# mppt.net
KiCad netlist of a schematic drawn in Altium Designer
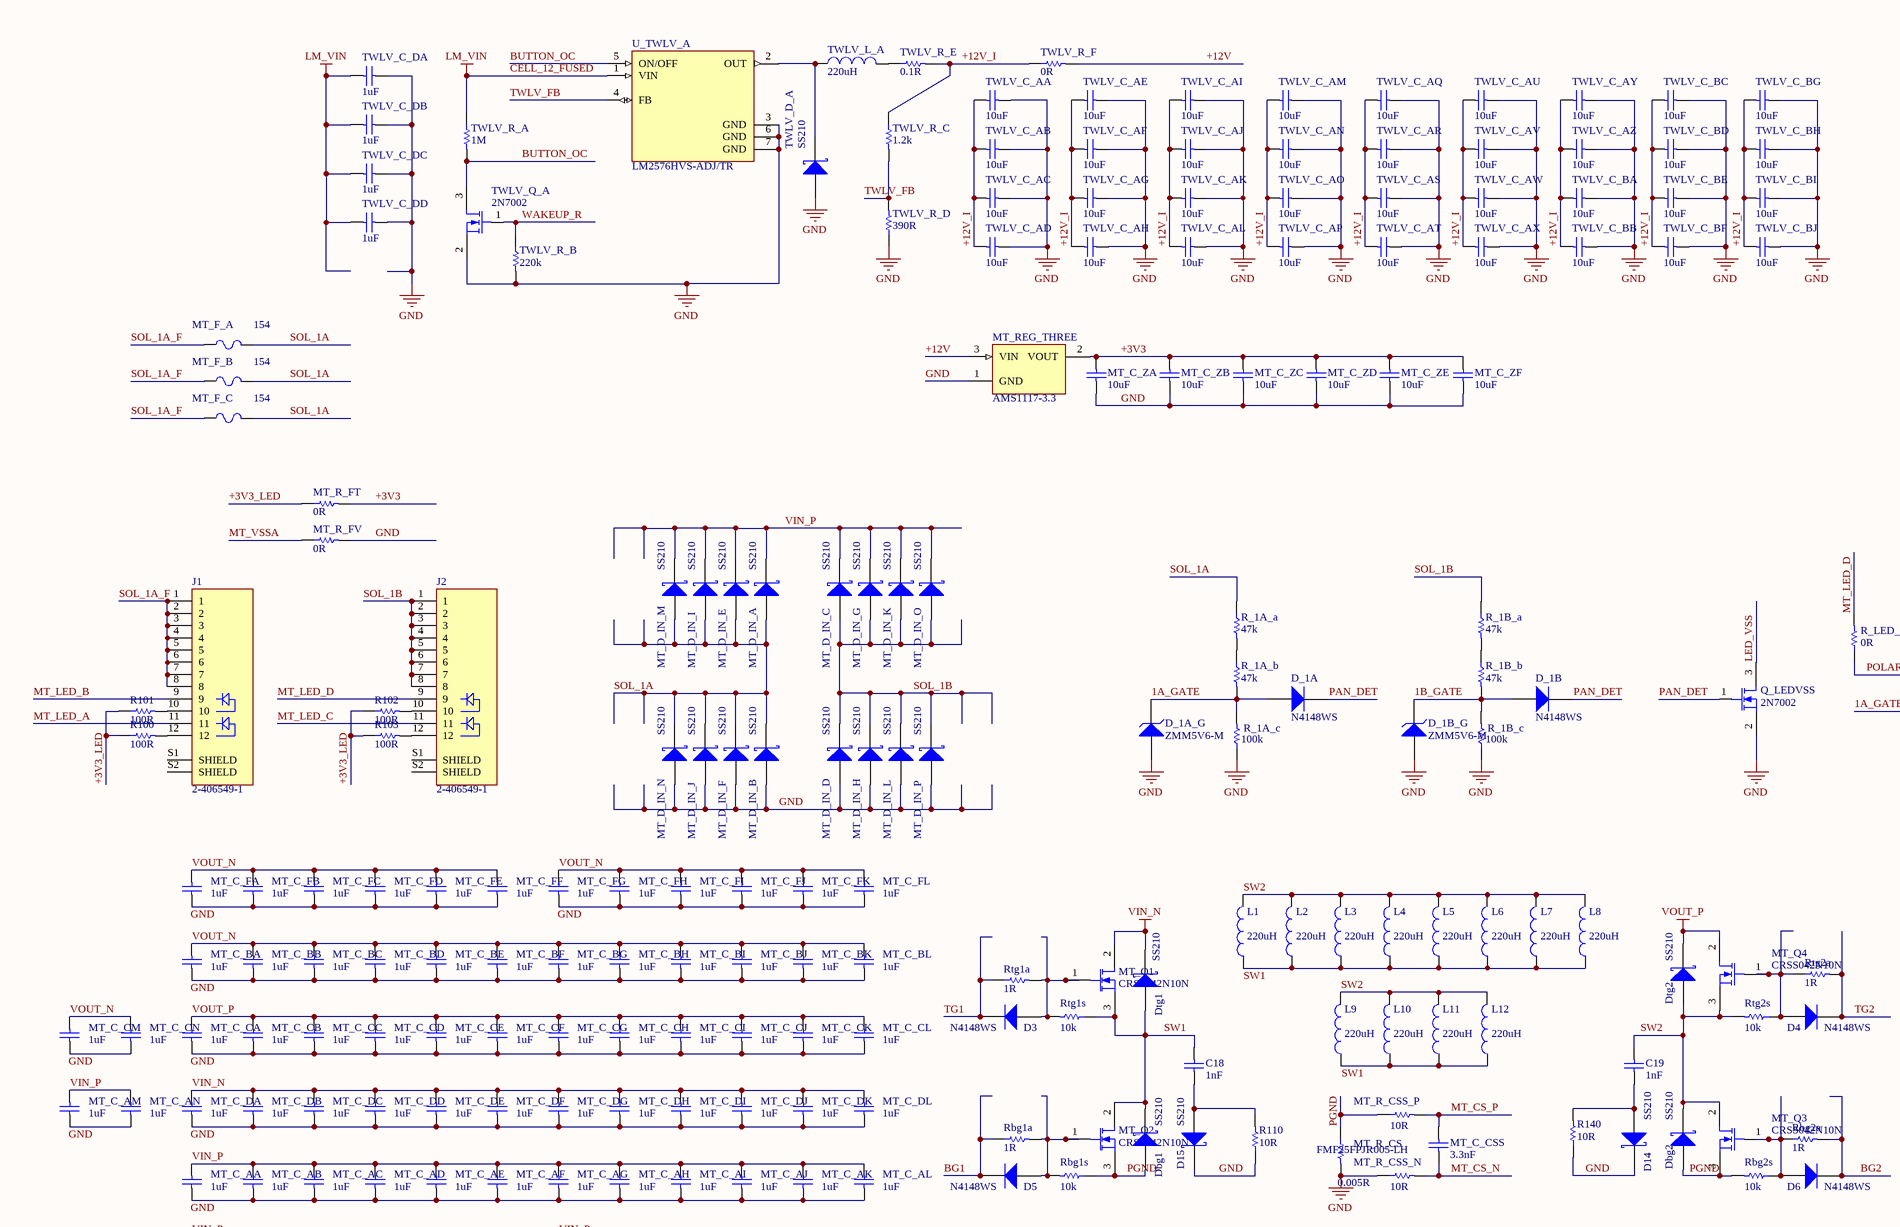
[diagram p0: mppt.SchDoc, top left]
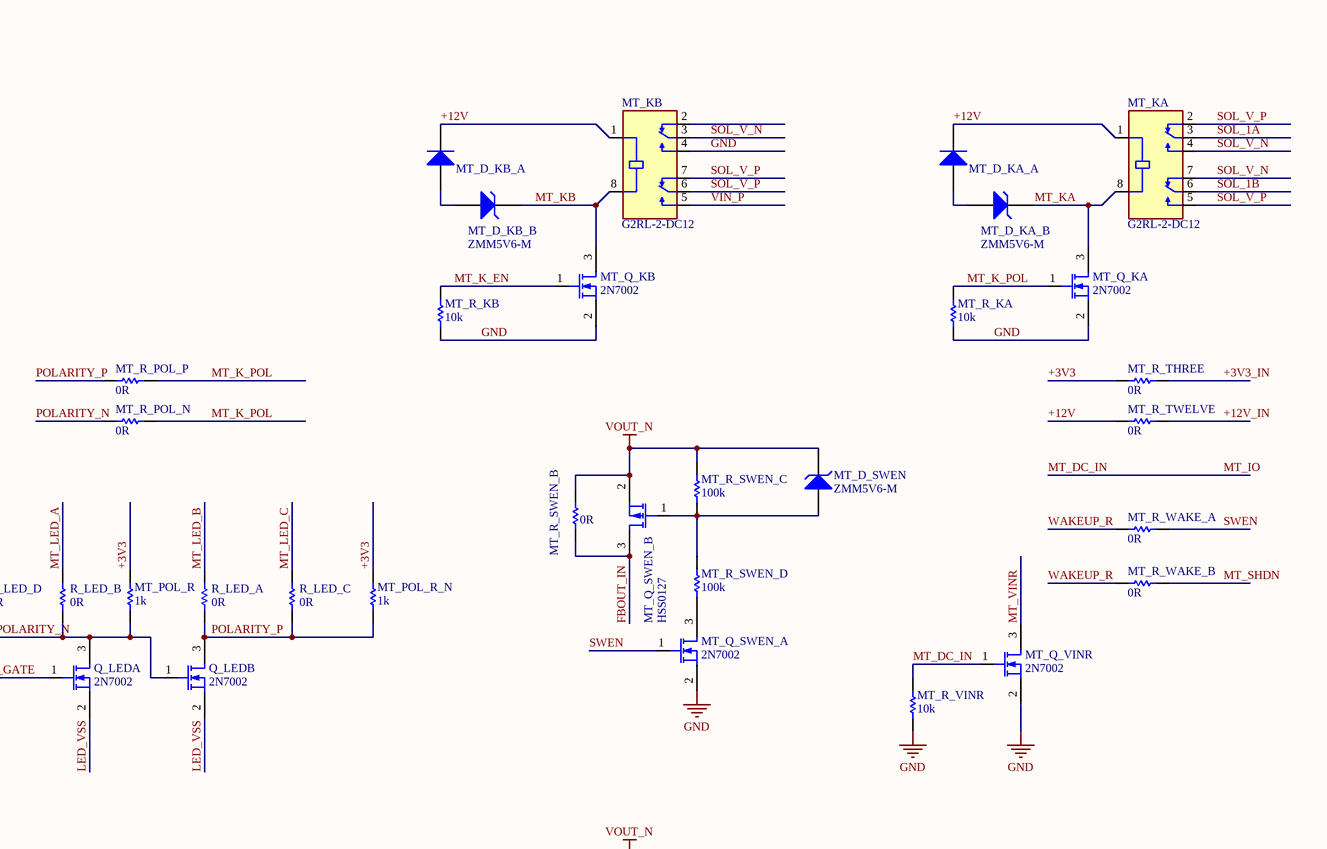
[diagram p1: mppt.SchDoc, top right]
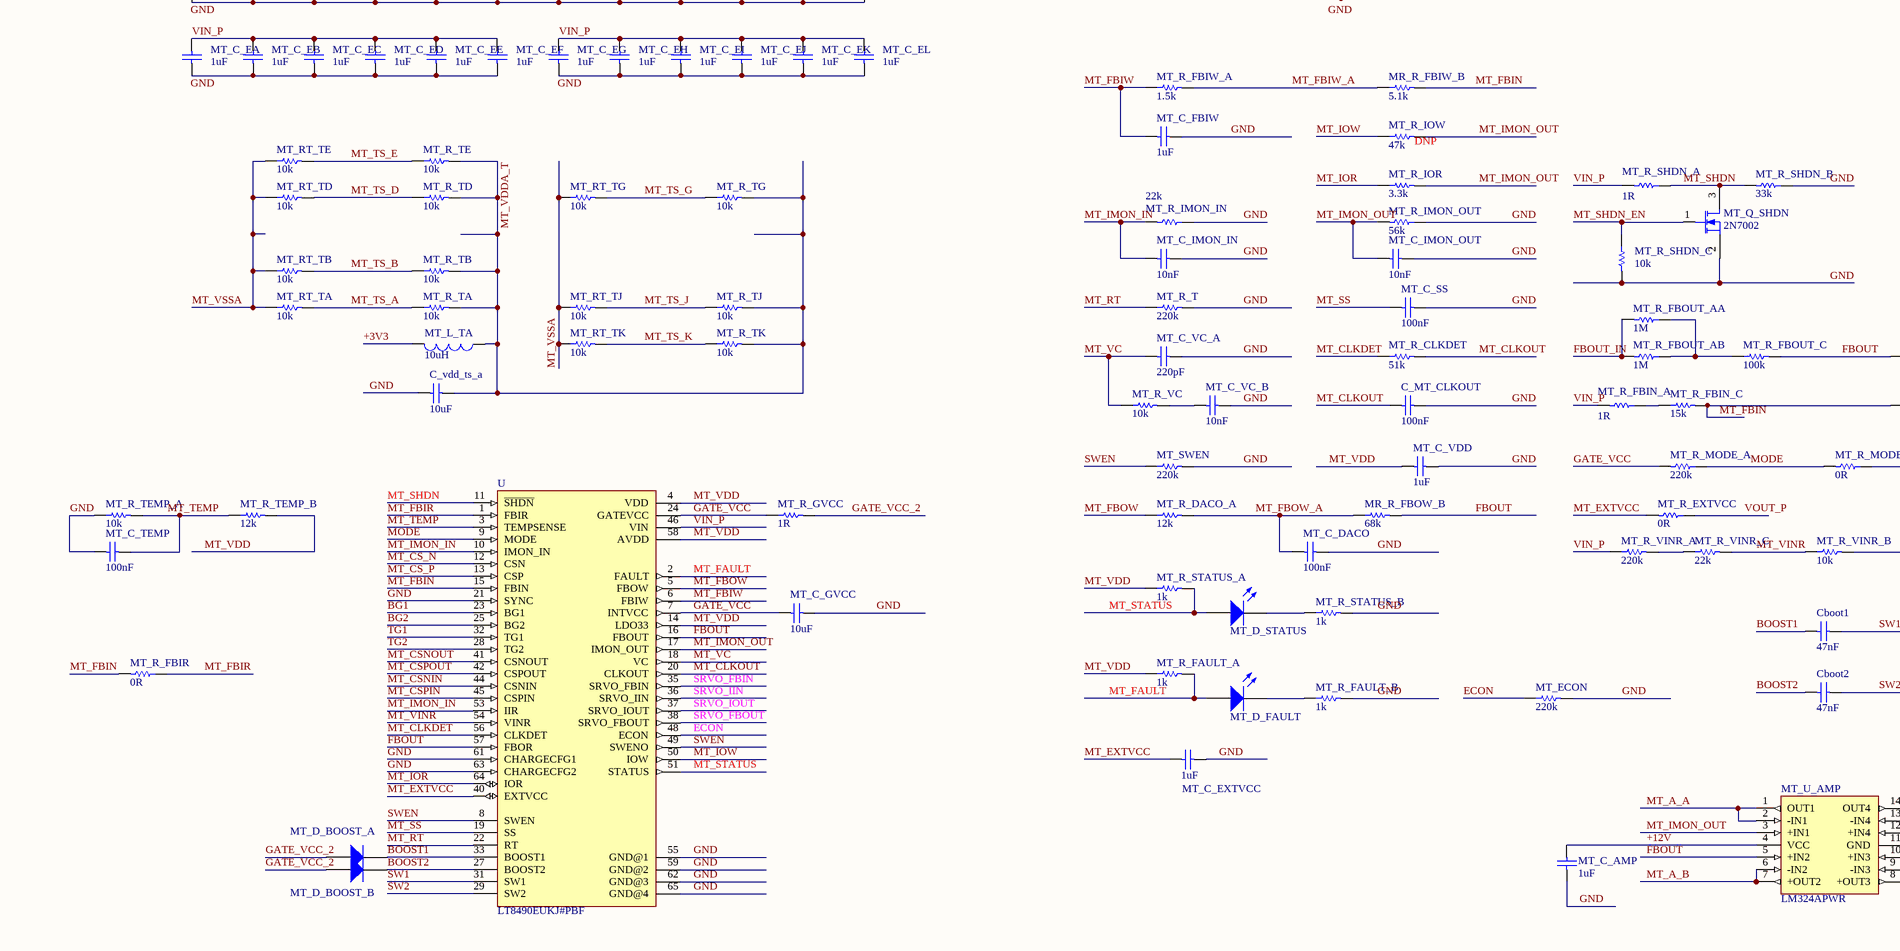
[diagram p2: mppt.SchDoc, bottom left]
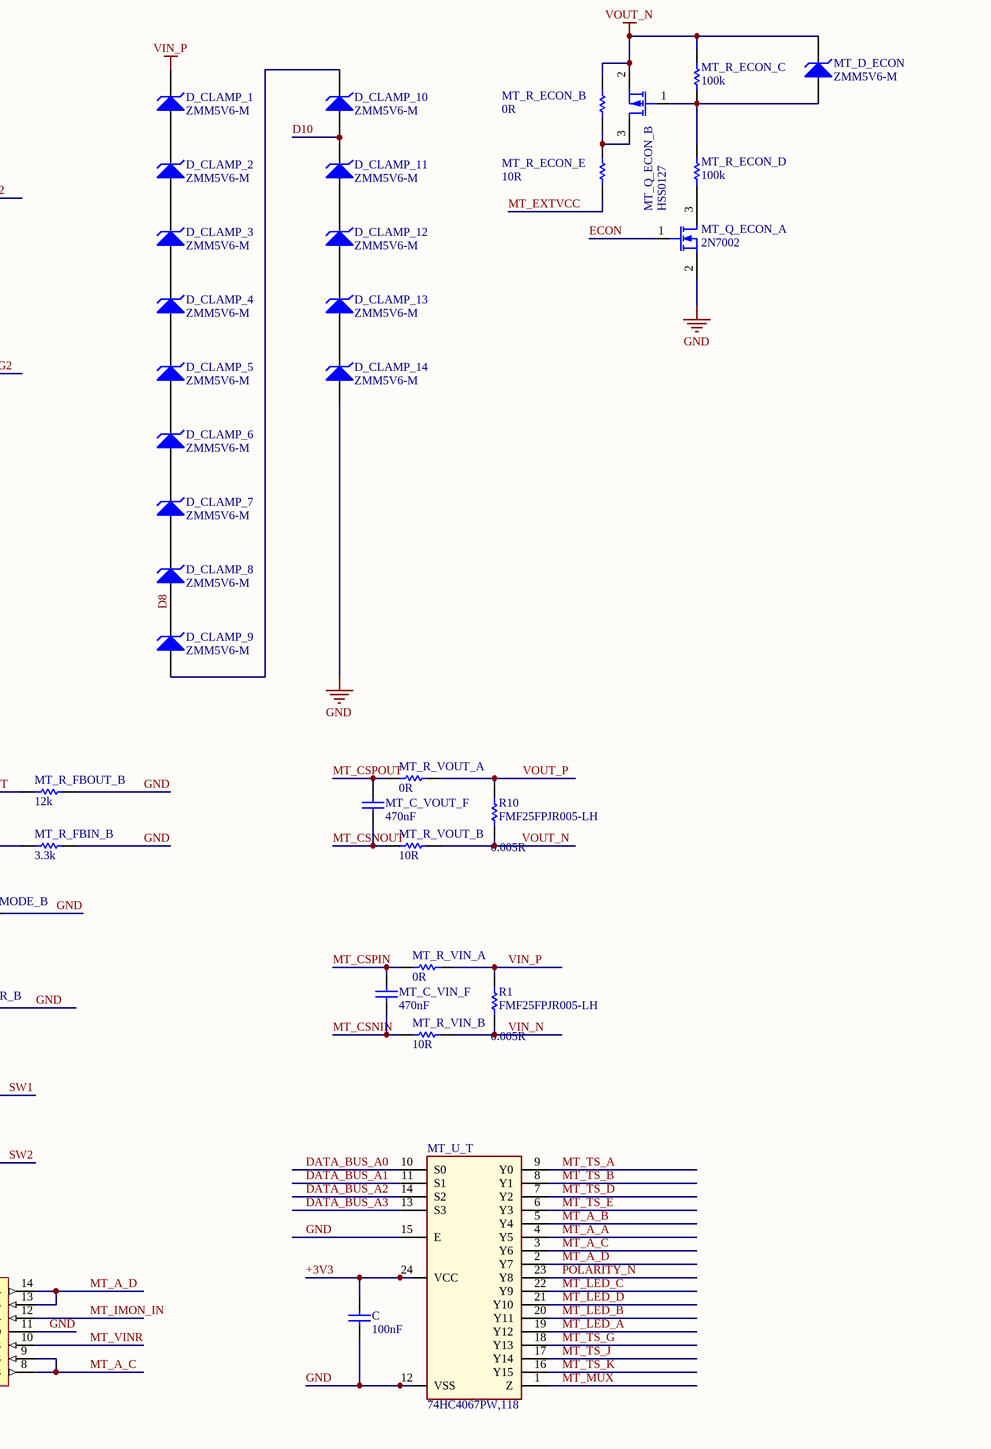
[diagram p3: mppt.SchDoc, bottom right]

(export (version "E")
  (design (tool "Eeschema 10.0.6"))
  (components
    (comp (ref "C")
      (value "100nF")
      (footprint "C_0402")
      (description "C - CAPACITOR - MLCC - 100nF - 16V - 0402")
      (fields (field (name "LCSC PART #") "C1525") (field (name "Comment") "CL05B104KO5NNNC"))
      (libsource (lib "JLC_PCB") (part "CL05B104KO5NNNC"))
    )
    (comp (ref "C18")
      (value "1nF")
      (footprint "C_1206")
      (description "C - CAPACITOR - MLCC - 1nF - 2000V - 1206 - X7R")
      (fields (field (name "LCSC PART #") "C9196") (field (name "Comment") "1206B102K202NT"))
      (libsource (lib "JLC_PCB") (part "1206B102K202NT"))
    )
    (comp (ref "C19")
      (value "1nF")
      (footprint "C_1206")
      (description "C - CAPACITOR - MLCC - 1nF - 2000V - 1206 - X7R")
      (fields (field (name "LCSC PART #") "C9196") (field (name "Comment") "1206B102K202NT"))
      (libsource (lib "JLC_PCB") (part "1206B102K202NT"))
    )
    (comp (ref "Cboot1")
      (value "47nF")
      (footprint "C_0603")
      (description "C - CAPACITOR - MLCC - 470nF - 25V - 0603")
      (fields (field (name "LCSC PART #") "C1623") (field (name "Comment") "CL10B474KA8NNNC"))
      (libsource (lib "JLC_PCB") (part "CL10B474KA8NNNC"))
    )
    (comp (ref "Cboot2")
      (value "47nF")
      (footprint "C_0603")
      (description "C - CAPACITOR - MLCC - 470nF - 25V - 0603")
      (fields (field (name "LCSC PART #") "C1623") (field (name "Comment") "CL10B474KA8NNNC"))
      (libsource (lib "JLC_PCB") (part "CL10B474KA8NNNC"))
    )
    (comp (ref "C_MT_CLKOUT")
      (value "100nF")
      (footprint "C_0402")
      (description "C - CAPACITOR - MLCC - 100nF - 16V - 0402")
      (fields (field (name "LCSC PART #") "C1525") (field (name "Comment") "CL05B104KO5NNNC"))
      (libsource (lib "JLC_PCB") (part "CL05B104KO5NNNC"))
    )
    (comp (ref "C_vdd_ts_a")
      (value "10uF")
      (footprint "C_0402")
      (description "C - CAPACITOR - MLCC - 10uF - 6.3V - 0402")
      (fields (field (name "LCSC PART #") "C15525") (field (name "Comment") "CL05A106MQ5NUNC"))
      (libsource (lib "JLC_PCB") (part "CL05A106MQ5NUNC"))
    )
    (comp (ref "D3")
      (value "N4148WS")
      (footprint "SOD-323")
      (description "D - DIODE - FAST TRR - 100V - 150mA - 4ns")
      (fields (field (name "LCSC PART #") "C2128"))
      (libsource (lib "JLC_PCB") (part "N4148WS"))
    )
    (comp (ref "D4")
      (value "N4148WS")
      (footprint "SOD-323")
      (description "D - DIODE - FAST TRR - 100V - 150mA - 4ns")
      (fields (field (name "LCSC PART #") "C2128"))
      (libsource (lib "JLC_PCB") (part "N4148WS"))
    )
    (comp (ref "D5")
      (value "N4148WS")
      (footprint "SOD-323")
      (description "D - DIODE - FAST TRR - 100V - 150mA - 4ns")
      (fields (field (name "LCSC PART #") "C2128"))
      (libsource (lib "JLC_PCB") (part "N4148WS"))
    )
    (comp (ref "D6")
      (value "N4148WS")
      (footprint "SOD-323")
      (description "D - DIODE - FAST TRR - 100V - 150mA - 4ns")
      (fields (field (name "LCSC PART #") "C2128"))
      (libsource (lib "JLC_PCB") (part "N4148WS"))
    )
    (comp (ref "D14")
      (value "SS210")
      (footprint "DO-214AC")
      (description "D - DIODE - SCHOTTKY - 100V - 2A")
      (fields (field (name "LCSC PART #") "C14996"))
      (libsource (lib "JLC_PCB") (part "SS210"))
    )
    (comp (ref "D15")
      (value "SS210")
      (footprint "DO-214AC")
      (description "D - DIODE - SCHOTTKY - 100V - 2A")
      (fields (field (name "LCSC PART #") "C14996"))
      (libsource (lib "JLC_PCB") (part "SS210"))
    )
    (comp (ref "Dbg1")
      (value "SS210")
      (footprint "DO-214AC")
      (description "D - DIODE - SCHOTTKY - 100V - 2A")
      (fields (field (name "LCSC PART #") "C14996"))
      (libsource (lib "JLC_PCB") (part "SS210"))
    )
    (comp (ref "Dbg2")
      (value "SS210")
      (footprint "DO-214AC")
      (description "D - DIODE - SCHOTTKY - 100V - 2A")
      (fields (field (name "LCSC PART #") "C14996"))
      (libsource (lib "JLC_PCB") (part "SS210"))
    )
    (comp (ref "Dtg1")
      (value "SS210")
      (footprint "DO-214AC")
      (description "D - DIODE - SCHOTTKY - 100V - 2A")
      (fields (field (name "LCSC PART #") "C14996"))
      (libsource (lib "JLC_PCB") (part "SS210"))
    )
    (comp (ref "Dtg2")
      (value "SS210")
      (footprint "DO-214AC")
      (description "D - DIODE - SCHOTTKY - 100V - 2A")
      (fields (field (name "LCSC PART #") "C14996"))
      (libsource (lib "JLC_PCB") (part "SS210"))
    )
    (comp (ref "D_1A")
      (value "N4148WS")
      (footprint "SOD-323")
      (description "D - DIODE - FAST TRR - 100V - 150mA - 4ns")
      (fields (field (name "LCSC PART #") "C2128"))
      (libsource (lib "JLC_PCB") (part "N4148WS"))
    )
    (comp (ref "D_1A_G")
      (value "ZMM5V6-M")
      (footprint "DO-213AA")
      (description "D - DIODE - ZENER - 5.6V - 500mW")
      (fields (field (name "LCSC PART #") "C8062"))
      (libsource (lib "JLC_PCB") (part "ZMM5V6-M"))
    )
    (comp (ref "D_1B")
      (value "N4148WS")
      (footprint "SOD-323")
      (description "D - DIODE - FAST TRR - 100V - 150mA - 4ns")
      (fields (field (name "LCSC PART #") "C2128"))
      (libsource (lib "JLC_PCB") (part "N4148WS"))
    )
    (comp (ref "D_1B_G")
      (value "ZMM5V6-M")
      (footprint "DO-213AA")
      (description "D - DIODE - ZENER - 5.6V - 500mW")
      (fields (field (name "LCSC PART #") "C8062"))
      (libsource (lib "JLC_PCB") (part "ZMM5V6-M"))
    )
    (comp (ref "D_CLAMP_1")
      (value "ZMM5V6-M")
      (footprint "DO-213AA")
      (description "D - DIODE - ZENER - 5.6V - 500mW")
      (fields (field (name "LCSC PART #") "C8062"))
      (libsource (lib "JLC_PCB") (part "ZMM5V6-M"))
    )
    (comp (ref "D_CLAMP_2")
      (value "ZMM5V6-M")
      (footprint "DO-213AA")
      (description "D - DIODE - ZENER - 5.6V - 500mW")
      (fields (field (name "LCSC PART #") "C8062"))
      (libsource (lib "JLC_PCB") (part "ZMM5V6-M"))
    )
    (comp (ref "D_CLAMP_3")
      (value "ZMM5V6-M")
      (footprint "DO-213AA")
      (description "D - DIODE - ZENER - 5.6V - 500mW")
      (fields (field (name "LCSC PART #") "C8062"))
      (libsource (lib "JLC_PCB") (part "ZMM5V6-M"))
    )
    (comp (ref "D_CLAMP_4")
      (value "ZMM5V6-M")
      (footprint "DO-213AA")
      (description "D - DIODE - ZENER - 5.6V - 500mW")
      (fields (field (name "LCSC PART #") "C8062"))
      (libsource (lib "JLC_PCB") (part "ZMM5V6-M"))
    )
    (comp (ref "D_CLAMP_5")
      (value "ZMM5V6-M")
      (footprint "DO-213AA")
      (description "D - DIODE - ZENER - 5.6V - 500mW")
      (fields (field (name "LCSC PART #") "C8062"))
      (libsource (lib "JLC_PCB") (part "ZMM5V6-M"))
    )
    (comp (ref "D_CLAMP_6")
      (value "ZMM5V6-M")
      (footprint "DO-213AA")
      (description "D - DIODE - ZENER - 5.6V - 500mW")
      (fields (field (name "LCSC PART #") "C8062"))
      (libsource (lib "JLC_PCB") (part "ZMM5V6-M"))
    )
    (comp (ref "D_CLAMP_7")
      (value "ZMM5V6-M")
      (footprint "DO-213AA")
      (description "D - DIODE - ZENER - 5.6V - 500mW")
      (fields (field (name "LCSC PART #") "C8062"))
      (libsource (lib "JLC_PCB") (part "ZMM5V6-M"))
    )
    (comp (ref "D_CLAMP_8")
      (value "ZMM5V6-M")
      (footprint "DO-213AA")
      (description "D - DIODE - ZENER - 5.6V - 500mW")
      (fields (field (name "LCSC PART #") "C8062"))
      (libsource (lib "JLC_PCB") (part "ZMM5V6-M"))
    )
    (comp (ref "D_CLAMP_9")
      (value "ZMM5V6-M")
      (footprint "DO-213AA")
      (description "D - DIODE - ZENER - 5.6V - 500mW")
      (fields (field (name "LCSC PART #") "C8062"))
      (libsource (lib "JLC_PCB") (part "ZMM5V6-M"))
    )
    (comp (ref "D_CLAMP_10")
      (value "ZMM5V6-M")
      (footprint "DO-213AA")
      (description "D - DIODE - ZENER - 5.6V - 500mW")
      (fields (field (name "LCSC PART #") "C8062"))
      (libsource (lib "JLC_PCB") (part "ZMM5V6-M"))
    )
    (comp (ref "D_CLAMP_11")
      (value "ZMM5V6-M")
      (footprint "DO-213AA")
      (description "D - DIODE - ZENER - 5.6V - 500mW")
      (fields (field (name "LCSC PART #") "C8062"))
      (libsource (lib "JLC_PCB") (part "ZMM5V6-M"))
    )
    (comp (ref "D_CLAMP_12")
      (value "ZMM5V6-M")
      (footprint "DO-213AA")
      (description "D - DIODE - ZENER - 5.6V - 500mW")
      (fields (field (name "LCSC PART #") "C8062"))
      (libsource (lib "JLC_PCB") (part "ZMM5V6-M"))
    )
    (comp (ref "D_CLAMP_13")
      (value "ZMM5V6-M")
      (footprint "DO-213AA")
      (description "D - DIODE - ZENER - 5.6V - 500mW")
      (fields (field (name "LCSC PART #") "C8062"))
      (libsource (lib "JLC_PCB") (part "ZMM5V6-M"))
    )
    (comp (ref "D_CLAMP_14")
      (value "ZMM5V6-M")
      (footprint "DO-213AA")
      (description "D - DIODE - ZENER - 5.6V - 500mW")
      (fields (field (name "LCSC PART #") "C8062"))
      (libsource (lib "JLC_PCB") (part "ZMM5V6-M"))
    )
    (comp (ref "J1")
      (value "2-406549-1")
      (footprint "TE_2-406549-1")
      (description "J - JACK - ETHERNET - Right - THT")
      (fields (field (name "LCSC PART #") "C125068"))
      (libsource (lib "JLC_PCB") (part "2-406549-1"))
    )
    (comp (ref "J2")
      (value "2-406549-1")
      (footprint "TE_2-406549-1")
      (description "J - JACK - ETHERNET - Right - THT")
      (fields (field (name "LCSC PART #") "C125068"))
      (libsource (lib "JLC_PCB") (part "2-406549-1"))
    )
    (comp (ref "L1")
      (value "220uH")
      (footprint "SRR1260")
      (description "L - INDUCTOR - 220uH - 1.6A - 12.5mm")
      (fields (field (name "LCSC PART #") "C169380") (field (name "Comment") "SWRB1207S-221MT"))
      (libsource (lib "JLC_PCB") (part "SWRB1207S-221MT"))
    )
    (comp (ref "L2")
      (value "220uH")
      (footprint "SRR1260")
      (description "L - INDUCTOR - 220uH - 1.6A - 12.5mm")
      (fields (field (name "LCSC PART #") "C169380") (field (name "Comment") "SWRB1207S-221MT"))
      (libsource (lib "JLC_PCB") (part "SWRB1207S-221MT"))
    )
    (comp (ref "L3")
      (value "220uH")
      (footprint "SRR1260")
      (description "L - INDUCTOR - 220uH - 1.6A - 12.5mm")
      (fields (field (name "LCSC PART #") "C169380") (field (name "Comment") "SWRB1207S-221MT"))
      (libsource (lib "JLC_PCB") (part "SWRB1207S-221MT"))
    )
    (comp (ref "L4")
      (value "220uH")
      (footprint "SRR1260")
      (description "L - INDUCTOR - 220uH - 1.6A - 12.5mm")
      (fields (field (name "LCSC PART #") "C169380") (field (name "Comment") "SWRB1207S-221MT"))
      (libsource (lib "JLC_PCB") (part "SWRB1207S-221MT"))
    )
    (comp (ref "L5")
      (value "220uH")
      (footprint "SRR1260")
      (description "L - INDUCTOR - 220uH - 1.6A - 12.5mm")
      (fields (field (name "LCSC PART #") "C169380") (field (name "Comment") "SWRB1207S-221MT"))
      (libsource (lib "JLC_PCB") (part "SWRB1207S-221MT"))
    )
    (comp (ref "L6")
      (value "220uH")
      (footprint "SRR1260")
      (description "L - INDUCTOR - 220uH - 1.6A - 12.5mm")
      (fields (field (name "LCSC PART #") "C169380") (field (name "Comment") "SWRB1207S-221MT"))
      (libsource (lib "JLC_PCB") (part "SWRB1207S-221MT"))
    )
    (comp (ref "L7")
      (value "220uH")
      (footprint "SRR1260")
      (description "L - INDUCTOR - 220uH - 1.6A - 12.5mm")
      (fields (field (name "LCSC PART #") "C169380") (field (name "Comment") "SWRB1207S-221MT"))
      (libsource (lib "JLC_PCB") (part "SWRB1207S-221MT"))
    )
    (comp (ref "L8")
      (value "220uH")
      (footprint "SRR1260")
      (description "L - INDUCTOR - 220uH - 1.6A - 12.5mm")
      (fields (field (name "LCSC PART #") "C169380") (field (name "Comment") "SWRB1207S-221MT"))
      (libsource (lib "JLC_PCB") (part "SWRB1207S-221MT"))
    )
    (comp (ref "L9")
      (value "220uH")
      (footprint "SRR1260")
      (description "L - INDUCTOR - 220uH - 1.6A - 12.5mm")
      (fields (field (name "LCSC PART #") "C169380") (field (name "Comment") "SWRB1207S-221MT"))
      (libsource (lib "JLC_PCB") (part "SWRB1207S-221MT"))
    )
    (comp (ref "L10")
      (value "220uH")
      (footprint "SRR1260")
      (description "L - INDUCTOR - 220uH - 1.6A - 12.5mm")
      (fields (field (name "LCSC PART #") "C169380") (field (name "Comment") "SWRB1207S-221MT"))
      (libsource (lib "JLC_PCB") (part "SWRB1207S-221MT"))
    )
    (comp (ref "L11")
      (value "220uH")
      (footprint "SRR1260")
      (description "L - INDUCTOR - 220uH - 1.6A - 12.5mm")
      (fields (field (name "LCSC PART #") "C169380") (field (name "Comment") "SWRB1207S-221MT"))
      (libsource (lib "JLC_PCB") (part "SWRB1207S-221MT"))
    )
    (comp (ref "L12")
      (value "220uH")
      (footprint "SRR1260")
      (description "L - INDUCTOR - 220uH - 1.6A - 12.5mm")
      (fields (field (name "LCSC PART #") "C169380") (field (name "Comment") "SWRB1207S-221MT"))
      (libsource (lib "JLC_PCB") (part "SWRB1207S-221MT"))
    )
    (comp (ref "MR_R_FBIW_B")
      (value "5.1k")
      (footprint "R_0402")
      (description "R - RESISTOR - SMD - 5.1k - 1% - 0402")
      (fields (field (name "LCSC PART #") "C25905") (field (name "Comment") "0402WGF5101TCE"))
      (libsource (lib "JLC_PCB") (part "0402WGF5101TCE"))
    )
    (comp (ref "MR_R_FBOW_B")
      (value "68k")
      (footprint "R_0402")
      (description "R - RESISTOR - SMD - 68k - 1% - 0402")
      (fields (field (name "LCSC PART #") "C36871") (field (name "Comment") "0402WGF6802TCE"))
      (libsource (lib "JLC_PCB") (part "0402WGF6802TCE"))
    )
    (comp (ref "MT_C_AA")
      (value "1uF")
      (footprint "C_1206")
      (description "C - CAPACITOR - MLCC - 1uF - 100V - 1206 - X7R")
      (fields (field (name "LCSC PART #") "C91151") (field (name "Comment") "1206B105K101NT"))
      (libsource (lib "JLC_PCB") (part "1206B105K101NT"))
    )
    (comp (ref "MT_C_AB")
      (value "1uF")
      (footprint "C_1206")
      (description "C - CAPACITOR - MLCC - 1uF - 100V - 1206 - X7R")
      (fields (field (name "LCSC PART #") "C91151") (field (name "Comment") "1206B105K101NT"))
      (libsource (lib "JLC_PCB") (part "1206B105K101NT"))
    )
    (comp (ref "MT_C_AC")
      (value "1uF")
      (footprint "C_1206")
      (description "C - CAPACITOR - MLCC - 1uF - 100V - 1206 - X7R")
      (fields (field (name "LCSC PART #") "C91151") (field (name "Comment") "1206B105K101NT"))
      (libsource (lib "JLC_PCB") (part "1206B105K101NT"))
    )
    (comp (ref "MT_C_AD")
      (value "1uF")
      (footprint "C_1206")
      (description "C - CAPACITOR - MLCC - 1uF - 100V - 1206 - X7R")
      (fields (field (name "LCSC PART #") "C91151") (field (name "Comment") "1206B105K101NT"))
      (libsource (lib "JLC_PCB") (part "1206B105K101NT"))
    )
    (comp (ref "MT_C_AE")
      (value "1uF")
      (footprint "C_1206")
      (description "C - CAPACITOR - MLCC - 1uF - 100V - 1206 - X7R")
      (fields (field (name "LCSC PART #") "C91151") (field (name "Comment") "1206B105K101NT"))
      (libsource (lib "JLC_PCB") (part "1206B105K101NT"))
    )
    (comp (ref "MT_C_AF")
      (value "1uF")
      (footprint "C_1206")
      (description "C - CAPACITOR - MLCC - 1uF - 100V - 1206 - X7R")
      (fields (field (name "LCSC PART #") "C91151") (field (name "Comment") "1206B105K101NT"))
      (libsource (lib "JLC_PCB") (part "1206B105K101NT"))
    )
    (comp (ref "MT_C_AG")
      (value "1uF")
      (footprint "C_1206")
      (description "C - CAPACITOR - MLCC - 1uF - 100V - 1206 - X7R")
      (fields (field (name "LCSC PART #") "C91151") (field (name "Comment") "1206B105K101NT"))
      (libsource (lib "JLC_PCB") (part "1206B105K101NT"))
    )
    (comp (ref "MT_C_AH")
      (value "1uF")
      (footprint "C_1206")
      (description "C - CAPACITOR - MLCC - 1uF - 100V - 1206 - X7R")
      (fields (field (name "LCSC PART #") "C91151") (field (name "Comment") "1206B105K101NT"))
      (libsource (lib "JLC_PCB") (part "1206B105K101NT"))
    )
    (comp (ref "MT_C_AI")
      (value "1uF")
      (footprint "C_1206")
      (description "C - CAPACITOR - MLCC - 1uF - 100V - 1206 - X7R")
      (fields (field (name "LCSC PART #") "C91151") (field (name "Comment") "1206B105K101NT"))
      (libsource (lib "JLC_PCB") (part "1206B105K101NT"))
    )
    (comp (ref "MT_C_AJ")
      (value "1uF")
      (footprint "C_1206")
      (description "C - CAPACITOR - MLCC - 1uF - 100V - 1206 - X7R")
      (fields (field (name "LCSC PART #") "C91151") (field (name "Comment") "1206B105K101NT"))
      (libsource (lib "JLC_PCB") (part "1206B105K101NT"))
    )
    (comp (ref "MT_C_AK")
      (value "1uF")
      (footprint "C_1206")
      (description "C - CAPACITOR - MLCC - 1uF - 100V - 1206 - X7R")
      (fields (field (name "LCSC PART #") "C91151") (field (name "Comment") "1206B105K101NT"))
      (libsource (lib "JLC_PCB") (part "1206B105K101NT"))
    )
    (comp (ref "MT_C_AL")
      (value "1uF")
      (footprint "C_1206")
      (description "C - CAPACITOR - MLCC - 1uF - 100V - 1206 - X7R")
      (fields (field (name "LCSC PART #") "C91151") (field (name "Comment") "1206B105K101NT"))
      (libsource (lib "JLC_PCB") (part "1206B105K101NT"))
    )
    (comp (ref "MT_C_AM")
      (value "1uF")
      (footprint "C_1206")
      (description "C - CAPACITOR - MLCC - 1uF - 100V - 1206 - X7R")
      (fields (field (name "LCSC PART #") "C91151") (field (name "Comment") "1206B105K101NT"))
      (libsource (lib "JLC_PCB") (part "1206B105K101NT"))
    )
    (comp (ref "MT_C_AMP")
      (value "1uF")
      (footprint "C_0402")
      (description "C - CAPACITOR - MLCC - 1uF - 25V - 0402")
      (fields (field (name "LCSC PART #") "C52923") (field (name "Comment") "CL05A105KA5NQNC"))
      (libsource (lib "JLC_PCB") (part "CL05A105KA5NQNC"))
    )
    (comp (ref "MT_C_AN")
      (value "1uF")
      (footprint "C_1206")
      (description "C - CAPACITOR - MLCC - 1uF - 100V - 1206 - X7R")
      (fields (field (name "LCSC PART #") "C91151") (field (name "Comment") "1206B105K101NT"))
      (libsource (lib "JLC_PCB") (part "1206B105K101NT"))
    )
    (comp (ref "MT_C_BA")
      (value "1uF")
      (footprint "C_1206")
      (description "C - CAPACITOR - MLCC - 1uF - 100V - 1206 - X7R")
      (fields (field (name "LCSC PART #") "C91151") (field (name "Comment") "1206B105K101NT"))
      (libsource (lib "JLC_PCB") (part "1206B105K101NT"))
    )
    (comp (ref "MT_C_BB")
      (value "1uF")
      (footprint "C_1206")
      (description "C - CAPACITOR - MLCC - 1uF - 100V - 1206 - X7R")
      (fields (field (name "LCSC PART #") "C91151") (field (name "Comment") "1206B105K101NT"))
      (libsource (lib "JLC_PCB") (part "1206B105K101NT"))
    )
    (comp (ref "MT_C_BC")
      (value "1uF")
      (footprint "C_1206")
      (description "C - CAPACITOR - MLCC - 1uF - 100V - 1206 - X7R")
      (fields (field (name "LCSC PART #") "C91151") (field (name "Comment") "1206B105K101NT"))
      (libsource (lib "JLC_PCB") (part "1206B105K101NT"))
    )
    (comp (ref "MT_C_BD")
      (value "1uF")
      (footprint "C_1206")
      (description "C - CAPACITOR - MLCC - 1uF - 100V - 1206 - X7R")
      (fields (field (name "LCSC PART #") "C91151") (field (name "Comment") "1206B105K101NT"))
      (libsource (lib "JLC_PCB") (part "1206B105K101NT"))
    )
    (comp (ref "MT_C_BE")
      (value "1uF")
      (footprint "C_1206")
      (description "C - CAPACITOR - MLCC - 1uF - 100V - 1206 - X7R")
      (fields (field (name "LCSC PART #") "C91151") (field (name "Comment") "1206B105K101NT"))
      (libsource (lib "JLC_PCB") (part "1206B105K101NT"))
    )
    (comp (ref "MT_C_BF")
      (value "1uF")
      (footprint "C_1206")
      (description "C - CAPACITOR - MLCC - 1uF - 100V - 1206 - X7R")
      (fields (field (name "LCSC PART #") "C91151") (field (name "Comment") "1206B105K101NT"))
      (libsource (lib "JLC_PCB") (part "1206B105K101NT"))
    )
    (comp (ref "MT_C_BG")
      (value "1uF")
      (footprint "C_1206")
      (description "C - CAPACITOR - MLCC - 1uF - 100V - 1206 - X7R")
      (fields (field (name "LCSC PART #") "C91151") (field (name "Comment") "1206B105K101NT"))
      (libsource (lib "JLC_PCB") (part "1206B105K101NT"))
    )
    (comp (ref "MT_C_BH")
      (value "1uF")
      (footprint "C_1206")
      (description "C - CAPACITOR - MLCC - 1uF - 100V - 1206 - X7R")
      (fields (field (name "LCSC PART #") "C91151") (field (name "Comment") "1206B105K101NT"))
      (libsource (lib "JLC_PCB") (part "1206B105K101NT"))
    )
    (comp (ref "MT_C_BI")
      (value "1uF")
      (footprint "C_1206")
      (description "C - CAPACITOR - MLCC - 1uF - 100V - 1206 - X7R")
      (fields (field (name "LCSC PART #") "C91151") (field (name "Comment") "1206B105K101NT"))
      (libsource (lib "JLC_PCB") (part "1206B105K101NT"))
    )
    (comp (ref "MT_C_BJ")
      (value "1uF")
      (footprint "C_1206")
      (description "C - CAPACITOR - MLCC - 1uF - 100V - 1206 - X7R")
      (fields (field (name "LCSC PART #") "C91151") (field (name "Comment") "1206B105K101NT"))
      (libsource (lib "JLC_PCB") (part "1206B105K101NT"))
    )
    (comp (ref "MT_C_BK")
      (value "1uF")
      (footprint "C_1206")
      (description "C - CAPACITOR - MLCC - 1uF - 100V - 1206 - X7R")
      (fields (field (name "LCSC PART #") "C91151") (field (name "Comment") "1206B105K101NT"))
      (libsource (lib "JLC_PCB") (part "1206B105K101NT"))
    )
    (comp (ref "MT_C_BL")
      (value "1uF")
      (footprint "C_1206")
      (description "C - CAPACITOR - MLCC - 1uF - 100V - 1206 - X7R")
      (fields (field (name "LCSC PART #") "C91151") (field (name "Comment") "1206B105K101NT"))
      (libsource (lib "JLC_PCB") (part "1206B105K101NT"))
    )
    (comp (ref "MT_C_CA")
      (value "1uF")
      (footprint "C_1206")
      (description "C - CAPACITOR - MLCC - 1uF - 100V - 1206 - X7R")
      (fields (field (name "LCSC PART #") "C91151") (field (name "Comment") "1206B105K101NT"))
      (libsource (lib "JLC_PCB") (part "1206B105K101NT"))
    )
    (comp (ref "MT_C_CB")
      (value "1uF")
      (footprint "C_1206")
      (description "C - CAPACITOR - MLCC - 1uF - 100V - 1206 - X7R")
      (fields (field (name "LCSC PART #") "C91151") (field (name "Comment") "1206B105K101NT"))
      (libsource (lib "JLC_PCB") (part "1206B105K101NT"))
    )
    (comp (ref "MT_C_CC")
      (value "1uF")
      (footprint "C_1206")
      (description "C - CAPACITOR - MLCC - 1uF - 100V - 1206 - X7R")
      (fields (field (name "LCSC PART #") "C91151") (field (name "Comment") "1206B105K101NT"))
      (libsource (lib "JLC_PCB") (part "1206B105K101NT"))
    )
    (comp (ref "MT_C_CD")
      (value "1uF")
      (footprint "C_1206")
      (description "C - CAPACITOR - MLCC - 1uF - 100V - 1206 - X7R")
      (fields (field (name "LCSC PART #") "C91151") (field (name "Comment") "1206B105K101NT"))
      (libsource (lib "JLC_PCB") (part "1206B105K101NT"))
    )
    (comp (ref "MT_C_CE")
      (value "1uF")
      (footprint "C_1206")
      (description "C - CAPACITOR - MLCC - 1uF - 100V - 1206 - X7R")
      (fields (field (name "LCSC PART #") "C91151") (field (name "Comment") "1206B105K101NT"))
      (libsource (lib "JLC_PCB") (part "1206B105K101NT"))
    )
    (comp (ref "MT_C_CF")
      (value "1uF")
      (footprint "C_1206")
      (description "C - CAPACITOR - MLCC - 1uF - 100V - 1206 - X7R")
      (fields (field (name "LCSC PART #") "C91151") (field (name "Comment") "1206B105K101NT"))
      (libsource (lib "JLC_PCB") (part "1206B105K101NT"))
    )
    (comp (ref "MT_C_CG")
      (value "1uF")
      (footprint "C_1206")
      (description "C - CAPACITOR - MLCC - 1uF - 100V - 1206 - X7R")
      (fields (field (name "LCSC PART #") "C91151") (field (name "Comment") "1206B105K101NT"))
      (libsource (lib "JLC_PCB") (part "1206B105K101NT"))
    )
    (comp (ref "MT_C_CH")
      (value "1uF")
      (footprint "C_1206")
      (description "C - CAPACITOR - MLCC - 1uF - 100V - 1206 - X7R")
      (fields (field (name "LCSC PART #") "C91151") (field (name "Comment") "1206B105K101NT"))
      (libsource (lib "JLC_PCB") (part "1206B105K101NT"))
    )
    (comp (ref "MT_C_CI")
      (value "1uF")
      (footprint "C_1206")
      (description "C - CAPACITOR - MLCC - 1uF - 100V - 1206 - X7R")
      (fields (field (name "LCSC PART #") "C91151") (field (name "Comment") "1206B105K101NT"))
      (libsource (lib "JLC_PCB") (part "1206B105K101NT"))
    )
    (comp (ref "MT_C_CJ")
      (value "1uF")
      (footprint "C_1206")
      (description "C - CAPACITOR - MLCC - 1uF - 100V - 1206 - X7R")
      (fields (field (name "LCSC PART #") "C91151") (field (name "Comment") "1206B105K101NT"))
      (libsource (lib "JLC_PCB") (part "1206B105K101NT"))
    )
    (comp (ref "MT_C_CK")
      (value "1uF")
      (footprint "C_1206")
      (description "C - CAPACITOR - MLCC - 1uF - 100V - 1206 - X7R")
      (fields (field (name "LCSC PART #") "C91151") (field (name "Comment") "1206B105K101NT"))
      (libsource (lib "JLC_PCB") (part "1206B105K101NT"))
    )
    (comp (ref "MT_C_CL")
      (value "1uF")
      (footprint "C_1206")
      (description "C - CAPACITOR - MLCC - 1uF - 100V - 1206 - X7R")
      (fields (field (name "LCSC PART #") "C91151") (field (name "Comment") "1206B105K101NT"))
      (libsource (lib "JLC_PCB") (part "1206B105K101NT"))
    )
    (comp (ref "MT_C_CM")
      (value "1uF")
      (footprint "C_1206")
      (description "C - CAPACITOR - MLCC - 1uF - 100V - 1206 - X7R")
      (fields (field (name "LCSC PART #") "C91151") (field (name "Comment") "1206B105K101NT"))
      (libsource (lib "JLC_PCB") (part "1206B105K101NT"))
    )
    (comp (ref "MT_C_CN")
      (value "1uF")
      (footprint "C_1206")
      (description "C - CAPACITOR - MLCC - 1uF - 100V - 1206 - X7R")
      (fields (field (name "LCSC PART #") "C91151") (field (name "Comment") "1206B105K101NT"))
      (libsource (lib "JLC_PCB") (part "1206B105K101NT"))
    )
    (comp (ref "MT_C_CSS")
      (value "3.3nF")
      (footprint "C_0402")
      (description "C - CAPACITOR - MLCC - 3.3nF - 50V - 0402")
      (fields (field (name "LCSC PART #") "C26404") (field (name "Comment") "CL05B332KB5NNNC"))
      (libsource (lib "JLC_PCB") (part "CL05B332KB5NNNC"))
    )
    (comp (ref "MT_C_DA")
      (value "1uF")
      (footprint "C_1206")
      (description "C - CAPACITOR - MLCC - 1uF - 100V - 1206 - X7R")
      (fields (field (name "LCSC PART #") "C91151") (field (name "Comment") "1206B105K101NT"))
      (libsource (lib "JLC_PCB") (part "1206B105K101NT"))
    )
    (comp (ref "MT_C_DACO")
      (value "100nF")
      (footprint "C_0402")
      (description "C - CAPACITOR - MLCC - 100nF - 16V - 0402")
      (fields (field (name "LCSC PART #") "C1525") (field (name "Comment") "CL05B104KO5NNNC"))
      (libsource (lib "JLC_PCB") (part "CL05B104KO5NNNC"))
    )
    (comp (ref "MT_C_DB")
      (value "1uF")
      (footprint "C_1206")
      (description "C - CAPACITOR - MLCC - 1uF - 100V - 1206 - X7R")
      (fields (field (name "LCSC PART #") "C91151") (field (name "Comment") "1206B105K101NT"))
      (libsource (lib "JLC_PCB") (part "1206B105K101NT"))
    )
    (comp (ref "MT_C_DC")
      (value "1uF")
      (footprint "C_1206")
      (description "C - CAPACITOR - MLCC - 1uF - 100V - 1206 - X7R")
      (fields (field (name "LCSC PART #") "C91151") (field (name "Comment") "1206B105K101NT"))
      (libsource (lib "JLC_PCB") (part "1206B105K101NT"))
    )
    (comp (ref "MT_C_DD")
      (value "1uF")
      (footprint "C_1206")
      (description "C - CAPACITOR - MLCC - 1uF - 100V - 1206 - X7R")
      (fields (field (name "LCSC PART #") "C91151") (field (name "Comment") "1206B105K101NT"))
      (libsource (lib "JLC_PCB") (part "1206B105K101NT"))
    )
    (comp (ref "MT_C_DE")
      (value "1uF")
      (footprint "C_1206")
      (description "C - CAPACITOR - MLCC - 1uF - 100V - 1206 - X7R")
      (fields (field (name "LCSC PART #") "C91151") (field (name "Comment") "1206B105K101NT"))
      (libsource (lib "JLC_PCB") (part "1206B105K101NT"))
    )
    (comp (ref "MT_C_DF")
      (value "1uF")
      (footprint "C_1206")
      (description "C - CAPACITOR - MLCC - 1uF - 100V - 1206 - X7R")
      (fields (field (name "LCSC PART #") "C91151") (field (name "Comment") "1206B105K101NT"))
      (libsource (lib "JLC_PCB") (part "1206B105K101NT"))
    )
    (comp (ref "MT_C_DG")
      (value "1uF")
      (footprint "C_1206")
      (description "C - CAPACITOR - MLCC - 1uF - 100V - 1206 - X7R")
      (fields (field (name "LCSC PART #") "C91151") (field (name "Comment") "1206B105K101NT"))
      (libsource (lib "JLC_PCB") (part "1206B105K101NT"))
    )
    (comp (ref "MT_C_DH")
      (value "1uF")
      (footprint "C_1206")
      (description "C - CAPACITOR - MLCC - 1uF - 100V - 1206 - X7R")
      (fields (field (name "LCSC PART #") "C91151") (field (name "Comment") "1206B105K101NT"))
      (libsource (lib "JLC_PCB") (part "1206B105K101NT"))
    )
    (comp (ref "MT_C_DI")
      (value "1uF")
      (footprint "C_1206")
      (description "C - CAPACITOR - MLCC - 1uF - 100V - 1206 - X7R")
      (fields (field (name "LCSC PART #") "C91151") (field (name "Comment") "1206B105K101NT"))
      (libsource (lib "JLC_PCB") (part "1206B105K101NT"))
    )
    (comp (ref "MT_C_DJ")
      (value "1uF")
      (footprint "C_1206")
      (description "C - CAPACITOR - MLCC - 1uF - 100V - 1206 - X7R")
      (fields (field (name "LCSC PART #") "C91151") (field (name "Comment") "1206B105K101NT"))
      (libsource (lib "JLC_PCB") (part "1206B105K101NT"))
    )
    (comp (ref "MT_C_DK")
      (value "1uF")
      (footprint "C_1206")
      (description "C - CAPACITOR - MLCC - 1uF - 100V - 1206 - X7R")
      (fields (field (name "LCSC PART #") "C91151") (field (name "Comment") "1206B105K101NT"))
      (libsource (lib "JLC_PCB") (part "1206B105K101NT"))
    )
    (comp (ref "MT_C_DL")
      (value "1uF")
      (footprint "C_1206")
      (description "C - CAPACITOR - MLCC - 1uF - 100V - 1206 - X7R")
      (fields (field (name "LCSC PART #") "C91151") (field (name "Comment") "1206B105K101NT"))
      (libsource (lib "JLC_PCB") (part "1206B105K101NT"))
    )
    (comp (ref "MT_C_EA")
      (value "1uF")
      (footprint "C_1206")
      (description "C - CAPACITOR - MLCC - 1uF - 100V - 1206 - X7R")
      (fields (field (name "LCSC PART #") "C91151") (field (name "Comment") "1206B105K101NT"))
      (libsource (lib "JLC_PCB") (part "1206B105K101NT"))
    )
    (comp (ref "MT_C_EB")
      (value "1uF")
      (footprint "C_1206")
      (description "C - CAPACITOR - MLCC - 1uF - 100V - 1206 - X7R")
      (fields (field (name "LCSC PART #") "C91151") (field (name "Comment") "1206B105K101NT"))
      (libsource (lib "JLC_PCB") (part "1206B105K101NT"))
    )
    (comp (ref "MT_C_EC")
      (value "1uF")
      (footprint "C_1206")
      (description "C - CAPACITOR - MLCC - 1uF - 100V - 1206 - X7R")
      (fields (field (name "LCSC PART #") "C91151") (field (name "Comment") "1206B105K101NT"))
      (libsource (lib "JLC_PCB") (part "1206B105K101NT"))
    )
    (comp (ref "MT_C_ED")
      (value "1uF")
      (footprint "C_1206")
      (description "C - CAPACITOR - MLCC - 1uF - 100V - 1206 - X7R")
      (fields (field (name "LCSC PART #") "C91151") (field (name "Comment") "1206B105K101NT"))
      (libsource (lib "JLC_PCB") (part "1206B105K101NT"))
    )
    (comp (ref "MT_C_EE")
      (value "1uF")
      (footprint "C_1206")
      (description "C - CAPACITOR - MLCC - 1uF - 100V - 1206 - X7R")
      (fields (field (name "LCSC PART #") "C91151") (field (name "Comment") "1206B105K101NT"))
      (libsource (lib "JLC_PCB") (part "1206B105K101NT"))
    )
    (comp (ref "MT_C_EF")
      (value "1uF")
      (footprint "C_1206")
      (description "C - CAPACITOR - MLCC - 1uF - 100V - 1206 - X7R")
      (fields (field (name "LCSC PART #") "C91151") (field (name "Comment") "1206B105K101NT"))
      (libsource (lib "JLC_PCB") (part "1206B105K101NT"))
    )
    (comp (ref "MT_C_EG")
      (value "1uF")
      (footprint "C_1206")
      (description "C - CAPACITOR - MLCC - 1uF - 100V - 1206 - X7R")
      (fields (field (name "LCSC PART #") "C91151") (field (name "Comment") "1206B105K101NT"))
      (libsource (lib "JLC_PCB") (part "1206B105K101NT"))
    )
    (comp (ref "MT_C_EH")
      (value "1uF")
      (footprint "C_1206")
      (description "C - CAPACITOR - MLCC - 1uF - 100V - 1206 - X7R")
      (fields (field (name "LCSC PART #") "C91151") (field (name "Comment") "1206B105K101NT"))
      (libsource (lib "JLC_PCB") (part "1206B105K101NT"))
    )
    (comp (ref "MT_C_EI")
      (value "1uF")
      (footprint "C_1206")
      (description "C - CAPACITOR - MLCC - 1uF - 100V - 1206 - X7R")
      (fields (field (name "LCSC PART #") "C91151") (field (name "Comment") "1206B105K101NT"))
      (libsource (lib "JLC_PCB") (part "1206B105K101NT"))
    )
    (comp (ref "MT_C_EJ")
      (value "1uF")
      (footprint "C_1206")
      (description "C - CAPACITOR - MLCC - 1uF - 100V - 1206 - X7R")
      (fields (field (name "LCSC PART #") "C91151") (field (name "Comment") "1206B105K101NT"))
      (libsource (lib "JLC_PCB") (part "1206B105K101NT"))
    )
    (comp (ref "MT_C_EK")
      (value "1uF")
      (footprint "C_1206")
      (description "C - CAPACITOR - MLCC - 1uF - 100V - 1206 - X7R")
      (fields (field (name "LCSC PART #") "C91151") (field (name "Comment") "1206B105K101NT"))
      (libsource (lib "JLC_PCB") (part "1206B105K101NT"))
    )
    (comp (ref "MT_C_EL")
      (value "1uF")
      (footprint "C_1206")
      (description "C - CAPACITOR - MLCC - 1uF - 100V - 1206 - X7R")
      (fields (field (name "LCSC PART #") "C91151") (field (name "Comment") "1206B105K101NT"))
      (libsource (lib "JLC_PCB") (part "1206B105K101NT"))
    )
    (comp (ref "MT_C_EXTVCC")
      (value "1uF")
      (footprint "C_1206")
      (description "C - CAPACITOR - MLCC - 1uF - 100V - 1206 - X7R")
      (fields (field (name "LCSC PART #") "C91151") (field (name "Comment") "1206B105K101NT"))
      (libsource (lib "JLC_PCB") (part "1206B105K101NT"))
    )
    (comp (ref "MT_C_FA")
      (value "1uF")
      (footprint "C_1206")
      (description "C - CAPACITOR - MLCC - 1uF - 100V - 1206 - X7R")
      (fields (field (name "LCSC PART #") "C91151") (field (name "Comment") "1206B105K101NT"))
      (libsource (lib "JLC_PCB") (part "1206B105K101NT"))
    )
    (comp (ref "MT_C_FB")
      (value "1uF")
      (footprint "C_1206")
      (description "C - CAPACITOR - MLCC - 1uF - 100V - 1206 - X7R")
      (fields (field (name "LCSC PART #") "C91151") (field (name "Comment") "1206B105K101NT"))
      (libsource (lib "JLC_PCB") (part "1206B105K101NT"))
    )
    (comp (ref "MT_C_FBIW")
      (value "1uF")
      (footprint "C_0402")
      (description "C - CAPACITOR - MLCC - 1uF - 25V - 0402")
      (fields (field (name "LCSC PART #") "C52923") (field (name "Comment") "CL05A105KA5NQNC"))
      (libsource (lib "JLC_PCB") (part "CL05A105KA5NQNC"))
    )
    (comp (ref "MT_C_FC")
      (value "1uF")
      (footprint "C_1206")
      (description "C - CAPACITOR - MLCC - 1uF - 100V - 1206 - X7R")
      (fields (field (name "LCSC PART #") "C91151") (field (name "Comment") "1206B105K101NT"))
      (libsource (lib "JLC_PCB") (part "1206B105K101NT"))
    )
    (comp (ref "MT_C_FD")
      (value "1uF")
      (footprint "C_1206")
      (description "C - CAPACITOR - MLCC - 1uF - 100V - 1206 - X7R")
      (fields (field (name "LCSC PART #") "C91151") (field (name "Comment") "1206B105K101NT"))
      (libsource (lib "JLC_PCB") (part "1206B105K101NT"))
    )
    (comp (ref "MT_C_FE")
      (value "1uF")
      (footprint "C_1206")
      (description "C - CAPACITOR - MLCC - 1uF - 100V - 1206 - X7R")
      (fields (field (name "LCSC PART #") "C91151") (field (name "Comment") "1206B105K101NT"))
      (libsource (lib "JLC_PCB") (part "1206B105K101NT"))
    )
    (comp (ref "MT_C_FF")
      (value "1uF")
      (footprint "C_1206")
      (description "C - CAPACITOR - MLCC - 1uF - 100V - 1206 - X7R")
      (fields (field (name "LCSC PART #") "C91151") (field (name "Comment") "1206B105K101NT"))
      (libsource (lib "JLC_PCB") (part "1206B105K101NT"))
    )
    (comp (ref "MT_C_FG")
      (value "1uF")
      (footprint "C_1206")
      (description "C - CAPACITOR - MLCC - 1uF - 100V - 1206 - X7R")
      (fields (field (name "LCSC PART #") "C91151") (field (name "Comment") "1206B105K101NT"))
      (libsource (lib "JLC_PCB") (part "1206B105K101NT"))
    )
    (comp (ref "MT_C_FH")
      (value "1uF")
      (footprint "C_1206")
      (description "C - CAPACITOR - MLCC - 1uF - 100V - 1206 - X7R")
      (fields (field (name "LCSC PART #") "C91151") (field (name "Comment") "1206B105K101NT"))
      (libsource (lib "JLC_PCB") (part "1206B105K101NT"))
    )
    (comp (ref "MT_C_FI")
      (value "1uF")
      (footprint "C_1206")
      (description "C - CAPACITOR - MLCC - 1uF - 100V - 1206 - X7R")
      (fields (field (name "LCSC PART #") "C91151") (field (name "Comment") "1206B105K101NT"))
      (libsource (lib "JLC_PCB") (part "1206B105K101NT"))
    )
    (comp (ref "MT_C_FJ")
      (value "1uF")
      (footprint "C_1206")
      (description "C - CAPACITOR - MLCC - 1uF - 100V - 1206 - X7R")
      (fields (field (name "LCSC PART #") "C91151") (field (name "Comment") "1206B105K101NT"))
      (libsource (lib "JLC_PCB") (part "1206B105K101NT"))
    )
    (comp (ref "MT_C_FK")
      (value "1uF")
      (footprint "C_1206")
      (description "C - CAPACITOR - MLCC - 1uF - 100V - 1206 - X7R")
      (fields (field (name "LCSC PART #") "C91151") (field (name "Comment") "1206B105K101NT"))
      (libsource (lib "JLC_PCB") (part "1206B105K101NT"))
    )
    (comp (ref "MT_C_FL")
      (value "1uF")
      (footprint "C_1206")
      (description "C - CAPACITOR - MLCC - 1uF - 100V - 1206 - X7R")
      (fields (field (name "LCSC PART #") "C91151") (field (name "Comment") "1206B105K101NT"))
      (libsource (lib "JLC_PCB") (part "1206B105K101NT"))
    )
    (comp (ref "MT_C_GVCC")
      (value "10uF")
      (footprint "C_0805")
      (description "C - CAPACITOR - MLCC - 10uF - 50V - 0805")
      (fields (field (name "LCSC PART #") "C440198") (field (name "Comment") "GRM21BR61H106KE43L"))
      (libsource (lib "JLC_PCB") (part "GRM21BR61H106KE43L"))
    )
    (comp (ref "MT_C_IMON_IN")
      (value "10nF")
      (footprint "C_0402")
      (description "C - CAPACITOR - MLCC - 10nF - 50V - 0402")
      (fields (field (name "LCSC PART #") "C15195") (field (name "Comment") "CL05B103KB5NNNC"))
      (libsource (lib "JLC_PCB") (part "CL05B103KB5NNNC"))
    )
    (comp (ref "MT_C_IMON_OUT")
      (value "10nF")
      (footprint "C_0402")
      (description "C - CAPACITOR - MLCC - 10nF - 50V - 0402")
      (fields (field (name "LCSC PART #") "C15195") (field (name "Comment") "CL05B103KB5NNNC"))
      (libsource (lib "JLC_PCB") (part "CL05B103KB5NNNC"))
    )
    (comp (ref "MT_C_SS")
      (value "100nF")
      (footprint "C_0402")
      (description "C - CAPACITOR - MLCC - 100nF - 16V - 0402")
      (fields (field (name "LCSC PART #") "C1525") (field (name "Comment") "CL05B104KO5NNNC"))
      (libsource (lib "JLC_PCB") (part "CL05B104KO5NNNC"))
    )
    (comp (ref "MT_C_TEMP")
      (value "100nF")
      (footprint "C_0402")
      (description "C - CAPACITOR - MLCC - 100nF - 16V - 0402")
      (fields (field (name "LCSC PART #") "C1525") (field (name "Comment") "CL05B104KO5NNNC"))
      (libsource (lib "JLC_PCB") (part "CL05B104KO5NNNC"))
    )
    (comp (ref "MT_C_VC_A")
      (value "220pF")
      (footprint "C_0402")
      (description "C - CAPACITOR - MLCC - 220pF - 50V - 0402")
      (fields (field (name "LCSC PART #") "C1530") (field (name "Comment") "0402B221K500NT"))
      (libsource (lib "JLC_PCB") (part "0402B221K500NT"))
    )
    (comp (ref "MT_C_VC_B")
      (value "10nF")
      (footprint "C_0402")
      (description "C - CAPACITOR - MLCC - 10nF - 50V - 0402")
      (fields (field (name "LCSC PART #") "C15195") (field (name "Comment") "CL05B103KB5NNNC"))
      (libsource (lib "JLC_PCB") (part "CL05B103KB5NNNC"))
    )
    (comp (ref "MT_C_VDD")
      (value "1uF")
      (footprint "C_0402")
      (description "C - CAPACITOR - MLCC - 1uF - 25V - 0402")
      (fields (field (name "LCSC PART #") "C52923") (field (name "Comment") "CL05A105KA5NQNC"))
      (libsource (lib "JLC_PCB") (part "CL05A105KA5NQNC"))
    )
    (comp (ref "MT_C_VIN_F")
      (value "470nF")
      (footprint "C_0402")
      (description "C - CAPACITOR - MLCC - 470nF - 10V - 0402")
      (fields (field (name "LCSC PART #") "C47339") (field (name "Comment") "CL05A474KP5NNNC"))
      (libsource (lib "JLC_PCB") (part "CL05A474KP5NNNC"))
    )
    (comp (ref "MT_C_VOUT_F")
      (value "470nF")
      (footprint "C_0402")
      (description "C - CAPACITOR - MLCC - 470nF - 10V - 0402")
      (fields (field (name "LCSC PART #") "C47339") (field (name "Comment") "CL05A474KP5NNNC"))
      (libsource (lib "JLC_PCB") (part "CL05A474KP5NNNC"))
    )
    (comp (ref "MT_C_ZA")
      (value "10uF")
      (footprint "C_0402")
      (description "C - CAPACITOR - MLCC - 10uF - 6.3V - 0402")
      (fields (field (name "LCSC PART #") "C15525") (field (name "Comment") "CL05A106MQ5NUNC"))
      (libsource (lib "JLC_PCB") (part "CL05A106MQ5NUNC"))
    )
    (comp (ref "MT_C_ZB")
      (value "10uF")
      (footprint "C_0402")
      (description "C - CAPACITOR - MLCC - 10uF - 6.3V - 0402")
      (fields (field (name "LCSC PART #") "C15525") (field (name "Comment") "CL05A106MQ5NUNC"))
      (libsource (lib "JLC_PCB") (part "CL05A106MQ5NUNC"))
    )
    (comp (ref "MT_C_ZC")
      (value "10uF")
      (footprint "C_0402")
      (description "C - CAPACITOR - MLCC - 10uF - 6.3V - 0402")
      (fields (field (name "LCSC PART #") "C15525") (field (name "Comment") "CL05A106MQ5NUNC"))
      (libsource (lib "JLC_PCB") (part "CL05A106MQ5NUNC"))
    )
    (comp (ref "MT_C_ZD")
      (value "10uF")
      (footprint "C_0402")
      (description "C - CAPACITOR - MLCC - 10uF - 6.3V - 0402")
      (fields (field (name "LCSC PART #") "C15525") (field (name "Comment") "CL05A106MQ5NUNC"))
      (libsource (lib "JLC_PCB") (part "CL05A106MQ5NUNC"))
    )
    (comp (ref "MT_C_ZE")
      (value "10uF")
      (footprint "C_0402")
      (description "C - CAPACITOR - MLCC - 10uF - 6.3V - 0402")
      (fields (field (name "LCSC PART #") "C15525") (field (name "Comment") "CL05A106MQ5NUNC"))
      (libsource (lib "JLC_PCB") (part "CL05A106MQ5NUNC"))
    )
    (comp (ref "MT_C_ZF")
      (value "10uF")
      (footprint "C_0402")
      (description "C - CAPACITOR - MLCC - 10uF - 6.3V - 0402")
      (fields (field (name "LCSC PART #") "C15525") (field (name "Comment") "CL05A106MQ5NUNC"))
      (libsource (lib "JLC_PCB") (part "CL05A106MQ5NUNC"))
    )
    (comp (ref "MT_D_BOOST_A")
      (value "1N4148WS")
      (footprint "SOD-323")
      (description "D - DIODE - FAST TRR - 100V - 150mA - 4ns")
      (fields (field (name "LCSC PART #") "C2128"))
      (libsource (lib "JLC_PCB") (part "1N4148WS"))
    )
    (comp (ref "MT_D_BOOST_B")
      (value "1N4148WS")
      (footprint "SOD-323")
      (description "D - DIODE - FAST TRR - 100V - 150mA - 4ns")
      (fields (field (name "LCSC PART #") "C2128"))
      (libsource (lib "JLC_PCB") (part "1N4148WS"))
    )
    (comp (ref "MT_D_ECON")
      (value "ZMM5V6-M")
      (footprint "DO-213AA")
      (description "D - DIODE - ZENER - 5.6V - 500mW")
      (fields (field (name "LCSC PART #") "C8062"))
      (libsource (lib "JLC_PCB") (part "ZMM5V6-M"))
    )
    (comp (ref "MT_D_FAULT")
      (value "KT-0603R")
      (footprint "D_0603")
      (description "D - LED - 0603 - Red")
      (fields (field (name "LCSC PART #") "C2286"))
      (libsource (lib "JLC_PCB") (part "KT-0603R"))
    )
    (comp (ref "MT_D_IN_A")
      (value "SS210")
      (footprint "DO-214AC")
      (description "D - DIODE - SCHOTTKY - 100V - 2A")
      (fields (field (name "LCSC PART #") "C14996"))
      (libsource (lib "JLC_PCB") (part "SS210"))
    )
    (comp (ref "MT_D_IN_B")
      (value "SS210")
      (footprint "DO-214AC")
      (description "D - DIODE - SCHOTTKY - 100V - 2A")
      (fields (field (name "LCSC PART #") "C14996"))
      (libsource (lib "JLC_PCB") (part "SS210"))
    )
    (comp (ref "MT_D_IN_C")
      (value "SS210")
      (footprint "DO-214AC")
      (description "D - DIODE - SCHOTTKY - 100V - 2A")
      (fields (field (name "LCSC PART #") "C14996"))
      (libsource (lib "JLC_PCB") (part "SS210"))
    )
    (comp (ref "MT_D_IN_D")
      (value "SS210")
      (footprint "DO-214AC")
      (description "D - DIODE - SCHOTTKY - 100V - 2A")
      (fields (field (name "LCSC PART #") "C14996"))
      (libsource (lib "JLC_PCB") (part "SS210"))
    )
    (comp (ref "MT_D_IN_E")
      (value "SS210")
      (footprint "DO-214AC")
      (description "D - DIODE - SCHOTTKY - 100V - 2A")
      (fields (field (name "LCSC PART #") "C14996"))
      (libsource (lib "JLC_PCB") (part "SS210"))
    )
    (comp (ref "MT_D_IN_F")
      (value "SS210")
      (footprint "DO-214AC")
      (description "D - DIODE - SCHOTTKY - 100V - 2A")
      (fields (field (name "LCSC PART #") "C14996"))
      (libsource (lib "JLC_PCB") (part "SS210"))
    )
    (comp (ref "MT_D_IN_G")
      (value "SS210")
      (footprint "DO-214AC")
      (description "D - DIODE - SCHOTTKY - 100V - 2A")
      (fields (field (name "LCSC PART #") "C14996"))
      (libsource (lib "JLC_PCB") (part "SS210"))
    )
    (comp (ref "MT_D_IN_H")
      (value "SS210")
      (footprint "DO-214AC")
      (description "D - DIODE - SCHOTTKY - 100V - 2A")
      (fields (field (name "LCSC PART #") "C14996"))
      (libsource (lib "JLC_PCB") (part "SS210"))
    )
    (comp (ref "MT_D_IN_I")
      (value "SS210")
      (footprint "DO-214AC")
      (description "D - DIODE - SCHOTTKY - 100V - 2A")
      (fields (field (name "LCSC PART #") "C14996"))
      (libsource (lib "JLC_PCB") (part "SS210"))
    )
    (comp (ref "MT_D_IN_J")
      (value "SS210")
      (footprint "DO-214AC")
      (description "D - DIODE - SCHOTTKY - 100V - 2A")
      (fields (field (name "LCSC PART #") "C14996"))
      (libsource (lib "JLC_PCB") (part "SS210"))
    )
    (comp (ref "MT_D_IN_K")
      (value "SS210")
      (footprint "DO-214AC")
      (description "D - DIODE - SCHOTTKY - 100V - 2A")
      (fields (field (name "LCSC PART #") "C14996"))
      (libsource (lib "JLC_PCB") (part "SS210"))
    )
    (comp (ref "MT_D_IN_L")
      (value "SS210")
      (footprint "DO-214AC")
      (description "D - DIODE - SCHOTTKY - 100V - 2A")
      (fields (field (name "LCSC PART #") "C14996"))
      (libsource (lib "JLC_PCB") (part "SS210"))
    )
    (comp (ref "MT_D_IN_M")
      (value "SS210")
      (footprint "DO-214AC")
      (description "D - DIODE - SCHOTTKY - 100V - 2A")
      (fields (field (name "LCSC PART #") "C14996"))
      (libsource (lib "JLC_PCB") (part "SS210"))
    )
    (comp (ref "MT_D_IN_N")
      (value "SS210")
      (footprint "DO-214AC")
      (description "D - DIODE - SCHOTTKY - 100V - 2A")
      (fields (field (name "LCSC PART #") "C14996"))
      (libsource (lib "JLC_PCB") (part "SS210"))
    )
    (comp (ref "MT_D_IN_O")
      (value "SS210")
      (footprint "DO-214AC")
      (description "D - DIODE - SCHOTTKY - 100V - 2A")
      (fields (field (name "LCSC PART #") "C14996"))
      (libsource (lib "JLC_PCB") (part "SS210"))
    )
    (comp (ref "MT_D_IN_P")
      (value "SS210")
      (footprint "DO-214AC")
      (description "D - DIODE - SCHOTTKY - 100V - 2A")
      (fields (field (name "LCSC PART #") "C14996"))
      (libsource (lib "JLC_PCB") (part "SS210"))
    )
    (comp (ref "MT_D_KA_A")
      (value "1N4148WS")
      (footprint "SOD-323")
      (description "D - DIODE - FAST TRR - 100V - 150mA - 4ns")
      (fields (field (name "LCSC PART #") "C2128"))
      (libsource (lib "JLC_PCB") (part "1N4148WS"))
    )
    (comp (ref "MT_D_KA_B")
      (value "ZMM5V6-M")
      (footprint "DO-213AA")
      (description "D - DIODE - ZENER - 5.6V - 500mW")
      (fields (field (name "LCSC PART #") "C8062"))
      (libsource (lib "JLC_PCB") (part "ZMM5V6-M"))
    )
    (comp (ref "MT_D_KB_A")
      (value "1N4148WS")
      (footprint "SOD-323")
      (description "D - DIODE - FAST TRR - 100V - 150mA - 4ns")
      (fields (field (name "LCSC PART #") "C2128"))
      (libsource (lib "JLC_PCB") (part "1N4148WS"))
    )
    (comp (ref "MT_D_KB_B")
      (value "ZMM5V6-M")
      (footprint "DO-213AA")
      (description "D - DIODE - ZENER - 5.6V - 500mW")
      (fields (field (name "LCSC PART #") "C8062"))
      (libsource (lib "JLC_PCB") (part "ZMM5V6-M"))
    )
    (comp (ref "MT_D_STATUS")
      (value "KT-0603R")
      (footprint "D_0603")
      (description "D - LED - 0603 - Red")
      (fields (field (name "LCSC PART #") "C2286"))
      (libsource (lib "JLC_PCB") (part "KT-0603R"))
    )
    (comp (ref "MT_D_SWEN")
      (value "ZMM5V6-M")
      (footprint "DO-213AA")
      (description "D - DIODE - ZENER - 5.6V - 500mW")
      (fields (field (name "LCSC PART #") "C8062"))
      (libsource (lib "JLC_PCB") (part "ZMM5V6-M"))
    )
    (comp (ref "MT_ECON")
      (value "220k")
      (footprint "R_0402")
      (description "R - RESISTOR - SMD - 220k - 1% - 0402")
      (fields (field (name "LCSC PART #") "C25767") (field (name "Comment") "0402WGF2203TCE"))
      (libsource (lib "JLC_PCB") (part "0402WGF2203TCE"))
    )
    (comp (ref "MT_F_A")
      (value "154")
      (footprint "01550900M")
      (description "F - FUSE - FUSEHOLDER - 154 - SMD")
      (fields (field (name "LCSC PART #") "C108518") (field (name "Comment") "01550900M"))
      (libsource (lib "JLC_PCB") (part "01550900M"))
    )
    (comp (ref "MT_F_B")
      (value "154")
      (footprint "01550900M")
      (description "F - FUSE - FUSEHOLDER - 154 - SMD")
      (fields (field (name "LCSC PART #") "C108518") (field (name "Comment") "01550900M"))
      (libsource (lib "JLC_PCB") (part "01550900M"))
    )
    (comp (ref "MT_F_C")
      (value "154")
      (footprint "01550900M")
      (description "F - FUSE - FUSEHOLDER - 154 - SMD")
      (fields (field (name "LCSC PART #") "C108518") (field (name "Comment") "01550900M"))
      (libsource (lib "JLC_PCB") (part "01550900M"))
    )
    (comp (ref "MT_KA")
      (value "G2RL-2-DC12")
      (footprint "RELAY_G2RL-2_12DC")
      (description "SW - Relay 12VDC 8A DPDT (( 29mm 12.7mm 15.7mm)) THT")
      (fields (field (name "LCSC PART #") "C61458") (field (name "MF") "Omron"))
      (libsource (lib "JLC_PCB") (part "G2RL-2-DC12"))
    )
    (comp (ref "MT_KB")
      (value "G2RL-2-DC12")
      (footprint "RELAY_G2RL-2_12DC")
      (description "SW - Relay 12VDC 8A DPDT (( 29mm 12.7mm 15.7mm)) THT")
      (fields (field (name "LCSC PART #") "C61458") (field (name "MF") "Omron"))
      (libsource (lib "JLC_PCB") (part "G2RL-2-DC12"))
    )
    (comp (ref "MT_L_TA")
      (value "10uH")
      (footprint "L_0603")
      (description "L - INDUCTOR - 10uH - 0603")
      (fields (field (name "LCSC PART #") "C1035") (field (name "Comment") "SDFL1608S100KTF"))
      (libsource (lib "JLC_PCB") (part "SDFL1608S100KTF"))
    )
    (comp (ref "MT_POL_R")
      (value "1k")
      (footprint "R_0402")
      (description "R - RESISTOR - SMD - 1k - 1% - 0402")
      (fields (field (name "LCSC PART #") "C11702") (field (name "Comment") "0402WGF1001TCE"))
      (libsource (lib "JLC_PCB") (part "0402WGF1001TCE"))
    )
    (comp (ref "MT_POL_R_N")
      (value "1k")
      (footprint "R_0402")
      (description "R - RESISTOR - SMD - 1k - 1% - 0402")
      (fields (field (name "LCSC PART #") "C11702") (field (name "Comment") "0402WGF1001TCE"))
      (libsource (lib "JLC_PCB") (part "0402WGF1001TCE"))
    )
    (comp (ref "MT_Q1")
      (value "CRSS042N10N")
      (footprint "TO-263-3")
      (description "Q - TRANSISTOR - MOSFET (N) - 100V - 120A - 0.005R")
      (fields (field (name "LCSC PART #") "C410926"))
      (libsource (lib "JLC_PCB") (part "CRSS042N10N"))
    )
    (comp (ref "MT_Q2")
      (value "CRSS042N10N")
      (footprint "TO-263-3")
      (description "Q - TRANSISTOR - MOSFET (N) - 100V - 120A - 0.005R")
      (fields (field (name "LCSC PART #") "C410926"))
      (libsource (lib "JLC_PCB") (part "CRSS042N10N"))
    )
    (comp (ref "MT_Q3")
      (value "CRSS042N10N")
      (footprint "TO-263-3")
      (description "Q - TRANSISTOR - MOSFET (N) - 100V - 120A - 0.005R")
      (fields (field (name "LCSC PART #") "C410926"))
      (libsource (lib "JLC_PCB") (part "CRSS042N10N"))
    )
    (comp (ref "MT_Q4")
      (value "CRSS042N10N")
      (footprint "TO-263-3")
      (description "Q - TRANSISTOR - MOSFET (N) - 100V - 120A - 0.005R")
      (fields (field (name "LCSC PART #") "C410926"))
      (libsource (lib "JLC_PCB") (part "CRSS042N10N"))
    )
    (comp (ref "MT_Q_ECON_A")
      (value "2N7002")
      (footprint "TO-236AB")
      (description "Q - TRANSISTOR - MOSFET (N) - 60V - 200mW")
      (fields (field (name "LCSC PART #") "C8545"))
      (libsource (lib "JLC_PCB") (part "2N7002"))
    )
    (comp (ref "MT_Q_ECON_B")
      (value "HSS0127")
      (footprint "TO-236AB")
      (description "Q - TRANSISTOR - MOSFET (P) - 100V - 0.9A - 0.65 Ohm")
      (fields (field (name "LCSC PART #") "C700960"))
      (libsource (lib "JLC_PCB") (part "HSS0127"))
    )
    (comp (ref "MT_Q_KA")
      (value "2N7002")
      (footprint "TO-236AB")
      (description "Q - TRANSISTOR - MOSFET (N) - 60V - 200mW")
      (fields (field (name "LCSC PART #") "C8545"))
      (libsource (lib "JLC_PCB") (part "2N7002"))
    )
    (comp (ref "MT_Q_KB")
      (value "2N7002")
      (footprint "TO-236AB")
      (description "Q - TRANSISTOR - MOSFET (N) - 60V - 200mW")
      (fields (field (name "LCSC PART #") "C8545"))
      (libsource (lib "JLC_PCB") (part "2N7002"))
    )
    (comp (ref "MT_Q_SHDN")
      (value "2N7002")
      (footprint "TO-236AB")
      (description "Q - TRANSISTOR - MOSFET (N) - 60V - 200mW")
      (fields (field (name "LCSC PART #") "C8545"))
      (libsource (lib "JLC_PCB") (part "2N7002"))
    )
    (comp (ref "MT_Q_SWEN_A")
      (value "2N7002")
      (footprint "TO-236AB")
      (description "Q - TRANSISTOR - MOSFET (N) - 60V - 200mW")
      (fields (field (name "LCSC PART #") "C8545"))
      (libsource (lib "JLC_PCB") (part "2N7002"))
    )
    (comp (ref "MT_Q_SWEN_B")
      (value "HSS0127")
      (footprint "TO-236AB")
      (description "Q - TRANSISTOR - MOSFET (P) - 100V - 0.9A - 0.65 Ohm")
      (fields (field (name "LCSC PART #") "C700960"))
      (libsource (lib "JLC_PCB") (part "HSS0127"))
    )
    (comp (ref "MT_Q_VINR")
      (value "2N7002")
      (footprint "TO-236AB")
      (description "Q - TRANSISTOR - MOSFET (N) - 60V - 200mW")
      (fields (field (name "LCSC PART #") "C8545"))
      (libsource (lib "JLC_PCB") (part "2N7002"))
    )
    (comp (ref "MT_REG_THREE")
      (value "AMS1117-3.3")
      (footprint "SILICON:TO-261AA")
      (description "U - IC - LDO - 3.3V - 800mA")
      (fields (field (name "LCSC PART #") "C6186"))
      (libsource (lib "JLC_PCB") (part "AMS1117-3.3"))
    )
    (comp (ref "MT_RT_TA")
      (value "10k")
      (footprint "R_0402")
      (description "RT - NTC THERMISTOR - 10k - 1% - 0402")
      (fields (field (name "LCSC PART #") "C77131") (field (name "Comment") "NCP15XH103F03RC"))
      (libsource (lib "JLC_PCB") (part "NCP15XH103F03RC"))
    )
    (comp (ref "MT_RT_TB")
      (value "10k")
      (footprint "R_0402")
      (description "RT - NTC THERMISTOR - 10k - 1% - 0402")
      (fields (field (name "LCSC PART #") "C77131") (field (name "Comment") "NCP15XH103F03RC"))
      (libsource (lib "JLC_PCB") (part "NCP15XH103F03RC"))
    )
    (comp (ref "MT_RT_TD")
      (value "10k")
      (footprint "R_0402")
      (description "RT - NTC THERMISTOR - 10k - 1% - 0402")
      (fields (field (name "LCSC PART #") "C77131") (field (name "Comment") "NCP15XH103F03RC"))
      (libsource (lib "JLC_PCB") (part "NCP15XH103F03RC"))
    )
    (comp (ref "MT_RT_TE")
      (value "10k")
      (footprint "R_0402")
      (description "RT - NTC THERMISTOR - 10k - 1% - 0402")
      (fields (field (name "LCSC PART #") "C77131") (field (name "Comment") "NCP15XH103F03RC"))
      (libsource (lib "JLC_PCB") (part "NCP15XH103F03RC"))
    )
    (comp (ref "MT_RT_TG")
      (value "10k")
      (footprint "R_0402")
      (description "RT - NTC THERMISTOR - 10k - 1% - 0402")
      (fields (field (name "LCSC PART #") "C77131") (field (name "Comment") "NCP15XH103F03RC"))
      (libsource (lib "JLC_PCB") (part "NCP15XH103F03RC"))
    )
    (comp (ref "MT_RT_TJ")
      (value "10k")
      (footprint "R_0402")
      (description "RT - NTC THERMISTOR - 10k - 1% - 0402")
      (fields (field (name "LCSC PART #") "C77131") (field (name "Comment") "NCP15XH103F03RC"))
      (libsource (lib "JLC_PCB") (part "NCP15XH103F03RC"))
    )
    (comp (ref "MT_RT_TK")
      (value "10k")
      (footprint "R_0402")
      (description "RT - NTC THERMISTOR - 10k - 1% - 0402")
      (fields (field (name "LCSC PART #") "C77131") (field (name "Comment") "NCP15XH103F03RC"))
      (libsource (lib "JLC_PCB") (part "NCP15XH103F03RC"))
    )
    (comp (ref "MT_R_CLKDET")
      (value "51k")
      (footprint "R_0402")
      (description "R - RESISTOR - SMD - 51k - 1% - 0402")
      (fields (field (name "LCSC PART #") "C25794") (field (name "Comment") "0402WGF5102TCE"))
      (libsource (lib "JLC_PCB") (part "0402WGF5102TCE"))
    )
    (comp (ref "MT_R_CS")
      (value "FMF25FPJR005-LH")
      (footprint "R_2512")
      (description "R - RESISTOR - SMD - 0.005R - 1% - 2512 - 2W")
      (fields (field (name "LCSC PART #") "C371096") (field (name "ALTIUM_VALUE") "0.005R"))
      (libsource (lib "JLC_PCB") (part "FMF25FPJR005-LH"))
    )
    (comp (ref "MT_R_CSS_N")
      (value "10R")
      (footprint "R_0402")
      (description "R - RESISTOR - SMD - 10R - 1% - 0402")
      (fields (field (name "LCSC PART #") "C25077") (field (name "Comment") "0402WGF100JTCE"))
      (libsource (lib "JLC_PCB") (part "0402WGF100JTCE"))
    )
    (comp (ref "MT_R_CSS_P")
      (value "10R")
      (footprint "R_0402")
      (description "R - RESISTOR - SMD - 10R - 1% - 0402")
      (fields (field (name "LCSC PART #") "C25077") (field (name "Comment") "0402WGF100JTCE"))
      (libsource (lib "JLC_PCB") (part "0402WGF100JTCE"))
    )
    (comp (ref "MT_R_DACO_A")
      (value "12k")
      (footprint "R_0402")
      (description "R - RESISTOR - SMD - 12k - 1% - 0402")
      (fields (field (name "LCSC PART #") "C25752") (field (name "Comment") "0402WGF1202TCE"))
      (libsource (lib "JLC_PCB") (part "0402WGF1202TCE"))
    )
    (comp (ref "MT_R_ECON_B")
      (value "0R")
      (footprint "R_0402")
      (description "R - RESISTOR - SMD - 0R - 1% - 0402")
      (fields (field (name "LCSC PART #") "C17168") (field (name "Comment") "0402WGF0000TCE"))
      (libsource (lib "JLC_PCB") (part "0402WGF0000TCE"))
    )
    (comp (ref "MT_R_ECON_C")
      (value "100k")
      (footprint "R_0402")
      (description "R - RESISTOR - SMD - 100k - 1% -  0402")
      (fields (field (name "LCSC PART #") "C25741") (field (name "Comment") "0402WGF1003TCE"))
      (libsource (lib "JLC_PCB") (part "0402WGF1003TCE"))
    )
    (comp (ref "MT_R_ECON_D")
      (value "100k")
      (footprint "R_0402")
      (description "R - RESISTOR - SMD - 100k - 1% -  0402")
      (fields (field (name "LCSC PART #") "C25741") (field (name "Comment") "0402WGF1003TCE"))
      (libsource (lib "JLC_PCB") (part "0402WGF1003TCE"))
    )
    (comp (ref "MT_R_ECON_E")
      (value "10R")
      (footprint "R_0402")
      (description "R - RESISTOR - SMD - 10R - 1% - 0402")
      (fields (field (name "LCSC PART #") "C25077") (field (name "Comment") "0402WGF100JTCE"))
      (libsource (lib "JLC_PCB") (part "0402WGF100JTCE"))
    )
    (comp (ref "MT_R_EXTVCC")
      (value "0R")
      (footprint "R_0402")
      (description "R - RESISTOR - SMD - 0R - 1% - 0402")
      (fields (field (name "LCSC PART #") "C17168") (field (name "Comment") "0402WGF0000TCE"))
      (libsource (lib "JLC_PCB") (part "0402WGF0000TCE"))
    )
    (comp (ref "MT_R_FAULT_A")
      (value "1k")
      (footprint "R_0402")
      (description "R - RESISTOR - SMD - 1k - 1% - 0402")
      (fields (field (name "LCSC PART #") "C11702") (field (name "Comment") "0402WGF1001TCE"))
      (libsource (lib "JLC_PCB") (part "0402WGF1001TCE"))
    )
    (comp (ref "MT_R_FAULT_B")
      (value "1k")
      (footprint "R_0402")
      (description "R - RESISTOR - SMD - 1k - 1% - 0402")
      (fields (field (name "LCSC PART #") "C11702") (field (name "Comment") "0402WGF1001TCE"))
      (libsource (lib "JLC_PCB") (part "0402WGF1001TCE"))
    )
    (comp (ref "MT_R_FBIN_A")
      (value "1R")
      (footprint "R_0603")
      (description "R - RESISTOR - SMD - 1R - 1% -  0603")
      (fields (field (name "LCSC PART #") "C22936") (field (name "Comment") "0603WAF100KT5E"))
      (libsource (lib "JLC_PCB") (part "0603WAF100KT5E"))
    )
    (comp (ref "MT_R_FBIN_B")
      (value "3.3k")
      (footprint "R_0603")
      (description "R - RESISTOR - SMD - 3.3k - 1% - 0603")
      (fields (field (name "LCSC PART #") "C22978") (field (name "Comment") "0603WAF3301T5E"))
      (libsource (lib "JLC_PCB") (part "0603WAF3301T5E"))
    )
    (comp (ref "MT_R_FBIN_C")
      (value "15k")
      (footprint "R_0402")
      (description "R - RESISTOR - SMD - 15k - 1% - 0402")
      (fields (field (name "LCSC PART #") "C25756") (field (name "Comment") "0402WGF1502TCE"))
      (libsource (lib "JLC_PCB") (part "0402WGF1502TCE"))
    )
    (comp (ref "MT_R_FBIR")
      (value "0R")
      (footprint "R_0402")
      (description "R - RESISTOR - SMD - 0R - 1% - 0402")
      (fields (field (name "LCSC PART #") "C17168") (field (name "Comment") "0402WGF0000TCE"))
      (libsource (lib "JLC_PCB") (part "0402WGF0000TCE"))
    )
    (comp (ref "MT_R_FBIW_A")
      (value "1.5k")
      (footprint "R_0402")
      (description "R - RESISTOR - SMD - 1.5k - 1% - 0402")
      (fields (field (name "LCSC PART #") "C25867") (field (name "Comment") "0402WGF1501TCE"))
      (libsource (lib "JLC_PCB") (part "0402WGF1501TCE"))
    )
    (comp (ref "MT_R_FBOUT_AA")
      (value "1M")
      (footprint "R_0603")
      (description "R - RESISTOR - SMD - 1M - 1% - 0603")
      (fields (field (name "LCSC PART #") "C22935") (field (name "Comment") "0603WAF1004T5E"))
      (libsource (lib "JLC_PCB") (part "0603WAF1004T5E"))
    )
    (comp (ref "MT_R_FBOUT_AB")
      (value "1M")
      (footprint "R_0603")
      (description "R - RESISTOR - SMD - 1M - 1% - 0603")
      (fields (field (name "LCSC PART #") "C22935") (field (name "Comment") "0603WAF1004T5E"))
      (libsource (lib "JLC_PCB") (part "0603WAF1004T5E"))
    )
    (comp (ref "MT_R_FBOUT_B")
      (value "12k")
      (footprint "R_0402")
      (description "R - RESISTOR - SMD - 12k - 1% - 0402")
      (fields (field (name "LCSC PART #") "C25752") (field (name "Comment") "0402WGF1202TCE"))
      (libsource (lib "JLC_PCB") (part "0402WGF1202TCE"))
    )
    (comp (ref "MT_R_FBOUT_C")
      (value "100k")
      (footprint "R_0402")
      (description "R - RESISTOR - SMD - 100k - 1% -  0402")
      (fields (field (name "LCSC PART #") "C25741") (field (name "Comment") "0402WGF1003TCE"))
      (libsource (lib "JLC_PCB") (part "0402WGF1003TCE"))
    )
    (comp (ref "MT_R_FT")
      (value "0R")
      (footprint "R_0402")
      (description "R - RESISTOR - SMD - 0R - 1% - 0402")
      (fields (field (name "LCSC PART #") "C17168") (field (name "Comment") "0402WGF0000TCE"))
      (libsource (lib "JLC_PCB") (part "0402WGF0000TCE"))
    )
    (comp (ref "MT_R_FV")
      (value "0R")
      (footprint "R_0402")
      (description "R - RESISTOR - SMD - 0R - 1% - 0402")
      (fields (field (name "LCSC PART #") "C17168") (field (name "Comment") "0402WGF0000TCE"))
      (libsource (lib "JLC_PCB") (part "0402WGF0000TCE"))
    )
    (comp (ref "MT_R_GVCC")
      (value "1R")
      (footprint "R_0603")
      (description "R - RESISTOR - SMD - 1R - 1% -  0603")
      (fields (field (name "LCSC PART #") "C22936") (field (name "Comment") "0603WAF100KT5E"))
      (libsource (lib "JLC_PCB") (part "0603WAF100KT5E"))
    )
    (comp (ref "MT_R_IMON_IN")
      (value "22k")
      (footprint "R_0402")
      (description "R - RESISTOR - SMD - 22k - 1% - 0402")
      (fields (field (name "LCSC PART #") "C25768") (field (name "Comment") "0402WGF2202TCE"))
      (libsource (lib "JLC_PCB") (part "0402WGF2202TCE"))
    )
    (comp (ref "MT_R_IMON_OUT")
      (value "56k")
      (footprint "R_0402")
      (description "R - RESISTOR - SMD - 56k - 1% - 0402")
      (fields (field (name "LCSC PART #") "C25796") (field (name "Comment") "0402WGF5602TCE"))
      (libsource (lib "JLC_PCB") (part "0402WGF5602TCE"))
    )
    (comp (ref "MT_R_IOR")
      (value "3.3k")
      (footprint "R_0402")
      (description "R - RESISTOR - SMD - 3.3k - 1% - 0402")
      (fields (field (name "LCSC PART #") "C25890") (field (name "Comment") "0402WGF3301TCE"))
      (libsource (lib "JLC_PCB") (part "0402WGF3301TCE"))
    )
    (comp (ref "MT_R_IOW")
      (value "47k")
      (footprint "R_0402")
      (description "R - RESISTOR - SMD - 47k - 1% - 0402")
      (fields (field (name "LCSC PART #") "C25792") (field (name "Comment") "0402WGF4702TCE"))
      (libsource (lib "JLC_PCB") (part "0402WGF4702TCE"))
    )
    (comp (ref "MT_R_KA")
      (value "10k")
      (footprint "R_0402")
      (description "R - RESISTOR - SMD - 10k - 1% - 0402")
      (fields (field (name "LCSC PART #") "C25744") (field (name "Comment") "0402WGF1002TCE"))
      (libsource (lib "JLC_PCB") (part "0402WGF1002TCE"))
    )
    (comp (ref "MT_R_KB")
      (value "10k")
      (footprint "R_0402")
      (description "R - RESISTOR - SMD - 10k - 1% - 0402")
      (fields (field (name "LCSC PART #") "C25744") (field (name "Comment") "0402WGF1002TCE"))
      (libsource (lib "JLC_PCB") (part "0402WGF1002TCE"))
    )
    (comp (ref "MT_R_MODE_A")
      (value "220k")
      (footprint "R_0402")
      (description "R - RESISTOR - SMD - 220k - 1% - 0402")
      (fields (field (name "LCSC PART #") "C25767") (field (name "Comment") "0402WGF2203TCE"))
      (libsource (lib "JLC_PCB") (part "0402WGF2203TCE"))
    )
    (comp (ref "MT_R_MODE_B")
      (value "0R")
      (footprint "R_0402")
      (description "R - RESISTOR - SMD - 0R - 1% - 0402")
      (fields (field (name "LCSC PART #") "C17168") (field (name "Comment") "0402WGF0000TCE"))
      (libsource (lib "JLC_PCB") (part "0402WGF0000TCE"))
    )
    (comp (ref "MT_R_POL_N")
      (value "0R")
      (footprint "R_0402")
      (description "R - RESISTOR - SMD - 0R - 1% - 0402")
      (fields (field (name "LCSC PART #") "C17168") (field (name "Comment") "0402WGF0000TCE"))
      (libsource (lib "JLC_PCB") (part "0402WGF0000TCE"))
    )
    (comp (ref "MT_R_POL_P")
      (value "0R")
      (footprint "R_0402")
      (description "R - RESISTOR - SMD - 0R - 1% - 0402")
      (fields (field (name "LCSC PART #") "C17168") (field (name "Comment") "0402WGF0000TCE"))
      (libsource (lib "JLC_PCB") (part "0402WGF0000TCE"))
    )
    (comp (ref "MT_R_SHDN_A")
      (value "1R")
      (footprint "R_0603")
      (description "R - RESISTOR - SMD - 1R - 1% -  0603")
      (fields (field (name "LCSC PART #") "C22936") (field (name "Comment") "0603WAF100KT5E"))
      (libsource (lib "JLC_PCB") (part "0603WAF100KT5E"))
    )
    (comp (ref "MT_R_SHDN_B")
      (value "33k")
      (footprint "R_0402")
      (description "R - RESISTOR - SMD - 33k - 1% - 0402")
      (fields (field (name "LCSC PART #") "C25779") (field (name "Comment") "0402WGF3302TCE"))
      (libsource (lib "JLC_PCB") (part "0402WGF3302TCE"))
    )
    (comp (ref "MT_R_SHDN_C")
      (value "10k")
      (footprint "R_0402")
      (description "R - RESISTOR - SMD - 10k - 1% - 0402")
      (fields (field (name "LCSC PART #") "C25744") (field (name "Comment") "0402WGF1002TCE"))
      (libsource (lib "JLC_PCB") (part "0402WGF1002TCE"))
    )
    (comp (ref "MT_R_STATUS_A")
      (value "1k")
      (footprint "R_0402")
      (description "R - RESISTOR - SMD - 1k - 1% - 0402")
      (fields (field (name "LCSC PART #") "C11702") (field (name "Comment") "0402WGF1001TCE"))
      (libsource (lib "JLC_PCB") (part "0402WGF1001TCE"))
    )
    (comp (ref "MT_R_STATUS_B")
      (value "1k")
      (footprint "R_0402")
      (description "R - RESISTOR - SMD - 1k - 1% - 0402")
      (fields (field (name "LCSC PART #") "C11702") (field (name "Comment") "0402WGF1001TCE"))
      (libsource (lib "JLC_PCB") (part "0402WGF1001TCE"))
    )
    (comp (ref "MT_R_SWEN_B")
      (value "0R")
      (footprint "R_0402")
      (description "R - RESISTOR - SMD - 0R - 1% - 0402")
      (fields (field (name "LCSC PART #") "C17168") (field (name "Comment") "0402WGF0000TCE"))
      (libsource (lib "JLC_PCB") (part "0402WGF0000TCE"))
    )
    (comp (ref "MT_R_SWEN_C")
      (value "100k")
      (footprint "R_0402")
      (description "R - RESISTOR - SMD - 100k - 1% -  0402")
      (fields (field (name "LCSC PART #") "C25741") (field (name "Comment") "0402WGF1003TCE"))
      (libsource (lib "JLC_PCB") (part "0402WGF1003TCE"))
    )
    (comp (ref "MT_R_SWEN_D")
      (value "100k")
      (footprint "R_0402")
      (description "R - RESISTOR - SMD - 100k - 1% -  0402")
      (fields (field (name "LCSC PART #") "C25741") (field (name "Comment") "0402WGF1003TCE"))
      (libsource (lib "JLC_PCB") (part "0402WGF1003TCE"))
    )
    (comp (ref "MT_R_T")
      (value "220k")
      (footprint "R_0402")
      (description "R - RESISTOR - SMD - 220k - 1% - 0402")
      (fields (field (name "LCSC PART #") "C25767") (field (name "Comment") "0402WGF2203TCE"))
      (libsource (lib "JLC_PCB") (part "0402WGF2203TCE"))
    )
    (comp (ref "MT_R_TA")
      (value "10k")
      (footprint "R_0402")
      (description "R - RESISTOR - SMD - 10k - 1% - 0402")
      (fields (field (name "LCSC PART #") "C25744") (field (name "Comment") "0402WGF1002TCE"))
      (libsource (lib "JLC_PCB") (part "0402WGF1002TCE"))
    )
    (comp (ref "MT_R_TB")
      (value "10k")
      (footprint "R_0402")
      (description "R - RESISTOR - SMD - 10k - 1% - 0402")
      (fields (field (name "LCSC PART #") "C25744") (field (name "Comment") "0402WGF1002TCE"))
      (libsource (lib "JLC_PCB") (part "0402WGF1002TCE"))
    )
    (comp (ref "MT_R_TD")
      (value "10k")
      (footprint "R_0402")
      (description "R - RESISTOR - SMD - 10k - 1% - 0402")
      (fields (field (name "LCSC PART #") "C25744") (field (name "Comment") "0402WGF1002TCE"))
      (libsource (lib "JLC_PCB") (part "0402WGF1002TCE"))
    )
    (comp (ref "MT_R_TE")
      (value "10k")
      (footprint "R_0402")
      (description "R - RESISTOR - SMD - 10k - 1% - 0402")
      (fields (field (name "LCSC PART #") "C25744") (field (name "Comment") "0402WGF1002TCE"))
      (libsource (lib "JLC_PCB") (part "0402WGF1002TCE"))
    )
    (comp (ref "MT_R_TEMP_A")
      (value "10k")
      (footprint "R_0402")
      (description "R - RESISTOR - SMD - 10k - 1% - 0402")
      (fields (field (name "LCSC PART #") "C25744") (field (name "Comment") "0402WGF1002TCE"))
      (libsource (lib "JLC_PCB") (part "0402WGF1002TCE"))
    )
    (comp (ref "MT_R_TEMP_B")
      (value "12k")
      (footprint "R_0402")
      (description "R - RESISTOR - SMD - 12k - 1% - 0402")
      (fields (field (name "LCSC PART #") "C25752") (field (name "Comment") "0402WGF1202TCE"))
      (libsource (lib "JLC_PCB") (part "0402WGF1202TCE"))
    )
    (comp (ref "MT_R_TG")
      (value "10k")
      (footprint "R_0402")
      (description "R - RESISTOR - SMD - 10k - 1% - 0402")
      (fields (field (name "LCSC PART #") "C25744") (field (name "Comment") "0402WGF1002TCE"))
      (libsource (lib "JLC_PCB") (part "0402WGF1002TCE"))
    )
    (comp (ref "MT_R_THREE")
      (value "0R")
      (footprint "R_0402")
      (description "R - RESISTOR - SMD - 0R - 1% - 0402")
      (fields (field (name "LCSC PART #") "C17168") (field (name "Comment") "0402WGF0000TCE"))
      (libsource (lib "JLC_PCB") (part "0402WGF0000TCE"))
    )
    (comp (ref "MT_R_TJ")
      (value "10k")
      (footprint "R_0402")
      (description "R - RESISTOR - SMD - 10k - 1% - 0402")
      (fields (field (name "LCSC PART #") "C25744") (field (name "Comment") "0402WGF1002TCE"))
      (libsource (lib "JLC_PCB") (part "0402WGF1002TCE"))
    )
    (comp (ref "MT_R_TK")
      (value "10k")
      (footprint "R_0402")
      (description "R - RESISTOR - SMD - 10k - 1% - 0402")
      (fields (field (name "LCSC PART #") "C25744") (field (name "Comment") "0402WGF1002TCE"))
      (libsource (lib "JLC_PCB") (part "0402WGF1002TCE"))
    )
    (comp (ref "MT_R_TWELVE")
      (value "0R")
      (footprint "R_0402")
      (description "R - RESISTOR - SMD - 0R - 1% - 0402")
      (fields (field (name "LCSC PART #") "C17168") (field (name "Comment") "0402WGF0000TCE"))
      (libsource (lib "JLC_PCB") (part "0402WGF0000TCE"))
    )
    (comp (ref "MT_R_VC")
      (value "10k")
      (footprint "R_0402")
      (description "R - RESISTOR - SMD - 10k - 1% - 0402")
      (fields (field (name "LCSC PART #") "C25744") (field (name "Comment") "0402WGF1002TCE"))
      (libsource (lib "JLC_PCB") (part "0402WGF1002TCE"))
    )
    (comp (ref "MT_R_VINR")
      (value "10k")
      (footprint "R_0402")
      (description "R - RESISTOR - SMD - 10k - 1% - 0402")
      (fields (field (name "LCSC PART #") "C25744") (field (name "Comment") "0402WGF1002TCE"))
      (libsource (lib "JLC_PCB") (part "0402WGF1002TCE"))
    )
    (comp (ref "MT_R_VINR_A")
      (value "220k")
      (footprint "R_0402")
      (description "R - RESISTOR - SMD - 220k - 1% - 0402")
      (fields (field (name "LCSC PART #") "C25767") (field (name "Comment") "0402WGF2203TCE"))
      (libsource (lib "JLC_PCB") (part "0402WGF2203TCE"))
    )
    (comp (ref "MT_R_VINR_B")
      (value "10k")
      (footprint "R_0402")
      (description "R - RESISTOR - SMD - 10k - 1% - 0402")
      (fields (field (name "LCSC PART #") "C25744") (field (name "Comment") "0402WGF1002TCE"))
      (libsource (lib "JLC_PCB") (part "0402WGF1002TCE"))
    )
    (comp (ref "MT_R_VINR_C")
      (value "22k")
      (footprint "R_0402")
      (description "R - RESISTOR - SMD - 22k - 1% - 0402")
      (fields (field (name "LCSC PART #") "C25768") (field (name "Comment") "0402WGF2202TCE"))
      (libsource (lib "JLC_PCB") (part "0402WGF2202TCE"))
    )
    (comp (ref "MT_R_VIN_A")
      (value "0R")
      (footprint "R_0603")
      (description "R - RESISTOR - SMD - 0R - 1% - 0603")
      (fields (field (name "LCSC PART #") "C21189") (field (name "Comment") "0603WAF0000T5E"))
      (libsource (lib "JLC_PCB") (part "0603WAF0000T5E"))
    )
    (comp (ref "MT_R_VIN_B")
      (value "10R")
      (footprint "R_0603")
      (description "R - RESISTOR - SMD - 10 - 1% - 0603")
      (fields (field (name "LCSC PART #") "C22859") (field (name "Comment") "0603WAF820JT5E"))
      (libsource (lib "JLC_PCB") (part "0603WAF820JT5E"))
    )
    (comp (ref "MT_R_VOUT_A")
      (value "0R")
      (footprint "R_0603")
      (description "R - RESISTOR - SMD - 0R - 1% - 0603")
      (fields (field (name "LCSC PART #") "C21189") (field (name "Comment") "0603WAF0000T5E"))
      (libsource (lib "JLC_PCB") (part "0603WAF0000T5E"))
    )
    (comp (ref "MT_R_VOUT_B")
      (value "10R")
      (footprint "R_0603")
      (description "R - RESISTOR - SMD - 10 - 1% - 0603")
      (fields (field (name "LCSC PART #") "C22859") (field (name "Comment") "0603WAF820JT5E"))
      (libsource (lib "JLC_PCB") (part "0603WAF820JT5E"))
    )
    (comp (ref "MT_R_WAKE_A")
      (value "0R")
      (footprint "R_0402")
      (description "R - RESISTOR - SMD - 0R - 1% - 0402")
      (fields (field (name "LCSC PART #") "C17168") (field (name "Comment") "0402WGF0000TCE"))
      (libsource (lib "JLC_PCB") (part "0402WGF0000TCE"))
    )
    (comp (ref "MT_R_WAKE_B")
      (value "0R")
      (footprint "R_0402")
      (description "R - RESISTOR - SMD - 0R - 1% - 0402")
      (fields (field (name "LCSC PART #") "C17168") (field (name "Comment") "0402WGF0000TCE"))
      (libsource (lib "JLC_PCB") (part "0402WGF0000TCE"))
    )
    (comp (ref "MT_SWEN")
      (value "220k")
      (footprint "R_0402")
      (description "R - RESISTOR - SMD - 220k - 1% - 0402")
      (fields (field (name "LCSC PART #") "C25767") (field (name "Comment") "0402WGF2203TCE"))
      (libsource (lib "JLC_PCB") (part "0402WGF2203TCE"))
    )
    (comp (ref "MT_U_AMP")
      (value "LM324APWR")
      (footprint "SILICON:TSSOP-14-P0.65MM-W4.4MM")
      (description "U - IC - OP AMP (QUAD)")
      (fields (field (name "LCSC PART #") "C350548"))
      (libsource (lib "JLC_PCB") (part "LM324APWR"))
    )
    (comp (ref "MT_U_T")
      (value "74HC4067PW,118")
      (footprint "SILICON:TSSOP-24-P0.65MM-W4.4MM")
      (description "U - IC -16 Port Analog MUX")
      (fields (field (name "LCSC PART #") "C179326"))
      (libsource (lib "JLC_PCB") (part "74HC4067PW,118"))
    )
    (comp (ref "Q_LEDA")
      (value "2N7002")
      (footprint "TO-236AB")
      (description "Q - TRANSISTOR - MOSFET (N) - 60V - 200mW")
      (fields (field (name "LCSC PART #") "C8545"))
      (libsource (lib "JLC_PCB") (part "2N7002"))
    )
    (comp (ref "Q_LEDB")
      (value "2N7002")
      (footprint "TO-236AB")
      (description "Q - TRANSISTOR - MOSFET (N) - 60V - 200mW")
      (fields (field (name "LCSC PART #") "C8545"))
      (libsource (lib "JLC_PCB") (part "2N7002"))
    )
    (comp (ref "Q_LEDVSS")
      (value "2N7002")
      (footprint "TO-236AB")
      (description "Q - TRANSISTOR - MOSFET (N) - 60V - 200mW")
      (fields (field (name "LCSC PART #") "C8545"))
      (libsource (lib "JLC_PCB") (part "2N7002"))
    )
    (comp (ref "R1")
      (value "FMF25FPJR005-LH")
      (footprint "R_2512")
      (description "R - RESISTOR - SMD - 0.005R - 1% - 2512 - 2W")
      (fields (field (name "LCSC PART #") "C371096") (field (name "ALTIUM_VALUE") "0.005R"))
      (libsource (lib "JLC_PCB") (part "FMF25FPJR005-LH"))
    )
    (comp (ref "R10")
      (value "FMF25FPJR005-LH")
      (footprint "R_2512")
      (description "R - RESISTOR - SMD - 0.005R - 1% - 2512 - 2W")
      (fields (field (name "LCSC PART #") "C371096") (field (name "ALTIUM_VALUE") "0.005R"))
      (libsource (lib "JLC_PCB") (part "FMF25FPJR005-LH"))
    )
    (comp (ref "R100")
      (value "100R")
      (footprint "R_0402")
      (description "R - RESISTOR - SMD - 100R - 1% - 0402")
      (fields (field (name "LCSC PART #") "C25076") (field (name "Comment") "0402WGF1000TCE"))
      (libsource (lib "JLC_PCB") (part "0402WGF1000TCE"))
    )
    (comp (ref "R101")
      (value "100R")
      (footprint "R_0402")
      (description "R - RESISTOR - SMD - 100R - 1% - 0402")
      (fields (field (name "LCSC PART #") "C25076") (field (name "Comment") "0402WGF1000TCE"))
      (libsource (lib "JLC_PCB") (part "0402WGF1000TCE"))
    )
    (comp (ref "R102")
      (value "100R")
      (footprint "R_0402")
      (description "R - RESISTOR - SMD - 100R - 1% - 0402")
      (fields (field (name "LCSC PART #") "C25076") (field (name "Comment") "0402WGF1000TCE"))
      (libsource (lib "JLC_PCB") (part "0402WGF1000TCE"))
    )
    (comp (ref "R103")
      (value "100R")
      (footprint "R_0402")
      (description "R - RESISTOR - SMD - 100R - 1% - 0402")
      (fields (field (name "LCSC PART #") "C25076") (field (name "Comment") "0402WGF1000TCE"))
      (libsource (lib "JLC_PCB") (part "0402WGF1000TCE"))
    )
    (comp (ref "R110")
      (value "10R")
      (footprint "R_1206")
      (description "R - RESISTOR - SMD - 10R - 1% - 1206")
      (fields (field (name "LCSC PART #") "C17903") (field (name "Comment") "1206W4F100JT5E"))
      (libsource (lib "JLC_PCB") (part "1206W4F100JT5E"))
    )
    (comp (ref "R140")
      (value "10R")
      (footprint "R_1206")
      (description "R - RESISTOR - SMD - 10R - 1% - 1206")
      (fields (field (name "LCSC PART #") "C17903") (field (name "Comment") "1206W4F100JT5E"))
      (libsource (lib "JLC_PCB") (part "1206W4F100JT5E"))
    )
    (comp (ref "Rbg1a")
      (value "1R")
      (footprint "R_0603")
      (description "R - RESISTOR - SMD - 1R - 1% -  0603")
      (fields (field (name "LCSC PART #") "C22936") (field (name "Comment") "0603WAF100KT5E"))
      (libsource (lib "JLC_PCB") (part "0603WAF100KT5E"))
    )
    (comp (ref "Rbg1s")
      (value "10k")
      (footprint "R_0402")
      (description "R - RESISTOR - SMD - 10k - 1% - 0402")
      (fields (field (name "LCSC PART #") "C25744") (field (name "Comment") "0402WGF1002TCE"))
      (libsource (lib "JLC_PCB") (part "0402WGF1002TCE"))
    )
    (comp (ref "Rbg2a")
      (value "1R")
      (footprint "R_0603")
      (description "R - RESISTOR - SMD - 1R - 1% -  0603")
      (fields (field (name "LCSC PART #") "C22936") (field (name "Comment") "0603WAF100KT5E"))
      (libsource (lib "JLC_PCB") (part "0603WAF100KT5E"))
    )
    (comp (ref "Rbg2s")
      (value "10k")
      (footprint "R_0402")
      (description "R - RESISTOR - SMD - 10k - 1% - 0402")
      (fields (field (name "LCSC PART #") "C25744") (field (name "Comment") "0402WGF1002TCE"))
      (libsource (lib "JLC_PCB") (part "0402WGF1002TCE"))
    )
    (comp (ref "Rtg1a")
      (value "1R")
      (footprint "R_0603")
      (description "R - RESISTOR - SMD - 1R - 1% -  0603")
      (fields (field (name "LCSC PART #") "C22936") (field (name "Comment") "0603WAF100KT5E"))
      (libsource (lib "JLC_PCB") (part "0603WAF100KT5E"))
    )
    (comp (ref "Rtg1s")
      (value "10k")
      (footprint "R_0402")
      (description "R - RESISTOR - SMD - 10k - 1% - 0402")
      (fields (field (name "LCSC PART #") "C25744") (field (name "Comment") "0402WGF1002TCE"))
      (libsource (lib "JLC_PCB") (part "0402WGF1002TCE"))
    )
    (comp (ref "Rtg2a")
      (value "1R")
      (footprint "R_0603")
      (description "R - RESISTOR - SMD - 1R - 1% -  0603")
      (fields (field (name "LCSC PART #") "C22936") (field (name "Comment") "0603WAF100KT5E"))
      (libsource (lib "JLC_PCB") (part "0603WAF100KT5E"))
    )
    (comp (ref "Rtg2s")
      (value "10k")
      (footprint "R_0402")
      (description "R - RESISTOR - SMD - 10k - 1% - 0402")
      (fields (field (name "LCSC PART #") "C25744") (field (name "Comment") "0402WGF1002TCE"))
      (libsource (lib "JLC_PCB") (part "0402WGF1002TCE"))
    )
    (comp (ref "R_1A_a")
      (value "47k")
      (footprint "R_0402")
      (description "R - RESISTOR - SMD - 47k - 1% - 0402")
      (fields (field (name "LCSC PART #") "C25792") (field (name "Comment") "0402WGF4702TCE"))
      (libsource (lib "JLC_PCB") (part "0402WGF4702TCE"))
    )
    (comp (ref "R_1A_b")
      (value "47k")
      (footprint "R_0402")
      (description "R - RESISTOR - SMD - 47k - 1% - 0402")
      (fields (field (name "LCSC PART #") "C25792") (field (name "Comment") "0402WGF4702TCE"))
      (libsource (lib "JLC_PCB") (part "0402WGF4702TCE"))
    )
    (comp (ref "R_1A_c")
      (value "100k")
      (footprint "R_0402")
      (description "R - RESISTOR - SMD - 100k - 1% -  0402")
      (fields (field (name "LCSC PART #") "C25741") (field (name "Comment") "0402WGF1003TCE"))
      (libsource (lib "JLC_PCB") (part "0402WGF1003TCE"))
    )
    (comp (ref "R_1B_a")
      (value "47k")
      (footprint "R_0402")
      (description "R - RESISTOR - SMD - 47k - 1% - 0402")
      (fields (field (name "LCSC PART #") "C25792") (field (name "Comment") "0402WGF4702TCE"))
      (libsource (lib "JLC_PCB") (part "0402WGF4702TCE"))
    )
    (comp (ref "R_1B_b")
      (value "47k")
      (footprint "R_0402")
      (description "R - RESISTOR - SMD - 47k - 1% - 0402")
      (fields (field (name "LCSC PART #") "C25792") (field (name "Comment") "0402WGF4702TCE"))
      (libsource (lib "JLC_PCB") (part "0402WGF4702TCE"))
    )
    (comp (ref "R_1B_c")
      (value "100k")
      (footprint "R_0402")
      (description "R - RESISTOR - SMD - 100k - 1% -  0402")
      (fields (field (name "LCSC PART #") "C25741") (field (name "Comment") "0402WGF1003TCE"))
      (libsource (lib "JLC_PCB") (part "0402WGF1003TCE"))
    )
    (comp (ref "R_LED_A")
      (value "0R")
      (footprint "R_0402")
      (description "R - RESISTOR - SMD - 0R - 1% - 0402")
      (fields (field (name "LCSC PART #") "C17168") (field (name "Comment") "0402WGF0000TCE"))
      (libsource (lib "JLC_PCB") (part "0402WGF0000TCE"))
    )
    (comp (ref "R_LED_B")
      (value "0R")
      (footprint "R_0402")
      (description "R - RESISTOR - SMD - 0R - 1% - 0402")
      (fields (field (name "LCSC PART #") "C17168") (field (name "Comment") "0402WGF0000TCE"))
      (libsource (lib "JLC_PCB") (part "0402WGF0000TCE"))
    )
    (comp (ref "R_LED_C")
      (value "0R")
      (footprint "R_0402")
      (description "R - RESISTOR - SMD - 0R - 1% - 0402")
      (fields (field (name "LCSC PART #") "C17168") (field (name "Comment") "0402WGF0000TCE"))
      (libsource (lib "JLC_PCB") (part "0402WGF0000TCE"))
    )
    (comp (ref "R_LED_D")
      (value "0R")
      (footprint "R_0402")
      (description "R - RESISTOR - SMD - 0R - 1% - 0402")
      (fields (field (name "LCSC PART #") "C17168") (field (name "Comment") "0402WGF0000TCE"))
      (libsource (lib "JLC_PCB") (part "0402WGF0000TCE"))
    )
    (comp (ref "TWLV_C_AA")
      (value "10uF")
      (footprint "C_0603")
      (description "C - CAPACITOR - MLCC - 10uF - 25V - 0603")
      (fields (field (name "LCSC PART #") "C96446") (field (name "Comment") "CL10A106MA8NRNC"))
      (libsource (lib "JLC_PCB") (part "CL10A106MA8NRNC"))
    )
    (comp (ref "TWLV_C_AB")
      (value "10uF")
      (footprint "C_0603")
      (description "C - CAPACITOR - MLCC - 10uF - 25V - 0603")
      (fields (field (name "LCSC PART #") "C96446") (field (name "Comment") "CL10A106MA8NRNC"))
      (libsource (lib "JLC_PCB") (part "CL10A106MA8NRNC"))
    )
    (comp (ref "TWLV_C_AC")
      (value "10uF")
      (footprint "C_0603")
      (description "C - CAPACITOR - MLCC - 10uF - 25V - 0603")
      (fields (field (name "LCSC PART #") "C96446") (field (name "Comment") "CL10A106MA8NRNC"))
      (libsource (lib "JLC_PCB") (part "CL10A106MA8NRNC"))
    )
    (comp (ref "TWLV_C_AD")
      (value "10uF")
      (footprint "C_0603")
      (description "C - CAPACITOR - MLCC - 10uF - 25V - 0603")
      (fields (field (name "LCSC PART #") "C96446") (field (name "Comment") "CL10A106MA8NRNC"))
      (libsource (lib "JLC_PCB") (part "CL10A106MA8NRNC"))
    )
    (comp (ref "TWLV_C_AE")
      (value "10uF")
      (footprint "C_0603")
      (description "C - CAPACITOR - MLCC - 10uF - 25V - 0603")
      (fields (field (name "LCSC PART #") "C96446") (field (name "Comment") "CL10A106MA8NRNC"))
      (libsource (lib "JLC_PCB") (part "CL10A106MA8NRNC"))
    )
    (comp (ref "TWLV_C_AF")
      (value "10uF")
      (footprint "C_0603")
      (description "C - CAPACITOR - MLCC - 10uF - 25V - 0603")
      (fields (field (name "LCSC PART #") "C96446") (field (name "Comment") "CL10A106MA8NRNC"))
      (libsource (lib "JLC_PCB") (part "CL10A106MA8NRNC"))
    )
    (comp (ref "TWLV_C_AG")
      (value "10uF")
      (footprint "C_0603")
      (description "C - CAPACITOR - MLCC - 10uF - 25V - 0603")
      (fields (field (name "LCSC PART #") "C96446") (field (name "Comment") "CL10A106MA8NRNC"))
      (libsource (lib "JLC_PCB") (part "CL10A106MA8NRNC"))
    )
    (comp (ref "TWLV_C_AH")
      (value "10uF")
      (footprint "C_0603")
      (description "C - CAPACITOR - MLCC - 10uF - 25V - 0603")
      (fields (field (name "LCSC PART #") "C96446") (field (name "Comment") "CL10A106MA8NRNC"))
      (libsource (lib "JLC_PCB") (part "CL10A106MA8NRNC"))
    )
    (comp (ref "TWLV_C_AI")
      (value "10uF")
      (footprint "C_0603")
      (description "C - CAPACITOR - MLCC - 10uF - 25V - 0603")
      (fields (field (name "LCSC PART #") "C96446") (field (name "Comment") "CL10A106MA8NRNC"))
      (libsource (lib "JLC_PCB") (part "CL10A106MA8NRNC"))
    )
    (comp (ref "TWLV_C_AJ")
      (value "10uF")
      (footprint "C_0603")
      (description "C - CAPACITOR - MLCC - 10uF - 25V - 0603")
      (fields (field (name "LCSC PART #") "C96446") (field (name "Comment") "CL10A106MA8NRNC"))
      (libsource (lib "JLC_PCB") (part "CL10A106MA8NRNC"))
    )
    (comp (ref "TWLV_C_AK")
      (value "10uF")
      (footprint "C_0603")
      (description "C - CAPACITOR - MLCC - 10uF - 25V - 0603")
      (fields (field (name "LCSC PART #") "C96446") (field (name "Comment") "CL10A106MA8NRNC"))
      (libsource (lib "JLC_PCB") (part "CL10A106MA8NRNC"))
    )
    (comp (ref "TWLV_C_AL")
      (value "10uF")
      (footprint "C_0603")
      (description "C - CAPACITOR - MLCC - 10uF - 25V - 0603")
      (fields (field (name "LCSC PART #") "C96446") (field (name "Comment") "CL10A106MA8NRNC"))
      (libsource (lib "JLC_PCB") (part "CL10A106MA8NRNC"))
    )
    (comp (ref "TWLV_C_AM")
      (value "10uF")
      (footprint "C_0603")
      (description "C - CAPACITOR - MLCC - 10uF - 25V - 0603")
      (fields (field (name "LCSC PART #") "C96446") (field (name "Comment") "CL10A106MA8NRNC"))
      (libsource (lib "JLC_PCB") (part "CL10A106MA8NRNC"))
    )
    (comp (ref "TWLV_C_AN")
      (value "10uF")
      (footprint "C_0603")
      (description "C - CAPACITOR - MLCC - 10uF - 25V - 0603")
      (fields (field (name "LCSC PART #") "C96446") (field (name "Comment") "CL10A106MA8NRNC"))
      (libsource (lib "JLC_PCB") (part "CL10A106MA8NRNC"))
    )
    (comp (ref "TWLV_C_AO")
      (value "10uF")
      (footprint "C_0603")
      (description "C - CAPACITOR - MLCC - 10uF - 25V - 0603")
      (fields (field (name "LCSC PART #") "C96446") (field (name "Comment") "CL10A106MA8NRNC"))
      (libsource (lib "JLC_PCB") (part "CL10A106MA8NRNC"))
    )
    (comp (ref "TWLV_C_AP")
      (value "10uF")
      (footprint "C_0603")
      (description "C - CAPACITOR - MLCC - 10uF - 25V - 0603")
      (fields (field (name "LCSC PART #") "C96446") (field (name "Comment") "CL10A106MA8NRNC"))
      (libsource (lib "JLC_PCB") (part "CL10A106MA8NRNC"))
    )
    (comp (ref "TWLV_C_AQ")
      (value "10uF")
      (footprint "C_0603")
      (description "C - CAPACITOR - MLCC - 10uF - 25V - 0603")
      (fields (field (name "LCSC PART #") "C96446") (field (name "Comment") "CL10A106MA8NRNC"))
      (libsource (lib "JLC_PCB") (part "CL10A106MA8NRNC"))
    )
    (comp (ref "TWLV_C_AR")
      (value "10uF")
      (footprint "C_0603")
      (description "C - CAPACITOR - MLCC - 10uF - 25V - 0603")
      (fields (field (name "LCSC PART #") "C96446") (field (name "Comment") "CL10A106MA8NRNC"))
      (libsource (lib "JLC_PCB") (part "CL10A106MA8NRNC"))
    )
    (comp (ref "TWLV_C_AS")
      (value "10uF")
      (footprint "C_0603")
      (description "C - CAPACITOR - MLCC - 10uF - 25V - 0603")
      (fields (field (name "LCSC PART #") "C96446") (field (name "Comment") "CL10A106MA8NRNC"))
      (libsource (lib "JLC_PCB") (part "CL10A106MA8NRNC"))
    )
    (comp (ref "TWLV_C_AT")
      (value "10uF")
      (footprint "C_0603")
      (description "C - CAPACITOR - MLCC - 10uF - 25V - 0603")
      (fields (field (name "LCSC PART #") "C96446") (field (name "Comment") "CL10A106MA8NRNC"))
      (libsource (lib "JLC_PCB") (part "CL10A106MA8NRNC"))
    )
    (comp (ref "TWLV_C_AU")
      (value "10uF")
      (footprint "C_0603")
      (description "C - CAPACITOR - MLCC - 10uF - 25V - 0603")
      (fields (field (name "LCSC PART #") "C96446") (field (name "Comment") "CL10A106MA8NRNC"))
      (libsource (lib "JLC_PCB") (part "CL10A106MA8NRNC"))
    )
    (comp (ref "TWLV_C_AV")
      (value "10uF")
      (footprint "C_0603")
      (description "C - CAPACITOR - MLCC - 10uF - 25V - 0603")
      (fields (field (name "LCSC PART #") "C96446") (field (name "Comment") "CL10A106MA8NRNC"))
      (libsource (lib "JLC_PCB") (part "CL10A106MA8NRNC"))
    )
    (comp (ref "TWLV_C_AW")
      (value "10uF")
      (footprint "C_0603")
      (description "C - CAPACITOR - MLCC - 10uF - 25V - 0603")
      (fields (field (name "LCSC PART #") "C96446") (field (name "Comment") "CL10A106MA8NRNC"))
      (libsource (lib "JLC_PCB") (part "CL10A106MA8NRNC"))
    )
    (comp (ref "TWLV_C_AX")
      (value "10uF")
      (footprint "C_0603")
      (description "C - CAPACITOR - MLCC - 10uF - 25V - 0603")
      (fields (field (name "LCSC PART #") "C96446") (field (name "Comment") "CL10A106MA8NRNC"))
      (libsource (lib "JLC_PCB") (part "CL10A106MA8NRNC"))
    )
    (comp (ref "TWLV_C_AY")
      (value "10uF")
      (footprint "C_0603")
      (description "C - CAPACITOR - MLCC - 10uF - 25V - 0603")
      (fields (field (name "LCSC PART #") "C96446") (field (name "Comment") "CL10A106MA8NRNC"))
      (libsource (lib "JLC_PCB") (part "CL10A106MA8NRNC"))
    )
    (comp (ref "TWLV_C_AZ")
      (value "10uF")
      (footprint "C_0603")
      (description "C - CAPACITOR - MLCC - 10uF - 25V - 0603")
      (fields (field (name "LCSC PART #") "C96446") (field (name "Comment") "CL10A106MA8NRNC"))
      (libsource (lib "JLC_PCB") (part "CL10A106MA8NRNC"))
    )
    (comp (ref "TWLV_C_BA")
      (value "10uF")
      (footprint "C_0603")
      (description "C - CAPACITOR - MLCC - 10uF - 25V - 0603")
      (fields (field (name "LCSC PART #") "C96446") (field (name "Comment") "CL10A106MA8NRNC"))
      (libsource (lib "JLC_PCB") (part "CL10A106MA8NRNC"))
    )
    (comp (ref "TWLV_C_BB")
      (value "10uF")
      (footprint "C_0603")
      (description "C - CAPACITOR - MLCC - 10uF - 25V - 0603")
      (fields (field (name "LCSC PART #") "C96446") (field (name "Comment") "CL10A106MA8NRNC"))
      (libsource (lib "JLC_PCB") (part "CL10A106MA8NRNC"))
    )
    (comp (ref "TWLV_C_BC")
      (value "10uF")
      (footprint "C_0603")
      (description "C - CAPACITOR - MLCC - 10uF - 25V - 0603")
      (fields (field (name "LCSC PART #") "C96446") (field (name "Comment") "CL10A106MA8NRNC"))
      (libsource (lib "JLC_PCB") (part "CL10A106MA8NRNC"))
    )
    (comp (ref "TWLV_C_BD")
      (value "10uF")
      (footprint "C_0603")
      (description "C - CAPACITOR - MLCC - 10uF - 25V - 0603")
      (fields (field (name "LCSC PART #") "C96446") (field (name "Comment") "CL10A106MA8NRNC"))
      (libsource (lib "JLC_PCB") (part "CL10A106MA8NRNC"))
    )
    (comp (ref "TWLV_C_BE")
      (value "10uF")
      (footprint "C_0603")
      (description "C - CAPACITOR - MLCC - 10uF - 25V - 0603")
      (fields (field (name "LCSC PART #") "C96446") (field (name "Comment") "CL10A106MA8NRNC"))
      (libsource (lib "JLC_PCB") (part "CL10A106MA8NRNC"))
    )
    (comp (ref "TWLV_C_BF")
      (value "10uF")
      (footprint "C_0603")
      (description "C - CAPACITOR - MLCC - 10uF - 25V - 0603")
      (fields (field (name "LCSC PART #") "C96446") (field (name "Comment") "CL10A106MA8NRNC"))
      (libsource (lib "JLC_PCB") (part "CL10A106MA8NRNC"))
    )
    (comp (ref "TWLV_C_BG")
      (value "10uF")
      (footprint "C_0603")
      (description "C - CAPACITOR - MLCC - 10uF - 25V - 0603")
      (fields (field (name "LCSC PART #") "C96446") (field (name "Comment") "CL10A106MA8NRNC"))
      (libsource (lib "JLC_PCB") (part "CL10A106MA8NRNC"))
    )
    (comp (ref "TWLV_C_BH")
      (value "10uF")
      (footprint "C_0603")
      (description "C - CAPACITOR - MLCC - 10uF - 25V - 0603")
      (fields (field (name "LCSC PART #") "C96446") (field (name "Comment") "CL10A106MA8NRNC"))
      (libsource (lib "JLC_PCB") (part "CL10A106MA8NRNC"))
    )
    (comp (ref "TWLV_C_BI")
      (value "10uF")
      (footprint "C_0603")
      (description "C - CAPACITOR - MLCC - 10uF - 25V - 0603")
      (fields (field (name "LCSC PART #") "C96446") (field (name "Comment") "CL10A106MA8NRNC"))
      (libsource (lib "JLC_PCB") (part "CL10A106MA8NRNC"))
    )
    (comp (ref "TWLV_C_BJ")
      (value "10uF")
      (footprint "C_0603")
      (description "C - CAPACITOR - MLCC - 10uF - 25V - 0603")
      (fields (field (name "LCSC PART #") "C96446") (field (name "Comment") "CL10A106MA8NRNC"))
      (libsource (lib "JLC_PCB") (part "CL10A106MA8NRNC"))
    )
    (comp (ref "TWLV_C_DA")
      (value "1uF")
      (footprint "C_1206")
      (description "C - CAPACITOR - MLCC - 1uF - 100V - 1206 - X7R")
      (fields (field (name "LCSC PART #") "C91151") (field (name "Comment") "1206B105K101NT"))
      (libsource (lib "JLC_PCB") (part "1206B105K101NT"))
    )
    (comp (ref "TWLV_C_DB")
      (value "1uF")
      (footprint "C_1206")
      (description "C - CAPACITOR - MLCC - 1uF - 100V - 1206 - X7R")
      (fields (field (name "LCSC PART #") "C91151") (field (name "Comment") "1206B105K101NT"))
      (libsource (lib "JLC_PCB") (part "1206B105K101NT"))
    )
    (comp (ref "TWLV_C_DC")
      (value "1uF")
      (footprint "C_1206")
      (description "C - CAPACITOR - MLCC - 1uF - 100V - 1206 - X7R")
      (fields (field (name "LCSC PART #") "C91151") (field (name "Comment") "1206B105K101NT"))
      (libsource (lib "JLC_PCB") (part "1206B105K101NT"))
    )
    (comp (ref "TWLV_C_DD")
      (value "1uF")
      (footprint "C_1206")
      (description "C - CAPACITOR - MLCC - 1uF - 100V - 1206 - X7R")
      (fields (field (name "LCSC PART #") "C91151") (field (name "Comment") "1206B105K101NT"))
      (libsource (lib "JLC_PCB") (part "1206B105K101NT"))
    )
    (comp (ref "TWLV_D_A")
      (value "SS210")
      (footprint "DO-214AC")
      (description "D - DIODE - SCHOTTKY - 100V - 2A")
      (fields (field (name "LCSC PART #") "C14996"))
      (libsource (lib "JLC_PCB") (part "SS210"))
    )
    (comp (ref "TWLV_L_A")
      (value "220uH")
      (footprint "SRR1260")
      (description "L - INDUCTOR - 220uH - 1.6A - 12.5mm")
      (fields (field (name "LCSC PART #") "C169380") (field (name "Comment") "SWRB1207S-221MT"))
      (libsource (lib "JLC_PCB") (part "SWRB1207S-221MT"))
    )
    (comp (ref "TWLV_Q_A")
      (value "2N7002")
      (footprint "TO-236AB")
      (description "Q - TRANSISTOR - MOSFET (N) - 60V - 200mW")
      (fields (field (name "LCSC PART #") "C8545"))
      (libsource (lib "JLC_PCB") (part "2N7002"))
    )
    (comp (ref "TWLV_R_A")
      (value "1M")
      (footprint "R_0402")
      (description "R - RESISTOR - SMD - 1M - 1% - 0402")
      (fields (field (name "LCSC PART #") "C26083") (field (name "Comment") "0402WGF1004TCE"))
      (libsource (lib "JLC_PCB") (part "0402WGF1004TCE"))
    )
    (comp (ref "TWLV_R_B")
      (value "220k")
      (footprint "R_0402")
      (description "R - RESISTOR - SMD - 220k - 1% - 0402")
      (fields (field (name "LCSC PART #") "C25767") (field (name "Comment") "0402WGF2203TCE"))
      (libsource (lib "JLC_PCB") (part "0402WGF2203TCE"))
    )
    (comp (ref "TWLV_R_C")
      (value "1.2k")
      (footprint "R_0402")
      (description "R - RESISTOR - SMD - 1.2k - 1% - 0402")
      (fields (field (name "LCSC PART #") "C25862") (field (name "Comment") "0402WGF1201TCE"))
      (libsource (lib "JLC_PCB") (part "0402WGF1201TCE"))
    )
    (comp (ref "TWLV_R_D")
      (value "390R")
      (footprint "R_0603")
      (description "R - RESISTOR - SMD - 390R - 1% - 0603")
      (fields (field (name "LCSC PART #") "C23151") (field (name "Comment") "0603WAF3900T5E"))
      (libsource (lib "JLC_PCB") (part "0603WAF3900T5E"))
    )
    (comp (ref "TWLV_R_E")
      (value "0.1R")
      (footprint "R_1206")
      (description "R - RESISTOR - SMD - 0.1R - 1% - 1206")
      (fields (field (name "LCSC PART #") "C25334") (field (name "Comment") "1206W4F100LT5E"))
      (libsource (lib "JLC_PCB") (part "1206W4F100LT5E"))
    )
    (comp (ref "TWLV_R_F")
      (value "0R")
      (footprint "R_0402")
      (description "R - RESISTOR - SMD - 0R - 1% - 0402")
      (fields (field (name "LCSC PART #") "C17168") (field (name "Comment") "0402WGF0000TCE"))
      (libsource (lib "JLC_PCB") (part "0402WGF0000TCE"))
    )
    (comp (ref "U")
      (value "LT8490EUKJ#PBF")
      (footprint "SnapEDApcb:QFN50P700X1100X80-65N")
      (description "Battery Charger Lead-Acid/Li-Ion 1.3V to 80V 64-Pin QFN EP Tube")
      (fields (field (name "MF") "Analog Devices"))
      (libsource (lib "JLC_PCB") (part "LT8490EUKJ#PBF"))
    )
    (comp (ref "U_TWLV_A")
      (value "LM2576HVS-ADJ/TR")
      (footprint "SILICON:TO-263-5")
      (description "U - IC - BUCK CONVERTER, ADJUSTABLE, 60V, 3A")
      (fields (field (name "LCSC PART #") "C234208") (field (name "MF") "Texas Instruments"))
      (libsource (lib "JLC_PCB") (part "LM2576HVS-ADJ/TR"))
    )
  )
  (nets
    (net (code "1") (name "/+3V3") (class "Default")
      (node (ref "C") (pin "2") (pinfunction "2_2") (pintype "passive"))
      (node (ref "MT_C_ZA") (pin "2") (pinfunction "2_2") (pintype "passive"))
      (node (ref "MT_C_ZB") (pin "2") (pinfunction "2_2") (pintype "passive"))
      (node (ref "MT_C_ZC") (pin "2") (pinfunction "2_2") (pintype "passive"))
      (node (ref "MT_C_ZD") (pin "2") (pinfunction "2_2") (pintype "passive"))
      (node (ref "MT_C_ZE") (pin "2") (pinfunction "2_2") (pintype "passive"))
      (node (ref "MT_C_ZF") (pin "2") (pinfunction "2_2") (pintype "passive"))
      (node (ref "MT_L_TA") (pin "2") (pinfunction "2_2") (pintype "passive"))
      (node (ref "MT_POL_R") (pin "2") (pinfunction "2_2") (pintype "passive"))
      (node (ref "MT_POL_R_N") (pin "2") (pinfunction "2_2") (pintype "passive"))
      (node (ref "MT_REG_THREE") (pin "2") (pinfunction "VOUT_2") (pintype "passive"))
      (node (ref "MT_R_FT") (pin "2") (pinfunction "2_2") (pintype "passive"))
      (node (ref "MT_R_THREE") (pin "2") (pinfunction "2_2") (pintype "passive"))
      (node (ref "MT_U_T") (pin "24") (pinfunction "VCC_24") (pintype "power_in"))
    )
    (net (code "2") (name "/+3V3_IN") (class "Default")
      (node (ref "MT_R_THREE") (pin "1") (pinfunction "1_1") (pintype "passive"))
    )
    (net (code "3") (name "/+3V3_LED") (class "Default")
      (node (ref "MT_R_FT") (pin "1") (pinfunction "1_1") (pintype "passive"))
      (node (ref "R100") (pin "1") (pinfunction "1_1") (pintype "passive"))
      (node (ref "R101") (pin "1") (pinfunction "1_1") (pintype "passive"))
      (node (ref "R102") (pin "1") (pinfunction "1_1") (pintype "passive"))
      (node (ref "R103") (pin "1") (pinfunction "1_1") (pintype "passive"))
    )
    (net (code "4") (name "/+12V") (class "Default")
      (node (ref "MT_C_AMP") (pin "2") (pinfunction "2_2") (pintype "passive"))
      (node (ref "MT_D_KA_A") (pin "1") (pinfunction "K_1") (pintype "passive"))
      (node (ref "MT_D_KB_A") (pin "1") (pinfunction "K_1") (pintype "passive"))
      (node (ref "MT_KA") (pin "1") (pinfunction "COIL1_1") (pintype "passive"))
      (node (ref "MT_KB") (pin "1") (pinfunction "COIL1_1") (pintype "passive"))
      (node (ref "MT_REG_THREE") (pin "3") (pinfunction "VIN_3") (pintype "input"))
      (node (ref "MT_R_TWELVE") (pin "2") (pinfunction "2_2") (pintype "passive"))
      (node (ref "MT_U_AMP") (pin "4") (pinfunction "VCC_4") (pintype "power_in"))
      (node (ref "TWLV_R_F") (pin "2") (pinfunction "2_2") (pintype "passive"))
    )
    (net (code "5") (name "/+12V_I") (class "Default")
      (node (ref "TWLV_C_AA") (pin "1") (pinfunction "1_1") (pintype "passive"))
      (node (ref "TWLV_C_AB") (pin "1") (pinfunction "1_1") (pintype "passive"))
      (node (ref "TWLV_C_AC") (pin "1") (pinfunction "1_1") (pintype "passive"))
      (node (ref "TWLV_C_AD") (pin "1") (pinfunction "1_1") (pintype "passive"))
      (node (ref "TWLV_C_AE") (pin "1") (pinfunction "1_1") (pintype "passive"))
      (node (ref "TWLV_C_AF") (pin "1") (pinfunction "1_1") (pintype "passive"))
      (node (ref "TWLV_C_AG") (pin "1") (pinfunction "1_1") (pintype "passive"))
      (node (ref "TWLV_C_AH") (pin "1") (pinfunction "1_1") (pintype "passive"))
      (node (ref "TWLV_C_AI") (pin "1") (pinfunction "1_1") (pintype "passive"))
      (node (ref "TWLV_C_AJ") (pin "1") (pinfunction "1_1") (pintype "passive"))
      (node (ref "TWLV_C_AK") (pin "1") (pinfunction "1_1") (pintype "passive"))
      (node (ref "TWLV_C_AL") (pin "1") (pinfunction "1_1") (pintype "passive"))
      (node (ref "TWLV_C_AM") (pin "1") (pinfunction "1_1") (pintype "passive"))
      (node (ref "TWLV_C_AN") (pin "1") (pinfunction "1_1") (pintype "passive"))
      (node (ref "TWLV_C_AO") (pin "1") (pinfunction "1_1") (pintype "passive"))
      (node (ref "TWLV_C_AP") (pin "1") (pinfunction "1_1") (pintype "passive"))
      (node (ref "TWLV_C_AQ") (pin "1") (pinfunction "1_1") (pintype "passive"))
      (node (ref "TWLV_C_AR") (pin "1") (pinfunction "1_1") (pintype "passive"))
      (node (ref "TWLV_C_AS") (pin "1") (pinfunction "1_1") (pintype "passive"))
      (node (ref "TWLV_C_AT") (pin "1") (pinfunction "1_1") (pintype "passive"))
      (node (ref "TWLV_C_AU") (pin "1") (pinfunction "1_1") (pintype "passive"))
      (node (ref "TWLV_C_AV") (pin "1") (pinfunction "1_1") (pintype "passive"))
      (node (ref "TWLV_C_AW") (pin "1") (pinfunction "1_1") (pintype "passive"))
      (node (ref "TWLV_C_AX") (pin "1") (pinfunction "1_1") (pintype "passive"))
      (node (ref "TWLV_C_AY") (pin "1") (pinfunction "1_1") (pintype "passive"))
      (node (ref "TWLV_C_AZ") (pin "1") (pinfunction "1_1") (pintype "passive"))
      (node (ref "TWLV_C_BA") (pin "1") (pinfunction "1_1") (pintype "passive"))
      (node (ref "TWLV_C_BB") (pin "1") (pinfunction "1_1") (pintype "passive"))
      (node (ref "TWLV_C_BC") (pin "1") (pinfunction "1_1") (pintype "passive"))
      (node (ref "TWLV_C_BD") (pin "1") (pinfunction "1_1") (pintype "passive"))
      (node (ref "TWLV_C_BE") (pin "1") (pinfunction "1_1") (pintype "passive"))
      (node (ref "TWLV_C_BF") (pin "1") (pinfunction "1_1") (pintype "passive"))
      (node (ref "TWLV_C_BG") (pin "1") (pinfunction "1_1") (pintype "passive"))
      (node (ref "TWLV_C_BH") (pin "1") (pinfunction "1_1") (pintype "passive"))
      (node (ref "TWLV_C_BI") (pin "1") (pinfunction "1_1") (pintype "passive"))
      (node (ref "TWLV_C_BJ") (pin "1") (pinfunction "1_1") (pintype "passive"))
      (node (ref "TWLV_R_C") (pin "1") (pinfunction "1_1") (pintype "passive"))
      (node (ref "TWLV_R_E") (pin "2") (pinfunction "2_2") (pintype "passive"))
      (node (ref "TWLV_R_F") (pin "1") (pinfunction "1_1") (pintype "passive"))
    )
    (net (code "6") (name "/+12V_IN") (class "Default")
      (node (ref "MT_R_TWELVE") (pin "1") (pinfunction "1_1") (pintype "passive"))
    )
    (net (code "7") (name "/1A_GATE") (class "Default")
      (node (ref "D_1A") (pin "2") (pinfunction "A_2") (pintype "passive"))
      (node (ref "D_1A_G") (pin "1") (pinfunction "K_1") (pintype "passive"))
      (node (ref "Q_LEDA") (pin "1") (pinfunction "G_1") (pintype "passive"))
      (node (ref "R_1A_b") (pin "2") (pinfunction "2_2") (pintype "passive"))
      (node (ref "R_1A_c") (pin "2") (pinfunction "2_2") (pintype "passive"))
    )
    (net (code "8") (name "/1B_GATE") (class "Default")
      (node (ref "D_1B") (pin "2") (pinfunction "A_2") (pintype "passive"))
      (node (ref "D_1B_G") (pin "1") (pinfunction "K_1") (pintype "passive"))
      (node (ref "R_1B_b") (pin "2") (pinfunction "2_2") (pintype "passive"))
      (node (ref "R_1B_c") (pin "2") (pinfunction "2_2") (pintype "passive"))
    )
    (net (code "9") (name "/BG1") (class "Default")
      (node (ref "D5") (pin "1") (pinfunction "K_1") (pintype "passive"))
      (node (ref "Rbg1a") (pin "1") (pinfunction "1_1") (pintype "passive"))
      (node (ref "U") (pin "23") (pinfunction "BG1_23") (pintype "input"))
    )
    (net (code "10") (name "/BG2") (class "Default")
      (node (ref "D6") (pin "1") (pinfunction "K_1") (pintype "passive"))
      (node (ref "Rbg2a") (pin "2") (pinfunction "2_2") (pintype "passive"))
      (node (ref "U") (pin "25") (pinfunction "BG2_25") (pintype "input"))
    )
    (net (code "11") (name "/BOOST1") (class "Default")
      (node (ref "Cboot1") (pin "2") (pinfunction "2_2") (pintype "passive"))
      (node (ref "MT_D_BOOST_A") (pin "1") (pinfunction "K_1") (pintype "passive"))
      (node (ref "U") (pin "33") (pinfunction "BOOST1_33") (pintype "passive"))
    )
    (net (code "12") (name "/BOOST2") (class "Default")
      (node (ref "Cboot2") (pin "2") (pinfunction "2_2") (pintype "passive"))
      (node (ref "MT_D_BOOST_B") (pin "1") (pinfunction "K_1") (pintype "passive"))
      (node (ref "U") (pin "27") (pinfunction "BOOST2_27") (pintype "passive"))
    )
    (net (code "13") (name "/BUTTON_OC") (class "Default")
      (node (ref "TWLV_Q_A") (pin "3") (pinfunction "D_3") (pintype "passive"))
      (node (ref "TWLV_R_A") (pin "2") (pinfunction "2_2") (pintype "passive"))
      (node (ref "U_TWLV_A") (pin "5") (pinfunction "ON/OFF_5") (pintype "input"))
    )
    (net (code "14") (name "/D8") (class "Default")
      (node (ref "D_CLAMP_8") (pin "2") (pinfunction "A_2") (pintype "passive"))
      (node (ref "D_CLAMP_9") (pin "1") (pinfunction "K_1") (pintype "passive"))
    )
    (net (code "15") (name "/D10") (class "Default")
      (node (ref "D_CLAMP_10") (pin "2") (pinfunction "A_2") (pintype "passive"))
      (node (ref "D_CLAMP_11") (pin "1") (pinfunction "K_1") (pintype "passive"))
    )
    (net (code "16") (name "/DATA_BUS_A0") (class "Default")
      (node (ref "MT_U_T") (pin "10") (pinfunction "S0_10") (pintype "passive"))
    )
    (net (code "17") (name "/DATA_BUS_A1") (class "Default")
      (node (ref "MT_U_T") (pin "11") (pinfunction "S1_11") (pintype "passive"))
    )
    (net (code "18") (name "/DATA_BUS_A2") (class "Default")
      (node (ref "MT_U_T") (pin "14") (pinfunction "S2_14") (pintype "passive"))
    )
    (net (code "19") (name "/DATA_BUS_A3") (class "Default")
      (node (ref "MT_U_T") (pin "13") (pinfunction "S3_13") (pintype "passive"))
    )
    (net (code "20") (name "/ECON") (class "Default")
      (node (ref "MT_ECON") (pin "1") (pinfunction "1_1") (pintype "passive"))
      (node (ref "MT_Q_ECON_A") (pin "1") (pinfunction "G_1") (pintype "passive"))
      (node (ref "U") (pin "48") (pinfunction "ECON_48") (pintype "output"))
    )
    (net (code "21") (name "/FBOUT") (class "Default")
      (node (ref "MR_R_FBOW_B") (pin "2") (pinfunction "2_2") (pintype "passive"))
      (node (ref "MT_R_FBOUT_B") (pin "2") (pinfunction "2_2") (pintype "passive"))
      (node (ref "MT_R_FBOUT_C") (pin "2") (pinfunction "2_2") (pintype "passive"))
      (node (ref "MT_U_AMP") (pin "5") (pinfunction "+IN2_5") (pintype "input"))
      (node (ref "U") (pin "16") (pinfunction "FBOUT_16") (pintype "output"))
      (node (ref "U") (pin "57") (pinfunction "FBOR_57") (pintype "input"))
    )
    (net (code "22") (name "/FBOUT_IN") (class "Default")
      (node (ref "MT_Q_SWEN_B") (pin "3") (pinfunction "D_3") (pintype "passive"))
      (node (ref "MT_R_FBOUT_AA") (pin "2") (pinfunction "2_2") (pintype "passive"))
      (node (ref "MT_R_FBOUT_AB") (pin "2") (pinfunction "2_2") (pintype "passive"))
      (node (ref "MT_R_SWEN_B") (pin "1") (pinfunction "1_1") (pintype "passive"))
    )
    (net (code "23") (name "/GATE_VCC") (class "Default")
      (node (ref "MT_C_GVCC") (pin "2") (pinfunction "2_2") (pintype "passive"))
      (node (ref "MT_R_GVCC") (pin "1") (pinfunction "1_1") (pintype "passive"))
      (node (ref "MT_R_MODE_A") (pin "2") (pinfunction "2_2") (pintype "passive"))
      (node (ref "U") (pin "24") (pinfunction "GATEVCC_24") (pintype "power_in"))
      (node (ref "U") (pin "7") (pinfunction "INTVCC_7") (pintype "output"))
    )
    (net (code "24") (name "/GATE_VCC_2") (class "Default")
      (node (ref "MT_D_BOOST_A") (pin "2") (pinfunction "A_2") (pintype "passive"))
      (node (ref "MT_D_BOOST_B") (pin "2") (pinfunction "A_2") (pintype "passive"))
      (node (ref "MT_R_GVCC") (pin "2") (pinfunction "2_2") (pintype "passive"))
    )
    (net (code "25") (name "/LED_VSS") (class "Default")
      (node (ref "Q_LEDA") (pin "2") (pinfunction "S_2") (pintype "passive"))
      (node (ref "Q_LEDB") (pin "2") (pinfunction "S_2") (pintype "passive"))
      (node (ref "Q_LEDVSS") (pin "3") (pinfunction "D_3") (pintype "passive"))
    )
    (net (code "26") (name "/MODE") (class "Default")
      (node (ref "MT_R_MODE_A") (pin "1") (pinfunction "1_1") (pintype "passive"))
      (node (ref "MT_R_MODE_B") (pin "2") (pinfunction "2_2") (pintype "passive"))
      (node (ref "U") (pin "9") (pinfunction "MODE_9") (pintype "input"))
    )
    (net (code "27") (name "/MT_A_A") (class "Default")
      (node (ref "MT_U_AMP") (pin "1") (pinfunction "OUT1_1") (pintype "output"))
      (node (ref "MT_U_AMP") (pin "2") (pinfunction "-IN1_2") (pintype "input"))
      (node (ref "MT_U_T") (pin "4") (pinfunction "Y5_4") (pintype "passive"))
    )
    (net (code "28") (name "/MT_A_B") (class "Default")
      (node (ref "MT_U_AMP") (pin "6") (pinfunction "-IN2_6") (pintype "input"))
      (node (ref "MT_U_AMP") (pin "7") (pinfunction "+OUT2_7") (pintype "output"))
      (node (ref "MT_U_T") (pin "5") (pinfunction "Y4_5") (pintype "passive"))
    )
    (net (code "29") (name "/MT_A_C") (class "Default")
      (node (ref "MT_U_AMP") (pin "8") (pinfunction "+OUT3_8") (pintype "output"))
      (node (ref "MT_U_AMP") (pin "9") (pinfunction "-IN3_9") (pintype "input"))
      (node (ref "MT_U_T") (pin "3") (pinfunction "Y6_3") (pintype "passive"))
    )
    (net (code "30") (name "/MT_A_D") (class "Default")
      (node (ref "MT_U_AMP") (pin "13") (pinfunction "-IN4_13") (pintype "input"))
      (node (ref "MT_U_AMP") (pin "14") (pinfunction "OUT4_14") (pintype "output"))
      (node (ref "MT_U_T") (pin "2") (pinfunction "Y7_2") (pintype "passive"))
    )
    (net (code "31") (name "/MT_CLKDET") (class "Default")
      (node (ref "MT_R_CLKDET") (pin "1") (pinfunction "1_1") (pintype "passive"))
      (node (ref "U") (pin "56") (pinfunction "CLKDET_56") (pintype "input"))
    )
    (net (code "32") (name "/MT_CLKOUT") (class "Default")
      (node (ref "C_MT_CLKOUT") (pin "1") (pinfunction "1_1") (pintype "passive"))
      (node (ref "MT_R_CLKDET") (pin "2") (pinfunction "2_2") (pintype "passive"))
      (node (ref "U") (pin "20") (pinfunction "CLKOUT_20") (pintype "output"))
    )
    (net (code "33") (name "/MT_CSNIN") (class "Default")
      (node (ref "MT_C_VIN_F") (pin "1") (pinfunction "1_1") (pintype "passive"))
      (node (ref "MT_R_VIN_B") (pin "1") (pinfunction "1_1") (pintype "passive"))
      (node (ref "U") (pin "44") (pinfunction "CSNIN_44") (pintype "input"))
    )
    (net (code "34") (name "/MT_CSNOUT") (class "Default")
      (node (ref "MT_C_VOUT_F") (pin "1") (pinfunction "1_1") (pintype "passive"))
      (node (ref "MT_R_VOUT_B") (pin "1") (pinfunction "1_1") (pintype "passive"))
      (node (ref "U") (pin "41") (pinfunction "CSNOUT_41") (pintype "input"))
    )
    (net (code "35") (name "/MT_CSPIN") (class "Default")
      (node (ref "MT_C_VIN_F") (pin "2") (pinfunction "2_2") (pintype "passive"))
      (node (ref "MT_R_VIN_A") (pin "1") (pinfunction "1_1") (pintype "passive"))
      (node (ref "U") (pin "45") (pinfunction "CSPIN_45") (pintype "input"))
    )
    (net (code "36") (name "/MT_CSPOUT") (class "Default")
      (node (ref "MT_C_VOUT_F") (pin "2") (pinfunction "2_2") (pintype "passive"))
      (node (ref "MT_R_VOUT_A") (pin "1") (pinfunction "1_1") (pintype "passive"))
      (node (ref "U") (pin "42") (pinfunction "CSPOUT_42") (pintype "input"))
    )
    (net (code "37") (name "/MT_CS_N") (class "Default")
      (node (ref "MT_C_CSS") (pin "1") (pinfunction "1_1") (pintype "passive"))
      (node (ref "MT_R_CSS_N") (pin "2") (pinfunction "2_2") (pintype "passive"))
      (node (ref "U") (pin "12") (pinfunction "CSN_12") (pintype "input"))
    )
    (net (code "38") (name "/MT_CS_P") (class "Default")
      (node (ref "MT_C_CSS") (pin "2") (pinfunction "2_2") (pintype "passive"))
      (node (ref "MT_R_CSS_P") (pin "2") (pinfunction "2_2") (pintype "passive"))
      (node (ref "U") (pin "13") (pinfunction "CSP_13") (pintype "input"))
    )
    (net (code "39") (name "/MT_DC_IN") (class "Default")
      (node (ref "MT_Q_VINR") (pin "1") (pinfunction "G_1") (pintype "passive"))
      (node (ref "MT_R_VINR") (pin "1") (pinfunction "1_1") (pintype "passive"))
    )
    (net (code "40") (name "/MT_EXTVCC") (class "Default")
      (node (ref "MT_C_EXTVCC") (pin "1") (pinfunction "1_1") (pintype "passive"))
      (node (ref "MT_R_ECON_E") (pin "1") (pinfunction "1_1") (pintype "passive"))
      (node (ref "MT_R_EXTVCC") (pin "2") (pinfunction "2_2") (pintype "passive"))
      (node (ref "U") (pin "40") (pinfunction "EXTVCC_40") (pintype "bidirectional"))
    )
    (net (code "41") (name "/MT_FAULT") (class "Default")
      (node (ref "MT_D_FAULT") (pin "2") (pinfunction "A_2") (pintype "passive"))
      (node (ref "MT_R_FAULT_A") (pin "2") (pinfunction "2_2") (pintype "passive"))
      (node (ref "U") (pin "2") (pinfunction "FAULT_2") (pintype "output"))
    )
    (net (code "42") (name "/MT_FBIN") (class "Default")
      (node (ref "MR_R_FBIW_B") (pin "2") (pinfunction "2_2") (pintype "passive"))
      (node (ref "MT_R_FBIN_B") (pin "2") (pinfunction "2_2") (pintype "passive"))
      (node (ref "MT_R_FBIN_C") (pin "2") (pinfunction "2_2") (pintype "passive"))
      (node (ref "MT_R_FBIR") (pin "2") (pinfunction "2_2") (pintype "passive"))
      (node (ref "U") (pin "15") (pinfunction "FBIN_15") (pintype "input"))
    )
    (net (code "43") (name "/MT_FBIR") (class "Default")
      (node (ref "MT_R_FBIR") (pin "1") (pinfunction "1_1") (pintype "passive"))
      (node (ref "U") (pin "1") (pinfunction "FBIR_1") (pintype "input"))
    )
    (net (code "44") (name "/MT_FBIW") (class "Default")
      (node (ref "MT_C_FBIW") (pin "1") (pinfunction "1_1") (pintype "passive"))
      (node (ref "MT_R_FBIW_A") (pin "1") (pinfunction "1_1") (pintype "passive"))
      (node (ref "U") (pin "6") (pinfunction "FBIW_6") (pintype "output"))
    )
    (net (code "45") (name "/MT_FBIW_A") (class "Default")
      (node (ref "MR_R_FBIW_B") (pin "1") (pinfunction "1_1") (pintype "passive"))
      (node (ref "MT_R_FBIW_A") (pin "2") (pinfunction "2_2") (pintype "passive"))
    )
    (net (code "46") (name "/MT_FBOW") (class "Default")
      (node (ref "MT_R_DACO_A") (pin "1") (pinfunction "1_1") (pintype "passive"))
      (node (ref "U") (pin "5") (pinfunction "FBOW_5") (pintype "output"))
    )
    (net (code "47") (name "/MT_FBOW_A") (class "Default")
      (node (ref "MR_R_FBOW_B") (pin "1") (pinfunction "1_1") (pintype "passive"))
      (node (ref "MT_C_DACO") (pin "1") (pinfunction "1_1") (pintype "passive"))
      (node (ref "MT_R_DACO_A") (pin "2") (pinfunction "2_2") (pintype "passive"))
    )
    (net (code "48") (name "/MT_IMON_IN") (class "Default")
      (node (ref "MT_C_IMON_IN") (pin "2") (pinfunction "2_2") (pintype "passive"))
      (node (ref "MT_R_IMON_IN") (pin "2") (pinfunction "2_2") (pintype "passive"))
      (node (ref "MT_U_AMP") (pin "12") (pinfunction "+IN4_12") (pintype "input"))
      (node (ref "U") (pin "10") (pinfunction "IMON_IN_10") (pintype "input"))
      (node (ref "U") (pin "53") (pinfunction "IIR_53") (pintype "input"))
    )
    (net (code "49") (name "/MT_IMON_OUT") (class "Default")
      (node (ref "MT_C_IMON_OUT") (pin "2") (pinfunction "2_2") (pintype "passive"))
      (node (ref "MT_R_IMON_OUT") (pin "2") (pinfunction "2_2") (pintype "passive"))
      (node (ref "MT_R_IOR") (pin "2") (pinfunction "2_2") (pintype "passive"))
      (node (ref "MT_R_IOW") (pin "2") (pinfunction "2_2") (pintype "passive"))
      (node (ref "MT_U_AMP") (pin "3") (pinfunction "+IN1_3") (pintype "input"))
      (node (ref "U") (pin "17") (pinfunction "IMON_OUT_17") (pintype "output"))
    )
    (net (code "50") (name "/MT_IOR") (class "Default")
      (node (ref "MT_R_IOR") (pin "1") (pinfunction "1_1") (pintype "passive"))
      (node (ref "U") (pin "64") (pinfunction "IOR_64") (pintype "bidirectional"))
    )
    (net (code "51") (name "/MT_IOW") (class "Default")
      (node (ref "MT_R_IOW") (pin "1") (pinfunction "1_1") (pintype "passive"))
      (node (ref "U") (pin "50") (pinfunction "IOW_50") (pintype "output"))
    )
    (net (code "52") (name "/MT_KA") (class "Default")
      (node (ref "MT_D_KA_B") (pin "1") (pinfunction "K_1") (pintype "passive"))
      (node (ref "MT_KA") (pin "8") (pinfunction "COIL2_8") (pintype "passive"))
      (node (ref "MT_Q_KA") (pin "3") (pinfunction "D_3") (pintype "passive"))
    )
    (net (code "53") (name "/MT_KB") (class "Default")
      (node (ref "MT_D_KB_B") (pin "1") (pinfunction "K_1") (pintype "passive"))
      (node (ref "MT_KB") (pin "8") (pinfunction "COIL2_8") (pintype "passive"))
      (node (ref "MT_Q_KB") (pin "3") (pinfunction "D_3") (pintype "passive"))
    )
    (net (code "54") (name "/MT_K_EN") (class "Default")
      (node (ref "MT_Q_KB") (pin "1") (pinfunction "G_1") (pintype "passive"))
      (node (ref "MT_R_KB") (pin "1") (pinfunction "1_1") (pintype "passive"))
    )
    (net (code "55") (name "/MT_K_POL") (class "Default")
      (node (ref "MT_Q_KA") (pin "1") (pinfunction "G_1") (pintype "passive"))
      (node (ref "MT_R_KA") (pin "1") (pinfunction "1_1") (pintype "passive"))
      (node (ref "MT_R_POL_N") (pin "1") (pinfunction "1_1") (pintype "passive"))
      (node (ref "MT_R_POL_P") (pin "1") (pinfunction "1_1") (pintype "passive"))
    )
    (net (code "56") (name "/MT_LED_A") (class "Default")
      (node (ref "J1") (pin "11") (pinfunction "11_11") (pintype "passive"))
      (node (ref "MT_U_T") (pin "19") (pinfunction "Y12_19") (pintype "passive"))
      (node (ref "R_LED_B") (pin "2") (pinfunction "2_2") (pintype "passive"))
    )
    (net (code "57") (name "/MT_LED_B") (class "Default")
      (node (ref "J1") (pin "9") (pinfunction "9_9") (pintype "passive"))
      (node (ref "MT_U_T") (pin "20") (pinfunction "Y11_20") (pintype "passive"))
      (node (ref "R_LED_A") (pin "2") (pinfunction "2_2") (pintype "passive"))
    )
    (net (code "58") (name "/MT_LED_C") (class "Default")
      (node (ref "J2") (pin "11") (pinfunction "11_11") (pintype "passive"))
      (node (ref "MT_U_T") (pin "22") (pinfunction "Y9_22") (pintype "passive"))
      (node (ref "R_LED_C") (pin "2") (pinfunction "2_2") (pintype "passive"))
    )
    (net (code "59") (name "/MT_LED_D") (class "Default")
      (node (ref "J2") (pin "9") (pinfunction "9_9") (pintype "passive"))
      (node (ref "MT_U_T") (pin "21") (pinfunction "Y10_21") (pintype "passive"))
      (node (ref "R_LED_D") (pin "2") (pinfunction "2_2") (pintype "passive"))
    )
    (net (code "60") (name "/MT_MUX") (class "Default")
      (node (ref "MT_U_T") (pin "1") (pinfunction "Z_1") (pintype "passive"))
    )
    (net (code "61") (name "/MT_RT") (class "Default")
      (node (ref "MT_R_T") (pin "1") (pinfunction "1_1") (pintype "passive"))
      (node (ref "U") (pin "22") (pinfunction "RT_22") (pintype "passive"))
    )
    (net (code "62") (name "/MT_SHDN") (class "Default")
      (node (ref "MT_Q_SHDN") (pin "3") (pinfunction "D_3") (pintype "passive"))
      (node (ref "MT_R_SHDN_A") (pin "1") (pinfunction "1_1") (pintype "passive"))
      (node (ref "MT_R_SHDN_B") (pin "2") (pinfunction "2_2") (pintype "passive"))
      (node (ref "MT_R_WAKE_B") (pin "1") (pinfunction "1_1") (pintype "passive"))
      (node (ref "U") (pin "11") (pinfunction "~{SHDN}_11") (pintype "input"))
    )
    (net (code "63") (name "/MT_SHDN_EN") (class "Default")
      (node (ref "MT_Q_SHDN") (pin "1") (pinfunction "G_1") (pintype "passive"))
      (node (ref "MT_R_SHDN_C") (pin "1") (pinfunction "1_1") (pintype "passive"))
    )
    (net (code "64") (name "/MT_SS") (class "Default")
      (node (ref "MT_C_SS") (pin "1") (pinfunction "1_1") (pintype "passive"))
      (node (ref "U") (pin "19") (pinfunction "SS_19") (pintype "passive"))
    )
    (net (code "65") (name "/MT_STATUS") (class "Default")
      (node (ref "MT_D_STATUS") (pin "2") (pinfunction "A_2") (pintype "passive"))
      (node (ref "MT_R_STATUS_A") (pin "2") (pinfunction "2_2") (pintype "passive"))
      (node (ref "U") (pin "51") (pinfunction "STATUS_51") (pintype "output"))
    )
    (net (code "66") (name "/MT_TEMP") (class "Default")
      (node (ref "MT_C_TEMP") (pin "1") (pinfunction "1_1") (pintype "passive"))
      (node (ref "MT_R_TEMP_A") (pin "2") (pinfunction "2_2") (pintype "passive"))
      (node (ref "MT_R_TEMP_B") (pin "1") (pinfunction "1_1") (pintype "passive"))
      (node (ref "U") (pin "3") (pinfunction "TEMPSENSE_3") (pintype "input"))
    )
    (net (code "67") (name "/MT_TS_A") (class "Default")
      (node (ref "MT_RT_TA") (pin "2") (pinfunction "2_2") (pintype "passive"))
      (node (ref "MT_R_TA") (pin "1") (pinfunction "1_1") (pintype "passive"))
      (node (ref "MT_U_T") (pin "9") (pinfunction "Y0_9") (pintype "passive"))
    )
    (net (code "68") (name "/MT_TS_B") (class "Default")
      (node (ref "MT_RT_TB") (pin "2") (pinfunction "2_2") (pintype "passive"))
      (node (ref "MT_R_TB") (pin "1") (pinfunction "1_1") (pintype "passive"))
      (node (ref "MT_U_T") (pin "8") (pinfunction "Y1_8") (pintype "passive"))
    )
    (net (code "69") (name "/MT_TS_D") (class "Default")
      (node (ref "MT_RT_TD") (pin "2") (pinfunction "2_2") (pintype "passive"))
      (node (ref "MT_R_TD") (pin "1") (pinfunction "1_1") (pintype "passive"))
      (node (ref "MT_U_T") (pin "7") (pinfunction "Y2_7") (pintype "passive"))
    )
    (net (code "70") (name "/MT_TS_E") (class "Default")
      (node (ref "MT_RT_TE") (pin "2") (pinfunction "2_2") (pintype "passive"))
      (node (ref "MT_R_TE") (pin "1") (pinfunction "1_1") (pintype "passive"))
      (node (ref "MT_U_T") (pin "6") (pinfunction "Y3_6") (pintype "passive"))
    )
    (net (code "71") (name "/MT_TS_G") (class "Default")
      (node (ref "MT_RT_TG") (pin "2") (pinfunction "2_2") (pintype "passive"))
      (node (ref "MT_R_TG") (pin "1") (pinfunction "1_1") (pintype "passive"))
      (node (ref "MT_U_T") (pin "18") (pinfunction "Y13_18") (pintype "passive"))
    )
    (net (code "72") (name "/MT_TS_J") (class "Default")
      (node (ref "MT_RT_TJ") (pin "2") (pinfunction "2_2") (pintype "passive"))
      (node (ref "MT_R_TJ") (pin "1") (pinfunction "1_1") (pintype "passive"))
      (node (ref "MT_U_T") (pin "17") (pinfunction "Y14_17") (pintype "passive"))
    )
    (net (code "73") (name "/MT_TS_K") (class "Default")
      (node (ref "MT_RT_TK") (pin "2") (pinfunction "2_2") (pintype "passive"))
      (node (ref "MT_R_TK") (pin "1") (pinfunction "1_1") (pintype "passive"))
      (node (ref "MT_U_T") (pin "16") (pinfunction "Y15_16") (pintype "passive"))
    )
    (net (code "74") (name "/MT_VC") (class "Default")
      (node (ref "MT_C_VC_A") (pin "1") (pinfunction "1_1") (pintype "passive"))
      (node (ref "MT_R_VC") (pin "1") (pinfunction "1_1") (pintype "passive"))
      (node (ref "U") (pin "18") (pinfunction "VC_18") (pintype "output"))
    )
    (net (code "75") (name "/MT_VDD") (class "Default")
      (node (ref "MT_C_VDD") (pin "2") (pinfunction "2_2") (pintype "passive"))
      (node (ref "MT_R_FAULT_A") (pin "1") (pinfunction "1_1") (pintype "passive"))
      (node (ref "MT_R_STATUS_A") (pin "1") (pinfunction "1_1") (pintype "passive"))
      (node (ref "MT_R_TEMP_B") (pin "2") (pinfunction "2_2") (pintype "passive"))
      (node (ref "U") (pin "14") (pinfunction "LDO33_14") (pintype "output"))
      (node (ref "U") (pin "4") (pinfunction "VDD_4") (pintype "power_in"))
      (node (ref "U") (pin "58") (pinfunction "AVDD_58") (pintype "power_in"))
    )
    (net (code "76") (name "/MT_VDDA_T") (class "Default")
      (node (ref "C_vdd_ts_a") (pin "1") (pinfunction "1_1") (pintype "passive"))
      (node (ref "MT_L_TA") (pin "1") (pinfunction "1_1") (pintype "passive"))
      (node (ref "MT_R_TA") (pin "2") (pinfunction "2_2") (pintype "passive"))
      (node (ref "MT_R_TB") (pin "2") (pinfunction "2_2") (pintype "passive"))
      (node (ref "MT_R_TD") (pin "2") (pinfunction "2_2") (pintype "passive"))
      (node (ref "MT_R_TE") (pin "2") (pinfunction "2_2") (pintype "passive"))
      (node (ref "MT_R_TG") (pin "2") (pinfunction "2_2") (pintype "passive"))
      (node (ref "MT_R_TJ") (pin "2") (pinfunction "2_2") (pintype "passive"))
      (node (ref "MT_R_TK") (pin "2") (pinfunction "2_2") (pintype "passive"))
    )
    (net (code "77") (name "/MT_VINR") (class "Default")
      (node (ref "MT_Q_VINR") (pin "3") (pinfunction "D_3") (pintype "passive"))
      (node (ref "MT_R_VINR_B") (pin "1") (pinfunction "1_1") (pintype "passive"))
      (node (ref "MT_R_VINR_C") (pin "2") (pinfunction "2_2") (pintype "passive"))
      (node (ref "MT_U_AMP") (pin "10") (pinfunction "+IN3_10") (pintype "input"))
      (node (ref "U") (pin "54") (pinfunction "VINR_54") (pintype "input"))
    )
    (net (code "78") (name "/MT_VSSA") (class "Default")
      (node (ref "MT_RT_TA") (pin "1") (pinfunction "1_1") (pintype "passive"))
      (node (ref "MT_RT_TB") (pin "1") (pinfunction "1_1") (pintype "passive"))
      (node (ref "MT_RT_TD") (pin "1") (pinfunction "1_1") (pintype "passive"))
      (node (ref "MT_RT_TE") (pin "1") (pinfunction "1_1") (pintype "passive"))
      (node (ref "MT_RT_TG") (pin "1") (pinfunction "1_1") (pintype "passive"))
      (node (ref "MT_RT_TJ") (pin "1") (pinfunction "1_1") (pintype "passive"))
      (node (ref "MT_RT_TK") (pin "1") (pinfunction "1_1") (pintype "passive"))
      (node (ref "MT_R_FV") (pin "1") (pinfunction "1_1") (pintype "passive"))
    )
    (net (code "79") (name "/PAN_DET") (class "Default")
      (node (ref "D_1A") (pin "1") (pinfunction "K_1") (pintype "passive"))
      (node (ref "D_1B") (pin "1") (pinfunction "K_1") (pintype "passive"))
      (node (ref "Q_LEDVSS") (pin "1") (pinfunction "G_1") (pintype "passive"))
    )
    (net (code "80") (name "/PGND") (class "Default")
      (node (ref "Dbg1") (pin "2") (pinfunction "A_2") (pintype "passive"))
      (node (ref "Dbg2") (pin "2") (pinfunction "A_2") (pintype "passive"))
      (node (ref "MT_Q2") (pin "3") (pinfunction "S_3") (pintype "passive"))
      (node (ref "MT_Q3") (pin "3") (pinfunction "S_3") (pintype "passive"))
      (node (ref "MT_R_CS") (pin "1") (pinfunction "1_1") (pintype "passive"))
      (node (ref "MT_R_CSS_P") (pin "1") (pinfunction "1_1") (pintype "passive"))
      (node (ref "Rbg1s") (pin "1") (pinfunction "1_1") (pintype "passive"))
      (node (ref "Rbg2s") (pin "2") (pinfunction "2_2") (pintype "passive"))
    )
    (net (code "81") (name "/POLARITY_N") (class "Default")
      (node (ref "MT_POL_R") (pin "1") (pinfunction "1_1") (pintype "passive"))
      (node (ref "MT_R_POL_N") (pin "2") (pinfunction "2_2") (pintype "passive"))
      (node (ref "MT_U_T") (pin "23") (pinfunction "Y8_23") (pintype "passive"))
      (node (ref "Q_LEDA") (pin "3") (pinfunction "D_3") (pintype "passive"))
      (node (ref "Q_LEDB") (pin "1") (pinfunction "G_1") (pintype "passive"))
      (node (ref "R_LED_B") (pin "1") (pinfunction "1_1") (pintype "passive"))
      (node (ref "R_LED_D") (pin "1") (pinfunction "1_1") (pintype "passive"))
    )
    (net (code "82") (name "/POLARITY_P") (class "Default")
      (node (ref "MT_POL_R_N") (pin "1") (pinfunction "1_1") (pintype "passive"))
      (node (ref "MT_R_POL_P") (pin "2") (pinfunction "2_2") (pintype "passive"))
      (node (ref "Q_LEDB") (pin "3") (pinfunction "D_3") (pintype "passive"))
      (node (ref "R_LED_A") (pin "1") (pinfunction "1_1") (pintype "passive"))
      (node (ref "R_LED_C") (pin "1") (pinfunction "1_1") (pintype "passive"))
    )
    (net (code "83") (name "/SOL_1A") (class "Default")
      (node (ref "MT_D_IN_A") (pin "2") (pinfunction "A_2") (pintype "passive"))
      (node (ref "MT_D_IN_B") (pin "1") (pinfunction "K_1") (pintype "passive"))
      (node (ref "MT_D_IN_E") (pin "2") (pinfunction "A_2") (pintype "passive"))
      (node (ref "MT_D_IN_F") (pin "1") (pinfunction "K_1") (pintype "passive"))
      (node (ref "MT_D_IN_I") (pin "2") (pinfunction "A_2") (pintype "passive"))
      (node (ref "MT_D_IN_J") (pin "1") (pinfunction "K_1") (pintype "passive"))
      (node (ref "MT_D_IN_M") (pin "2") (pinfunction "A_2") (pintype "passive"))
      (node (ref "MT_D_IN_N") (pin "1") (pinfunction "K_1") (pintype "passive"))
      (node (ref "MT_F_A") (pin "2") (pinfunction "2_2") (pintype "passive"))
      (node (ref "MT_F_B") (pin "2") (pinfunction "2_2") (pintype "passive"))
      (node (ref "MT_F_C") (pin "2") (pinfunction "2_2") (pintype "passive"))
      (node (ref "MT_KA") (pin "3") (pinfunction "COM1_3") (pintype "passive"))
      (node (ref "R_1A_a") (pin "1") (pinfunction "1_1") (pintype "passive"))
    )
    (net (code "84") (name "/SOL_1A_F") (class "Default")
      (node (ref "J1") (pin "1") (pinfunction "1_1") (pintype "passive"))
      (node (ref "J1") (pin "2") (pinfunction "2_2") (pintype "passive"))
      (node (ref "J1") (pin "3") (pinfunction "3_3") (pintype "passive"))
      (node (ref "J1") (pin "4") (pinfunction "4_4") (pintype "passive"))
      (node (ref "J1") (pin "5") (pinfunction "5_5") (pintype "passive"))
      (node (ref "J1") (pin "6") (pinfunction "6_6") (pintype "passive"))
      (node (ref "J1") (pin "7") (pinfunction "7_7") (pintype "passive"))
      (node (ref "J1") (pin "8") (pinfunction "8_8") (pintype "passive"))
      (node (ref "MT_F_A") (pin "1") (pinfunction "1_1") (pintype "passive"))
      (node (ref "MT_F_B") (pin "1") (pinfunction "1_1") (pintype "passive"))
      (node (ref "MT_F_C") (pin "1") (pinfunction "1_1") (pintype "passive"))
    )
    (net (code "85") (name "/SOL_1B") (class "Default")
      (node (ref "J2") (pin "1") (pinfunction "1_1") (pintype "passive"))
      (node (ref "J2") (pin "2") (pinfunction "2_2") (pintype "passive"))
      (node (ref "J2") (pin "3") (pinfunction "3_3") (pintype "passive"))
      (node (ref "J2") (pin "4") (pinfunction "4_4") (pintype "passive"))
      (node (ref "J2") (pin "5") (pinfunction "5_5") (pintype "passive"))
      (node (ref "J2") (pin "6") (pinfunction "6_6") (pintype "passive"))
      (node (ref "J2") (pin "7") (pinfunction "7_7") (pintype "passive"))
      (node (ref "J2") (pin "8") (pinfunction "8_8") (pintype "passive"))
      (node (ref "MT_D_IN_C") (pin "2") (pinfunction "A_2") (pintype "passive"))
      (node (ref "MT_D_IN_D") (pin "1") (pinfunction "K_1") (pintype "passive"))
      (node (ref "MT_D_IN_G") (pin "2") (pinfunction "A_2") (pintype "passive"))
      (node (ref "MT_D_IN_H") (pin "1") (pinfunction "K_1") (pintype "passive"))
      (node (ref "MT_D_IN_K") (pin "2") (pinfunction "A_2") (pintype "passive"))
      (node (ref "MT_D_IN_L") (pin "1") (pinfunction "K_1") (pintype "passive"))
      (node (ref "MT_D_IN_O") (pin "2") (pinfunction "A_2") (pintype "passive"))
      (node (ref "MT_D_IN_P") (pin "1") (pinfunction "K_1") (pintype "passive"))
      (node (ref "MT_KA") (pin "6") (pinfunction "COM2_6") (pintype "passive"))
      (node (ref "R_1B_a") (pin "1") (pinfunction "1_1") (pintype "passive"))
    )
    (net (code "86") (name "/SOL_V_N") (class "Default")
      (node (ref "MT_KA") (pin "4") (pinfunction "NO1_4") (pintype "passive"))
      (node (ref "MT_KA") (pin "7") (pinfunction "NC2_7") (pintype "passive"))
      (node (ref "MT_KB") (pin "3") (pinfunction "COM1_3") (pintype "passive"))
    )
    (net (code "87") (name "/SOL_V_P") (class "Default")
      (node (ref "MT_KA") (pin "2") (pinfunction "NC1_2") (pintype "passive"))
      (node (ref "MT_KA") (pin "5") (pinfunction "NO2_5") (pintype "passive"))
      (node (ref "MT_KB") (pin "6") (pinfunction "COM2_6") (pintype "passive"))
      (node (ref "MT_KB") (pin "7") (pinfunction "NC2_7") (pintype "passive"))
    )
    (net (code "88") (name "/SRVO_FBIN") (class "Default")
      (node (ref "U") (pin "35") (pinfunction "SRVO_FBIN_35") (pintype "output"))
    )
    (net (code "89") (name "/SRVO_FBOUT") (class "Default")
      (node (ref "U") (pin "38") (pinfunction "SRVO_FBOUT_38") (pintype "output"))
    )
    (net (code "90") (name "/SRVO_IIN") (class "Default")
      (node (ref "U") (pin "36") (pinfunction "SRVO_IIN_36") (pintype "output"))
    )
    (net (code "91") (name "/SRVO_IOUT") (class "Default")
      (node (ref "U") (pin "37") (pinfunction "SRVO_IOUT_37") (pintype "output"))
    )
    (net (code "92") (name "/SW1") (class "Default")
      (node (ref "C18") (pin "2") (pinfunction "2_2") (pintype "passive"))
      (node (ref "Cboot1") (pin "1") (pinfunction "1_1") (pintype "passive"))
      (node (ref "Dbg1") (pin "1") (pinfunction "K_1") (pintype "passive"))
      (node (ref "Dtg1") (pin "2") (pinfunction "A_2") (pintype "passive"))
      (node (ref "L1") (pin "1") (pinfunction "1_1") (pintype "passive"))
      (node (ref "L10") (pin "1") (pinfunction "1_1") (pintype "passive"))
      (node (ref "L11") (pin "1") (pinfunction "1_1") (pintype "passive"))
      (node (ref "L12") (pin "1") (pinfunction "1_1") (pintype "passive"))
      (node (ref "L2") (pin "1") (pinfunction "1_1") (pintype "passive"))
      (node (ref "L3") (pin "1") (pinfunction "1_1") (pintype "passive"))
      (node (ref "L4") (pin "1") (pinfunction "1_1") (pintype "passive"))
      (node (ref "L5") (pin "1") (pinfunction "1_1") (pintype "passive"))
      (node (ref "L6") (pin "1") (pinfunction "1_1") (pintype "passive"))
      (node (ref "L7") (pin "1") (pinfunction "1_1") (pintype "passive"))
      (node (ref "L8") (pin "1") (pinfunction "1_1") (pintype "passive"))
      (node (ref "L9") (pin "1") (pinfunction "1_1") (pintype "passive"))
      (node (ref "MT_Q1") (pin "3") (pinfunction "S_3") (pintype "passive"))
      (node (ref "MT_Q2") (pin "2") (pinfunction "D_2") (pintype "passive"))
      (node (ref "Rtg1s") (pin "1") (pinfunction "1_1") (pintype "passive"))
      (node (ref "U") (pin "31") (pinfunction "SW1_31") (pintype "passive"))
    )
    (net (code "93") (name "/SW2") (class "Default")
      (node (ref "C19") (pin "2") (pinfunction "2_2") (pintype "passive"))
      (node (ref "Cboot2") (pin "1") (pinfunction "1_1") (pintype "passive"))
      (node (ref "Dbg2") (pin "1") (pinfunction "K_1") (pintype "passive"))
      (node (ref "Dtg2") (pin "2") (pinfunction "A_2") (pintype "passive"))
      (node (ref "L1") (pin "2") (pinfunction "2_2") (pintype "passive"))
      (node (ref "L10") (pin "2") (pinfunction "2_2") (pintype "passive"))
      (node (ref "L11") (pin "2") (pinfunction "2_2") (pintype "passive"))
      (node (ref "L12") (pin "2") (pinfunction "2_2") (pintype "passive"))
      (node (ref "L2") (pin "2") (pinfunction "2_2") (pintype "passive"))
      (node (ref "L3") (pin "2") (pinfunction "2_2") (pintype "passive"))
      (node (ref "L4") (pin "2") (pinfunction "2_2") (pintype "passive"))
      (node (ref "L5") (pin "2") (pinfunction "2_2") (pintype "passive"))
      (node (ref "L6") (pin "2") (pinfunction "2_2") (pintype "passive"))
      (node (ref "L7") (pin "2") (pinfunction "2_2") (pintype "passive"))
      (node (ref "L8") (pin "2") (pinfunction "2_2") (pintype "passive"))
      (node (ref "L9") (pin "2") (pinfunction "2_2") (pintype "passive"))
      (node (ref "MT_Q3") (pin "2") (pinfunction "D_2") (pintype "passive"))
      (node (ref "MT_Q4") (pin "3") (pinfunction "S_3") (pintype "passive"))
      (node (ref "Rtg2s") (pin "2") (pinfunction "2_2") (pintype "passive"))
      (node (ref "U") (pin "29") (pinfunction "SW2_29") (pintype "passive"))
    )
    (net (code "94") (name "/SWEN") (class "Default")
      (node (ref "MT_Q_SWEN_A") (pin "1") (pinfunction "G_1") (pintype "passive"))
      (node (ref "MT_R_WAKE_A") (pin "1") (pinfunction "1_1") (pintype "passive"))
      (node (ref "MT_SWEN") (pin "1") (pinfunction "1_1") (pintype "passive"))
      (node (ref "U") (pin "49") (pinfunction "SWENO_49") (pintype "output"))
      (node (ref "U") (pin "8") (pinfunction "SWEN_8") (pintype "passive"))
    )
    (net (code "95") (name "/TG1") (class "Default")
      (node (ref "D3") (pin "1") (pinfunction "K_1") (pintype "passive"))
      (node (ref "Rtg1a") (pin "1") (pinfunction "1_1") (pintype "passive"))
      (node (ref "U") (pin "32") (pinfunction "TG1_32") (pintype "input"))
    )
    (net (code "96") (name "/TG2") (class "Default")
      (node (ref "D4") (pin "1") (pinfunction "K_1") (pintype "passive"))
      (node (ref "Rtg2a") (pin "2") (pinfunction "2_2") (pintype "passive"))
      (node (ref "U") (pin "28") (pinfunction "TG2_28") (pintype "input"))
    )
    (net (code "97") (name "/TWLV_FB") (class "Default")
      (node (ref "TWLV_R_C") (pin "2") (pinfunction "2_2") (pintype "passive"))
      (node (ref "TWLV_R_D") (pin "2") (pinfunction "2_2") (pintype "passive"))
      (node (ref "U_TWLV_A") (pin "4") (pinfunction "FB_4") (pintype "bidirectional"))
    )
    (net (code "98") (name "/WAKEUP_R") (class "Default")
      (node (ref "MT_R_WAKE_A") (pin "2") (pinfunction "2_2") (pintype "passive"))
      (node (ref "MT_R_WAKE_B") (pin "2") (pinfunction "2_2") (pintype "passive"))
      (node (ref "TWLV_Q_A") (pin "1") (pinfunction "G_1") (pintype "passive"))
      (node (ref "TWLV_R_B") (pin "1") (pinfunction "1_1") (pintype "passive"))
    )
    (net (code "99") (name "GND") (class "Default")
      (node (ref "C") (pin "1") (pinfunction "1_1") (pintype "passive"))
      (node (ref "C_MT_CLKOUT") (pin "2") (pinfunction "2_2") (pintype "passive"))
      (node (ref "C_vdd_ts_a") (pin "2") (pinfunction "2_2") (pintype "passive"))
      (node (ref "D14") (pin "1") (pinfunction "K_1") (pintype "passive"))
      (node (ref "D15") (pin "1") (pinfunction "K_1") (pintype "passive"))
      (node (ref "D_1A_G") (pin "2") (pinfunction "A_2") (pintype "passive"))
      (node (ref "D_1B_G") (pin "2") (pinfunction "A_2") (pintype "passive"))
      (node (ref "D_CLAMP_14") (pin "2") (pinfunction "A_2") (pintype "passive"))
      (node (ref "MT_C_AA") (pin "1") (pinfunction "1_1") (pintype "passive"))
      (node (ref "MT_C_AB") (pin "1") (pinfunction "1_1") (pintype "passive"))
      (node (ref "MT_C_AC") (pin "1") (pinfunction "1_1") (pintype "passive"))
      (node (ref "MT_C_AD") (pin "1") (pinfunction "1_1") (pintype "passive"))
      (node (ref "MT_C_AE") (pin "1") (pinfunction "1_1") (pintype "passive"))
      (node (ref "MT_C_AF") (pin "1") (pinfunction "1_1") (pintype "passive"))
      (node (ref "MT_C_AG") (pin "1") (pinfunction "1_1") (pintype "passive"))
      (node (ref "MT_C_AH") (pin "1") (pinfunction "1_1") (pintype "passive"))
      (node (ref "MT_C_AI") (pin "1") (pinfunction "1_1") (pintype "passive"))
      (node (ref "MT_C_AJ") (pin "1") (pinfunction "1_1") (pintype "passive"))
      (node (ref "MT_C_AK") (pin "1") (pinfunction "1_1") (pintype "passive"))
      (node (ref "MT_C_AL") (pin "1") (pinfunction "1_1") (pintype "passive"))
      (node (ref "MT_C_AM") (pin "1") (pinfunction "1_1") (pintype "passive"))
      (node (ref "MT_C_AMP") (pin "1") (pinfunction "1_1") (pintype "passive"))
      (node (ref "MT_C_AN") (pin "1") (pinfunction "1_1") (pintype "passive"))
      (node (ref "MT_C_BA") (pin "1") (pinfunction "1_1") (pintype "passive"))
      (node (ref "MT_C_BB") (pin "1") (pinfunction "1_1") (pintype "passive"))
      (node (ref "MT_C_BC") (pin "1") (pinfunction "1_1") (pintype "passive"))
      (node (ref "MT_C_BD") (pin "1") (pinfunction "1_1") (pintype "passive"))
      (node (ref "MT_C_BE") (pin "1") (pinfunction "1_1") (pintype "passive"))
      (node (ref "MT_C_BF") (pin "1") (pinfunction "1_1") (pintype "passive"))
      (node (ref "MT_C_BG") (pin "1") (pinfunction "1_1") (pintype "passive"))
      (node (ref "MT_C_BH") (pin "1") (pinfunction "1_1") (pintype "passive"))
      (node (ref "MT_C_BI") (pin "1") (pinfunction "1_1") (pintype "passive"))
      (node (ref "MT_C_BJ") (pin "1") (pinfunction "1_1") (pintype "passive"))
      (node (ref "MT_C_BK") (pin "1") (pinfunction "1_1") (pintype "passive"))
      (node (ref "MT_C_BL") (pin "1") (pinfunction "1_1") (pintype "passive"))
      (node (ref "MT_C_CA") (pin "1") (pinfunction "1_1") (pintype "passive"))
      (node (ref "MT_C_CB") (pin "1") (pinfunction "1_1") (pintype "passive"))
      (node (ref "MT_C_CC") (pin "1") (pinfunction "1_1") (pintype "passive"))
      (node (ref "MT_C_CD") (pin "1") (pinfunction "1_1") (pintype "passive"))
      (node (ref "MT_C_CE") (pin "1") (pinfunction "1_1") (pintype "passive"))
      (node (ref "MT_C_CF") (pin "1") (pinfunction "1_1") (pintype "passive"))
      (node (ref "MT_C_CG") (pin "1") (pinfunction "1_1") (pintype "passive"))
      (node (ref "MT_C_CH") (pin "1") (pinfunction "1_1") (pintype "passive"))
      (node (ref "MT_C_CI") (pin "1") (pinfunction "1_1") (pintype "passive"))
      (node (ref "MT_C_CJ") (pin "1") (pinfunction "1_1") (pintype "passive"))
      (node (ref "MT_C_CK") (pin "1") (pinfunction "1_1") (pintype "passive"))
      (node (ref "MT_C_CL") (pin "1") (pinfunction "1_1") (pintype "passive"))
      (node (ref "MT_C_CM") (pin "1") (pinfunction "1_1") (pintype "passive"))
      (node (ref "MT_C_CN") (pin "1") (pinfunction "1_1") (pintype "passive"))
      (node (ref "MT_C_DA") (pin "1") (pinfunction "1_1") (pintype "passive"))
      (node (ref "MT_C_DACO") (pin "2") (pinfunction "2_2") (pintype "passive"))
      (node (ref "MT_C_DB") (pin "1") (pinfunction "1_1") (pintype "passive"))
      (node (ref "MT_C_DC") (pin "1") (pinfunction "1_1") (pintype "passive"))
      (node (ref "MT_C_DD") (pin "1") (pinfunction "1_1") (pintype "passive"))
      (node (ref "MT_C_DE") (pin "1") (pinfunction "1_1") (pintype "passive"))
      (node (ref "MT_C_DF") (pin "1") (pinfunction "1_1") (pintype "passive"))
      (node (ref "MT_C_DG") (pin "1") (pinfunction "1_1") (pintype "passive"))
      (node (ref "MT_C_DH") (pin "1") (pinfunction "1_1") (pintype "passive"))
      (node (ref "MT_C_DI") (pin "1") (pinfunction "1_1") (pintype "passive"))
      (node (ref "MT_C_DJ") (pin "1") (pinfunction "1_1") (pintype "passive"))
      (node (ref "MT_C_DK") (pin "1") (pinfunction "1_1") (pintype "passive"))
      (node (ref "MT_C_DL") (pin "1") (pinfunction "1_1") (pintype "passive"))
      (node (ref "MT_C_EA") (pin "1") (pinfunction "1_1") (pintype "passive"))
      (node (ref "MT_C_EB") (pin "1") (pinfunction "1_1") (pintype "passive"))
      (node (ref "MT_C_EC") (pin "1") (pinfunction "1_1") (pintype "passive"))
      (node (ref "MT_C_ED") (pin "1") (pinfunction "1_1") (pintype "passive"))
      (node (ref "MT_C_EE") (pin "1") (pinfunction "1_1") (pintype "passive"))
      (node (ref "MT_C_EF") (pin "1") (pinfunction "1_1") (pintype "passive"))
      (node (ref "MT_C_EG") (pin "1") (pinfunction "1_1") (pintype "passive"))
      (node (ref "MT_C_EH") (pin "1") (pinfunction "1_1") (pintype "passive"))
      (node (ref "MT_C_EI") (pin "1") (pinfunction "1_1") (pintype "passive"))
      (node (ref "MT_C_EJ") (pin "1") (pinfunction "1_1") (pintype "passive"))
      (node (ref "MT_C_EK") (pin "1") (pinfunction "1_1") (pintype "passive"))
      (node (ref "MT_C_EL") (pin "1") (pinfunction "1_1") (pintype "passive"))
      (node (ref "MT_C_EXTVCC") (pin "2") (pinfunction "2_2") (pintype "passive"))
      (node (ref "MT_C_FA") (pin "1") (pinfunction "1_1") (pintype "passive"))
      (node (ref "MT_C_FB") (pin "1") (pinfunction "1_1") (pintype "passive"))
      (node (ref "MT_C_FBIW") (pin "2") (pinfunction "2_2") (pintype "passive"))
      (node (ref "MT_C_FC") (pin "1") (pinfunction "1_1") (pintype "passive"))
      (node (ref "MT_C_FD") (pin "1") (pinfunction "1_1") (pintype "passive"))
      (node (ref "MT_C_FE") (pin "1") (pinfunction "1_1") (pintype "passive"))
      (node (ref "MT_C_FF") (pin "1") (pinfunction "1_1") (pintype "passive"))
      (node (ref "MT_C_FG") (pin "1") (pinfunction "1_1") (pintype "passive"))
      (node (ref "MT_C_FH") (pin "1") (pinfunction "1_1") (pintype "passive"))
      (node (ref "MT_C_FI") (pin "1") (pinfunction "1_1") (pintype "passive"))
      (node (ref "MT_C_FJ") (pin "1") (pinfunction "1_1") (pintype "passive"))
      (node (ref "MT_C_FK") (pin "1") (pinfunction "1_1") (pintype "passive"))
      (node (ref "MT_C_FL") (pin "1") (pinfunction "1_1") (pintype "passive"))
      (node (ref "MT_C_GVCC") (pin "1") (pinfunction "1_1") (pintype "passive"))
      (node (ref "MT_C_IMON_IN") (pin "1") (pinfunction "1_1") (pintype "passive"))
      (node (ref "MT_C_IMON_OUT") (pin "1") (pinfunction "1_1") (pintype "passive"))
      (node (ref "MT_C_SS") (pin "2") (pinfunction "2_2") (pintype "passive"))
      (node (ref "MT_C_TEMP") (pin "2") (pinfunction "2_2") (pintype "passive"))
      (node (ref "MT_C_VC_A") (pin "2") (pinfunction "2_2") (pintype "passive"))
      (node (ref "MT_C_VC_B") (pin "2") (pinfunction "2_2") (pintype "passive"))
      (node (ref "MT_C_VDD") (pin "1") (pinfunction "1_1") (pintype "passive"))
      (node (ref "MT_C_ZA") (pin "1") (pinfunction "1_1") (pintype "passive"))
      (node (ref "MT_C_ZB") (pin "1") (pinfunction "1_1") (pintype "passive"))
      (node (ref "MT_C_ZC") (pin "1") (pinfunction "1_1") (pintype "passive"))
      (node (ref "MT_C_ZD") (pin "1") (pinfunction "1_1") (pintype "passive"))
      (node (ref "MT_C_ZE") (pin "1") (pinfunction "1_1") (pintype "passive"))
      (node (ref "MT_C_ZF") (pin "1") (pinfunction "1_1") (pintype "passive"))
      (node (ref "MT_D_IN_B") (pin "2") (pinfunction "A_2") (pintype "passive"))
      (node (ref "MT_D_IN_D") (pin "2") (pinfunction "A_2") (pintype "passive"))
      (node (ref "MT_D_IN_F") (pin "2") (pinfunction "A_2") (pintype "passive"))
      (node (ref "MT_D_IN_H") (pin "2") (pinfunction "A_2") (pintype "passive"))
      (node (ref "MT_D_IN_J") (pin "2") (pinfunction "A_2") (pintype "passive"))
      (node (ref "MT_D_IN_L") (pin "2") (pinfunction "A_2") (pintype "passive"))
      (node (ref "MT_D_IN_N") (pin "2") (pinfunction "A_2") (pintype "passive"))
      (node (ref "MT_D_IN_P") (pin "2") (pinfunction "A_2") (pintype "passive"))
      (node (ref "MT_ECON") (pin "2") (pinfunction "2_2") (pintype "passive"))
      (node (ref "MT_KB") (pin "4") (pinfunction "NO1_4") (pintype "passive"))
      (node (ref "MT_Q_ECON_A") (pin "2") (pinfunction "S_2") (pintype "passive"))
      (node (ref "MT_Q_KA") (pin "2") (pinfunction "S_2") (pintype "passive"))
      (node (ref "MT_Q_KB") (pin "2") (pinfunction "S_2") (pintype "passive"))
      (node (ref "MT_Q_SHDN") (pin "2") (pinfunction "S_2") (pintype "passive"))
      (node (ref "MT_Q_SWEN_A") (pin "2") (pinfunction "S_2") (pintype "passive"))
      (node (ref "MT_Q_VINR") (pin "2") (pinfunction "S_2") (pintype "passive"))
      (node (ref "MT_REG_THREE") (pin "1") (pinfunction "GND_1") (pintype "power_in"))
      (node (ref "MT_R_CS") (pin "2") (pinfunction "2_2") (pintype "passive"))
      (node (ref "MT_R_CSS_N") (pin "1") (pinfunction "1_1") (pintype "passive"))
      (node (ref "MT_R_FAULT_B") (pin "2") (pinfunction "2_2") (pintype "passive"))
      (node (ref "MT_R_FBIN_B") (pin "1") (pinfunction "1_1") (pintype "passive"))
      (node (ref "MT_R_FBOUT_B") (pin "1") (pinfunction "1_1") (pintype "passive"))
      (node (ref "MT_R_FV") (pin "2") (pinfunction "2_2") (pintype "passive"))
      (node (ref "MT_R_IMON_IN") (pin "1") (pinfunction "1_1") (pintype "passive"))
      (node (ref "MT_R_IMON_OUT") (pin "1") (pinfunction "1_1") (pintype "passive"))
      (node (ref "MT_R_KA") (pin "2") (pinfunction "2_2") (pintype "passive"))
      (node (ref "MT_R_KB") (pin "2") (pinfunction "2_2") (pintype "passive"))
      (node (ref "MT_R_MODE_B") (pin "1") (pinfunction "1_1") (pintype "passive"))
      (node (ref "MT_R_SHDN_B") (pin "1") (pinfunction "1_1") (pintype "passive"))
      (node (ref "MT_R_SHDN_C") (pin "2") (pinfunction "2_2") (pintype "passive"))
      (node (ref "MT_R_STATUS_B") (pin "2") (pinfunction "2_2") (pintype "passive"))
      (node (ref "MT_R_T") (pin "2") (pinfunction "2_2") (pintype "passive"))
      (node (ref "MT_R_TEMP_A") (pin "1") (pinfunction "1_1") (pintype "passive"))
      (node (ref "MT_R_VINR") (pin "2") (pinfunction "2_2") (pintype "passive"))
      (node (ref "MT_R_VINR_B") (pin "2") (pinfunction "2_2") (pintype "passive"))
      (node (ref "MT_SWEN") (pin "2") (pinfunction "2_2") (pintype "passive"))
      (node (ref "MT_U_AMP") (pin "11") (pinfunction "GND_11") (pintype "power_in"))
      (node (ref "MT_U_T") (pin "12") (pinfunction "VSS_12") (pintype "power_in"))
      (node (ref "MT_U_T") (pin "15") (pinfunction "E_15") (pintype "passive"))
      (node (ref "Q_LEDVSS") (pin "2") (pinfunction "S_2") (pintype "passive"))
      (node (ref "R110") (pin "1") (pinfunction "1_1") (pintype "passive"))
      (node (ref "R140") (pin "1") (pinfunction "1_1") (pintype "passive"))
      (node (ref "R_1A_c") (pin "1") (pinfunction "1_1") (pintype "passive"))
      (node (ref "R_1B_c") (pin "1") (pinfunction "1_1") (pintype "passive"))
      (node (ref "TWLV_C_AA") (pin "2") (pinfunction "2_2") (pintype "passive"))
      (node (ref "TWLV_C_AB") (pin "2") (pinfunction "2_2") (pintype "passive"))
      (node (ref "TWLV_C_AC") (pin "2") (pinfunction "2_2") (pintype "passive"))
      (node (ref "TWLV_C_AD") (pin "2") (pinfunction "2_2") (pintype "passive"))
      (node (ref "TWLV_C_AE") (pin "2") (pinfunction "2_2") (pintype "passive"))
      (node (ref "TWLV_C_AF") (pin "2") (pinfunction "2_2") (pintype "passive"))
      (node (ref "TWLV_C_AG") (pin "2") (pinfunction "2_2") (pintype "passive"))
      (node (ref "TWLV_C_AH") (pin "2") (pinfunction "2_2") (pintype "passive"))
      (node (ref "TWLV_C_AI") (pin "2") (pinfunction "2_2") (pintype "passive"))
      (node (ref "TWLV_C_AJ") (pin "2") (pinfunction "2_2") (pintype "passive"))
      (node (ref "TWLV_C_AK") (pin "2") (pinfunction "2_2") (pintype "passive"))
      (node (ref "TWLV_C_AL") (pin "2") (pinfunction "2_2") (pintype "passive"))
      (node (ref "TWLV_C_AM") (pin "2") (pinfunction "2_2") (pintype "passive"))
      (node (ref "TWLV_C_AN") (pin "2") (pinfunction "2_2") (pintype "passive"))
      (node (ref "TWLV_C_AO") (pin "2") (pinfunction "2_2") (pintype "passive"))
      (node (ref "TWLV_C_AP") (pin "2") (pinfunction "2_2") (pintype "passive"))
      (node (ref "TWLV_C_AQ") (pin "2") (pinfunction "2_2") (pintype "passive"))
      (node (ref "TWLV_C_AR") (pin "2") (pinfunction "2_2") (pintype "passive"))
      (node (ref "TWLV_C_AS") (pin "2") (pinfunction "2_2") (pintype "passive"))
      (node (ref "TWLV_C_AT") (pin "2") (pinfunction "2_2") (pintype "passive"))
      (node (ref "TWLV_C_AU") (pin "2") (pinfunction "2_2") (pintype "passive"))
      (node (ref "TWLV_C_AV") (pin "2") (pinfunction "2_2") (pintype "passive"))
      (node (ref "TWLV_C_AW") (pin "2") (pinfunction "2_2") (pintype "passive"))
      (node (ref "TWLV_C_AX") (pin "2") (pinfunction "2_2") (pintype "passive"))
      (node (ref "TWLV_C_AY") (pin "2") (pinfunction "2_2") (pintype "passive"))
      (node (ref "TWLV_C_AZ") (pin "2") (pinfunction "2_2") (pintype "passive"))
      (node (ref "TWLV_C_BA") (pin "2") (pinfunction "2_2") (pintype "passive"))
      (node (ref "TWLV_C_BB") (pin "2") (pinfunction "2_2") (pintype "passive"))
      (node (ref "TWLV_C_BC") (pin "2") (pinfunction "2_2") (pintype "passive"))
      (node (ref "TWLV_C_BD") (pin "2") (pinfunction "2_2") (pintype "passive"))
      (node (ref "TWLV_C_BE") (pin "2") (pinfunction "2_2") (pintype "passive"))
      (node (ref "TWLV_C_BF") (pin "2") (pinfunction "2_2") (pintype "passive"))
      (node (ref "TWLV_C_BG") (pin "2") (pinfunction "2_2") (pintype "passive"))
      (node (ref "TWLV_C_BH") (pin "2") (pinfunction "2_2") (pintype "passive"))
      (node (ref "TWLV_C_BI") (pin "2") (pinfunction "2_2") (pintype "passive"))
      (node (ref "TWLV_C_BJ") (pin "2") (pinfunction "2_2") (pintype "passive"))
      (node (ref "TWLV_C_DA") (pin "2") (pinfunction "2_2") (pintype "passive"))
      (node (ref "TWLV_C_DB") (pin "2") (pinfunction "2_2") (pintype "passive"))
      (node (ref "TWLV_C_DC") (pin "2") (pinfunction "2_2") (pintype "passive"))
      (node (ref "TWLV_C_DD") (pin "2") (pinfunction "2_2") (pintype "passive"))
      (node (ref "TWLV_D_A") (pin "2") (pinfunction "A_2") (pintype "passive"))
      (node (ref "TWLV_Q_A") (pin "2") (pinfunction "S_2") (pintype "passive"))
      (node (ref "TWLV_R_B") (pin "2") (pinfunction "2_2") (pintype "passive"))
      (node (ref "TWLV_R_D") (pin "1") (pinfunction "1_1") (pintype "passive"))
      (node (ref "U") (pin "21") (pinfunction "SYNC_21") (pintype "input"))
      (node (ref "U") (pin "55") (pinfunction "GND@1_55") (pintype "power_in"))
      (node (ref "U") (pin "59") (pinfunction "GND@2_59") (pintype "power_in"))
      (node (ref "U") (pin "61") (pinfunction "CHARGECFG1_61") (pintype "input"))
      (node (ref "U") (pin "62") (pinfunction "GND@3_62") (pintype "power_in"))
      (node (ref "U") (pin "63") (pinfunction "CHARGECFG2_63") (pintype "input"))
      (node (ref "U") (pin "65") (pinfunction "GND@4_65") (pintype "power_in"))
      (node (ref "U_TWLV_A") (pin "3") (pinfunction "GND_3") (pintype "power_in"))
      (node (ref "U_TWLV_A") (pin "6") (pinfunction "GND_6") (pintype "power_in"))
      (node (ref "U_TWLV_A") (pin "7") (pinfunction "GND_7") (pintype "power_in"))
    )
    (net (code "100") (name "LM_VIN") (class "Default")
      (node (ref "TWLV_C_DA") (pin "1") (pinfunction "1_1") (pintype "passive"))
      (node (ref "TWLV_C_DB") (pin "1") (pinfunction "1_1") (pintype "passive"))
      (node (ref "TWLV_C_DC") (pin "1") (pinfunction "1_1") (pintype "passive"))
      (node (ref "TWLV_C_DD") (pin "1") (pinfunction "1_1") (pintype "passive"))
      (node (ref "TWLV_R_A") (pin "1") (pinfunction "1_1") (pintype "passive"))
      (node (ref "U_TWLV_A") (pin "1") (pinfunction "VIN_1") (pintype "input"))
    )
    (net (code "101") (name "Net-(D3-A)") (class "Default")
      (node (ref "D3") (pin "2") (pinfunction "A_2") (pintype "passive"))
      (node (ref "MT_Q1") (pin "1") (pinfunction "G_1") (pintype "passive"))
      (node (ref "Rtg1a") (pin "2") (pinfunction "2_2") (pintype "passive"))
      (node (ref "Rtg1s") (pin "2") (pinfunction "2_2") (pintype "passive"))
    )
    (net (code "102") (name "Net-(D4-A)") (class "Default")
      (node (ref "D4") (pin "2") (pinfunction "A_2") (pintype "passive"))
      (node (ref "MT_Q4") (pin "1") (pinfunction "G_1") (pintype "passive"))
      (node (ref "Rtg2a") (pin "1") (pinfunction "1_1") (pintype "passive"))
      (node (ref "Rtg2s") (pin "1") (pinfunction "1_1") (pintype "passive"))
    )
    (net (code "103") (name "Net-(D5-A)") (class "Default")
      (node (ref "D5") (pin "2") (pinfunction "A_2") (pintype "passive"))
      (node (ref "MT_Q2") (pin "1") (pinfunction "G_1") (pintype "passive"))
      (node (ref "Rbg1a") (pin "2") (pinfunction "2_2") (pintype "passive"))
      (node (ref "Rbg1s") (pin "2") (pinfunction "2_2") (pintype "passive"))
    )
    (net (code "104") (name "Net-(D6-A)") (class "Default")
      (node (ref "D6") (pin "2") (pinfunction "A_2") (pintype "passive"))
      (node (ref "MT_Q3") (pin "1") (pinfunction "G_1") (pintype "passive"))
      (node (ref "Rbg2a") (pin "1") (pinfunction "1_1") (pintype "passive"))
      (node (ref "Rbg2s") (pin "1") (pinfunction "1_1") (pintype "passive"))
    )
    (net (code "105") (name "Net-(D14-A)") (class "Default")
      (node (ref "C19") (pin "1") (pinfunction "1_1") (pintype "passive"))
      (node (ref "D14") (pin "2") (pinfunction "A_2") (pintype "passive"))
      (node (ref "R140") (pin "2") (pinfunction "2_2") (pintype "passive"))
    )
    (net (code "106") (name "Net-(D15-A)") (class "Default")
      (node (ref "C18") (pin "1") (pinfunction "1_1") (pintype "passive"))
      (node (ref "D15") (pin "2") (pinfunction "A_2") (pintype "passive"))
      (node (ref "R110") (pin "2") (pinfunction "2_2") (pintype "passive"))
    )
    (net (code "107") (name "Net-(D_CLAMP_1-A)") (class "Default")
      (node (ref "D_CLAMP_1") (pin "2") (pinfunction "A_2") (pintype "passive"))
      (node (ref "D_CLAMP_2") (pin "1") (pinfunction "K_1") (pintype "passive"))
    )
    (net (code "108") (name "Net-(D_CLAMP_2-A)") (class "Default")
      (node (ref "D_CLAMP_2") (pin "2") (pinfunction "A_2") (pintype "passive"))
      (node (ref "D_CLAMP_3") (pin "1") (pinfunction "K_1") (pintype "passive"))
    )
    (net (code "109") (name "Net-(D_CLAMP_3-A)") (class "Default")
      (node (ref "D_CLAMP_3") (pin "2") (pinfunction "A_2") (pintype "passive"))
      (node (ref "D_CLAMP_4") (pin "1") (pinfunction "K_1") (pintype "passive"))
    )
    (net (code "110") (name "Net-(D_CLAMP_4-A)") (class "Default")
      (node (ref "D_CLAMP_4") (pin "2") (pinfunction "A_2") (pintype "passive"))
      (node (ref "D_CLAMP_5") (pin "1") (pinfunction "K_1") (pintype "passive"))
    )
    (net (code "111") (name "Net-(D_CLAMP_5-A)") (class "Default")
      (node (ref "D_CLAMP_5") (pin "2") (pinfunction "A_2") (pintype "passive"))
      (node (ref "D_CLAMP_6") (pin "1") (pinfunction "K_1") (pintype "passive"))
    )
    (net (code "112") (name "Net-(D_CLAMP_6-A)") (class "Default")
      (node (ref "D_CLAMP_6") (pin "2") (pinfunction "A_2") (pintype "passive"))
      (node (ref "D_CLAMP_7") (pin "1") (pinfunction "K_1") (pintype "passive"))
    )
    (net (code "113") (name "Net-(D_CLAMP_7-A)") (class "Default")
      (node (ref "D_CLAMP_7") (pin "2") (pinfunction "A_2") (pintype "passive"))
      (node (ref "D_CLAMP_8") (pin "1") (pinfunction "K_1") (pintype "passive"))
    )
    (net (code "114") (name "Net-(D_CLAMP_10-K)") (class "Default")
      (node (ref "D_CLAMP_10") (pin "1") (pinfunction "K_1") (pintype "passive"))
      (node (ref "D_CLAMP_9") (pin "2") (pinfunction "A_2") (pintype "passive"))
    )
    (net (code "115") (name "Net-(D_CLAMP_11-A)") (class "Default")
      (node (ref "D_CLAMP_11") (pin "2") (pinfunction "A_2") (pintype "passive"))
      (node (ref "D_CLAMP_12") (pin "1") (pinfunction "K_1") (pintype "passive"))
    )
    (net (code "116") (name "Net-(D_CLAMP_12-A)") (class "Default")
      (node (ref "D_CLAMP_12") (pin "2") (pinfunction "A_2") (pintype "passive"))
      (node (ref "D_CLAMP_13") (pin "1") (pinfunction "K_1") (pintype "passive"))
    )
    (net (code "117") (name "Net-(D_CLAMP_13-A)") (class "Default")
      (node (ref "D_CLAMP_13") (pin "2") (pinfunction "A_2") (pintype "passive"))
      (node (ref "D_CLAMP_14") (pin "1") (pinfunction "K_1") (pintype "passive"))
    )
    (net (code "118") (name "Net-(J1-Pad10)") (class "Default")
      (node (ref "J1") (pin "10") (pinfunction "10_10") (pintype "passive"))
      (node (ref "R101") (pin "2") (pinfunction "2_2") (pintype "passive"))
    )
    (net (code "119") (name "Net-(J1-Pad12)") (class "Default")
      (node (ref "J1") (pin "12") (pinfunction "12_12") (pintype "passive"))
      (node (ref "R100") (pin "2") (pinfunction "2_2") (pintype "passive"))
    )
    (net (code "120") (name "Net-(J2-Pad10)") (class "Default")
      (node (ref "J2") (pin "10") (pinfunction "10_10") (pintype "passive"))
      (node (ref "R102") (pin "2") (pinfunction "2_2") (pintype "passive"))
    )
    (net (code "121") (name "Net-(J2-Pad12)") (class "Default")
      (node (ref "J2") (pin "12") (pinfunction "12_12") (pintype "passive"))
      (node (ref "R103") (pin "2") (pinfunction "2_2") (pintype "passive"))
    )
    (net (code "122") (name "Net-(MT_C_VC_B-Pad1)") (class "Default")
      (node (ref "MT_C_VC_B") (pin "1") (pinfunction "1_1") (pintype "passive"))
      (node (ref "MT_R_VC") (pin "2") (pinfunction "2_2") (pintype "passive"))
    )
    (net (code "123") (name "Net-(MT_D_ECON-A)") (class "Default")
      (node (ref "MT_D_ECON") (pin "2") (pinfunction "A_2") (pintype "passive"))
      (node (ref "MT_Q_ECON_B") (pin "1") (pinfunction "G_1") (pintype "passive"))
      (node (ref "MT_R_ECON_C") (pin "1") (pinfunction "1_1") (pintype "passive"))
      (node (ref "MT_R_ECON_D") (pin "2") (pinfunction "2_2") (pintype "passive"))
    )
    (net (code "124") (name "Net-(MT_D_FAULT-K)") (class "Default")
      (node (ref "MT_D_FAULT") (pin "1") (pinfunction "K_1") (pintype "passive"))
      (node (ref "MT_R_FAULT_B") (pin "1") (pinfunction "1_1") (pintype "passive"))
    )
    (net (code "125") (name "Net-(MT_D_KA_A-A)") (class "Default")
      (node (ref "MT_D_KA_A") (pin "2") (pinfunction "A_2") (pintype "passive"))
      (node (ref "MT_D_KA_B") (pin "2") (pinfunction "A_2") (pintype "passive"))
    )
    (net (code "126") (name "Net-(MT_D_KB_A-A)") (class "Default")
      (node (ref "MT_D_KB_A") (pin "2") (pinfunction "A_2") (pintype "passive"))
      (node (ref "MT_D_KB_B") (pin "2") (pinfunction "A_2") (pintype "passive"))
    )
    (net (code "127") (name "Net-(MT_D_STATUS-K)") (class "Default")
      (node (ref "MT_D_STATUS") (pin "1") (pinfunction "K_1") (pintype "passive"))
      (node (ref "MT_R_STATUS_B") (pin "1") (pinfunction "1_1") (pintype "passive"))
    )
    (net (code "128") (name "Net-(MT_D_SWEN-A)") (class "Default")
      (node (ref "MT_D_SWEN") (pin "2") (pinfunction "A_2") (pintype "passive"))
      (node (ref "MT_Q_SWEN_B") (pin "1") (pinfunction "G_1") (pintype "passive"))
      (node (ref "MT_R_SWEN_C") (pin "1") (pinfunction "1_1") (pintype "passive"))
      (node (ref "MT_R_SWEN_D") (pin "2") (pinfunction "2_2") (pintype "passive"))
    )
    (net (code "129") (name "Net-(MT_Q_ECON_A-D)") (class "Default")
      (node (ref "MT_Q_ECON_A") (pin "3") (pinfunction "D_3") (pintype "passive"))
      (node (ref "MT_R_ECON_D") (pin "1") (pinfunction "1_1") (pintype "passive"))
    )
    (net (code "130") (name "Net-(MT_Q_ECON_B-D)") (class "Default")
      (node (ref "MT_Q_ECON_B") (pin "3") (pinfunction "D_3") (pintype "passive"))
      (node (ref "MT_R_ECON_B") (pin "1") (pinfunction "1_1") (pintype "passive"))
      (node (ref "MT_R_ECON_E") (pin "2") (pinfunction "2_2") (pintype "passive"))
    )
    (net (code "131") (name "Net-(MT_Q_SWEN_A-D)") (class "Default")
      (node (ref "MT_Q_SWEN_A") (pin "3") (pinfunction "D_3") (pintype "passive"))
      (node (ref "MT_R_SWEN_D") (pin "1") (pinfunction "1_1") (pintype "passive"))
    )
    (net (code "132") (name "Net-(MT_R_FBIN_A-Pad1)") (class "Default")
      (node (ref "MT_R_FBIN_A") (pin "1") (pinfunction "1_1") (pintype "passive"))
      (node (ref "MT_R_FBIN_C") (pin "1") (pinfunction "1_1") (pintype "passive"))
    )
    (net (code "133") (name "Net-(MT_R_FBOUT_AA-Pad1)") (class "Default")
      (node (ref "MT_R_FBOUT_AA") (pin "1") (pinfunction "1_1") (pintype "passive"))
      (node (ref "MT_R_FBOUT_AB") (pin "1") (pinfunction "1_1") (pintype "passive"))
      (node (ref "MT_R_FBOUT_C") (pin "1") (pinfunction "1_1") (pintype "passive"))
    )
    (net (code "134") (name "Net-(MT_R_VINR_A-Pad2)") (class "Default")
      (node (ref "MT_R_VINR_A") (pin "2") (pinfunction "2_2") (pintype "passive"))
      (node (ref "MT_R_VINR_C") (pin "1") (pinfunction "1_1") (pintype "passive"))
    )
    (net (code "135") (name "Net-(R_1A_a-Pad2)") (class "Default")
      (node (ref "R_1A_a") (pin "2") (pinfunction "2_2") (pintype "passive"))
      (node (ref "R_1A_b") (pin "1") (pinfunction "1_1") (pintype "passive"))
    )
    (net (code "136") (name "Net-(R_1B_a-Pad2)") (class "Default")
      (node (ref "R_1B_a") (pin "2") (pinfunction "2_2") (pintype "passive"))
      (node (ref "R_1B_b") (pin "1") (pinfunction "1_1") (pintype "passive"))
    )
    (net (code "137") (name "Net-(TWLV_D_A-K)") (class "Default")
      (node (ref "TWLV_D_A") (pin "1") (pinfunction "K_1") (pintype "passive"))
      (node (ref "TWLV_L_A") (pin "1") (pinfunction "1_1") (pintype "passive"))
      (node (ref "U_TWLV_A") (pin "2") (pinfunction "OUT_2") (pintype "output"))
    )
    (net (code "138") (name "Net-(TWLV_L_A-Pad2)") (class "Default")
      (node (ref "TWLV_L_A") (pin "2") (pinfunction "2_2") (pintype "passive"))
      (node (ref "TWLV_R_E") (pin "1") (pinfunction "1_1") (pintype "passive"))
    )
    (net (code "139") (name "VIN_N") (class "Default")
      (node (ref "Dtg1") (pin "1") (pinfunction "K_1") (pintype "passive"))
      (node (ref "MT_C_DA") (pin "2") (pinfunction "2_2") (pintype "passive"))
      (node (ref "MT_C_DB") (pin "2") (pinfunction "2_2") (pintype "passive"))
      (node (ref "MT_C_DC") (pin "2") (pinfunction "2_2") (pintype "passive"))
      (node (ref "MT_C_DD") (pin "2") (pinfunction "2_2") (pintype "passive"))
      (node (ref "MT_C_DE") (pin "2") (pinfunction "2_2") (pintype "passive"))
      (node (ref "MT_C_DF") (pin "2") (pinfunction "2_2") (pintype "passive"))
      (node (ref "MT_C_DG") (pin "2") (pinfunction "2_2") (pintype "passive"))
      (node (ref "MT_C_DH") (pin "2") (pinfunction "2_2") (pintype "passive"))
      (node (ref "MT_C_DI") (pin "2") (pinfunction "2_2") (pintype "passive"))
      (node (ref "MT_C_DJ") (pin "2") (pinfunction "2_2") (pintype "passive"))
      (node (ref "MT_C_DK") (pin "2") (pinfunction "2_2") (pintype "passive"))
      (node (ref "MT_C_DL") (pin "2") (pinfunction "2_2") (pintype "passive"))
      (node (ref "MT_Q1") (pin "2") (pinfunction "D_2") (pintype "passive"))
      (node (ref "MT_R_VIN_B") (pin "2") (pinfunction "2_2") (pintype "passive"))
      (node (ref "R1") (pin "2") (pinfunction "2_2") (pintype "passive"))
    )
    (net (code "140") (name "VIN_P") (class "Default")
      (node (ref "D_CLAMP_1") (pin "1") (pinfunction "K_1") (pintype "passive"))
      (node (ref "MT_C_AA") (pin "2") (pinfunction "2_2") (pintype "passive"))
      (node (ref "MT_C_AB") (pin "2") (pinfunction "2_2") (pintype "passive"))
      (node (ref "MT_C_AC") (pin "2") (pinfunction "2_2") (pintype "passive"))
      (node (ref "MT_C_AD") (pin "2") (pinfunction "2_2") (pintype "passive"))
      (node (ref "MT_C_AE") (pin "2") (pinfunction "2_2") (pintype "passive"))
      (node (ref "MT_C_AF") (pin "2") (pinfunction "2_2") (pintype "passive"))
      (node (ref "MT_C_AG") (pin "2") (pinfunction "2_2") (pintype "passive"))
      (node (ref "MT_C_AH") (pin "2") (pinfunction "2_2") (pintype "passive"))
      (node (ref "MT_C_AI") (pin "2") (pinfunction "2_2") (pintype "passive"))
      (node (ref "MT_C_AJ") (pin "2") (pinfunction "2_2") (pintype "passive"))
      (node (ref "MT_C_AK") (pin "2") (pinfunction "2_2") (pintype "passive"))
      (node (ref "MT_C_AL") (pin "2") (pinfunction "2_2") (pintype "passive"))
      (node (ref "MT_C_AM") (pin "2") (pinfunction "2_2") (pintype "passive"))
      (node (ref "MT_C_AN") (pin "2") (pinfunction "2_2") (pintype "passive"))
      (node (ref "MT_C_EA") (pin "2") (pinfunction "2_2") (pintype "passive"))
      (node (ref "MT_C_EB") (pin "2") (pinfunction "2_2") (pintype "passive"))
      (node (ref "MT_C_EC") (pin "2") (pinfunction "2_2") (pintype "passive"))
      (node (ref "MT_C_ED") (pin "2") (pinfunction "2_2") (pintype "passive"))
      (node (ref "MT_C_EE") (pin "2") (pinfunction "2_2") (pintype "passive"))
      (node (ref "MT_C_EF") (pin "2") (pinfunction "2_2") (pintype "passive"))
      (node (ref "MT_C_EG") (pin "2") (pinfunction "2_2") (pintype "passive"))
      (node (ref "MT_C_EH") (pin "2") (pinfunction "2_2") (pintype "passive"))
      (node (ref "MT_C_EI") (pin "2") (pinfunction "2_2") (pintype "passive"))
      (node (ref "MT_C_EJ") (pin "2") (pinfunction "2_2") (pintype "passive"))
      (node (ref "MT_C_EK") (pin "2") (pinfunction "2_2") (pintype "passive"))
      (node (ref "MT_C_EL") (pin "2") (pinfunction "2_2") (pintype "passive"))
      (node (ref "MT_D_IN_A") (pin "1") (pinfunction "K_1") (pintype "passive"))
      (node (ref "MT_D_IN_C") (pin "1") (pinfunction "K_1") (pintype "passive"))
      (node (ref "MT_D_IN_E") (pin "1") (pinfunction "K_1") (pintype "passive"))
      (node (ref "MT_D_IN_G") (pin "1") (pinfunction "K_1") (pintype "passive"))
      (node (ref "MT_D_IN_I") (pin "1") (pinfunction "K_1") (pintype "passive"))
      (node (ref "MT_D_IN_K") (pin "1") (pinfunction "K_1") (pintype "passive"))
      (node (ref "MT_D_IN_M") (pin "1") (pinfunction "K_1") (pintype "passive"))
      (node (ref "MT_D_IN_O") (pin "1") (pinfunction "K_1") (pintype "passive"))
      (node (ref "MT_KB") (pin "5") (pinfunction "NO2_5") (pintype "passive"))
      (node (ref "MT_R_FBIN_A") (pin "2") (pinfunction "2_2") (pintype "passive"))
      (node (ref "MT_R_SHDN_A") (pin "2") (pinfunction "2_2") (pintype "passive"))
      (node (ref "MT_R_VINR_A") (pin "1") (pinfunction "1_1") (pintype "passive"))
      (node (ref "MT_R_VIN_A") (pin "2") (pinfunction "2_2") (pintype "passive"))
      (node (ref "R1") (pin "1") (pinfunction "1_1") (pintype "passive"))
      (node (ref "U") (pin "46") (pinfunction "VIN_46") (pintype "power_in"))
    )
    (net (code "141") (name "VOUT_N") (class "Default")
      (node (ref "MT_C_BA") (pin "2") (pinfunction "2_2") (pintype "passive"))
      (node (ref "MT_C_BB") (pin "2") (pinfunction "2_2") (pintype "passive"))
      (node (ref "MT_C_BC") (pin "2") (pinfunction "2_2") (pintype "passive"))
      (node (ref "MT_C_BD") (pin "2") (pinfunction "2_2") (pintype "passive"))
      (node (ref "MT_C_BE") (pin "2") (pinfunction "2_2") (pintype "passive"))
      (node (ref "MT_C_BF") (pin "2") (pinfunction "2_2") (pintype "passive"))
      (node (ref "MT_C_BG") (pin "2") (pinfunction "2_2") (pintype "passive"))
      (node (ref "MT_C_BH") (pin "2") (pinfunction "2_2") (pintype "passive"))
      (node (ref "MT_C_BI") (pin "2") (pinfunction "2_2") (pintype "passive"))
      (node (ref "MT_C_BJ") (pin "2") (pinfunction "2_2") (pintype "passive"))
      (node (ref "MT_C_BK") (pin "2") (pinfunction "2_2") (pintype "passive"))
      (node (ref "MT_C_BL") (pin "2") (pinfunction "2_2") (pintype "passive"))
      (node (ref "MT_C_CM") (pin "2") (pinfunction "2_2") (pintype "passive"))
      (node (ref "MT_C_CN") (pin "2") (pinfunction "2_2") (pintype "passive"))
      (node (ref "MT_C_FA") (pin "2") (pinfunction "2_2") (pintype "passive"))
      (node (ref "MT_C_FB") (pin "2") (pinfunction "2_2") (pintype "passive"))
      (node (ref "MT_C_FC") (pin "2") (pinfunction "2_2") (pintype "passive"))
      (node (ref "MT_C_FD") (pin "2") (pinfunction "2_2") (pintype "passive"))
      (node (ref "MT_C_FE") (pin "2") (pinfunction "2_2") (pintype "passive"))
      (node (ref "MT_C_FF") (pin "2") (pinfunction "2_2") (pintype "passive"))
      (node (ref "MT_C_FG") (pin "2") (pinfunction "2_2") (pintype "passive"))
      (node (ref "MT_C_FH") (pin "2") (pinfunction "2_2") (pintype "passive"))
      (node (ref "MT_C_FI") (pin "2") (pinfunction "2_2") (pintype "passive"))
      (node (ref "MT_C_FJ") (pin "2") (pinfunction "2_2") (pintype "passive"))
      (node (ref "MT_C_FK") (pin "2") (pinfunction "2_2") (pintype "passive"))
      (node (ref "MT_C_FL") (pin "2") (pinfunction "2_2") (pintype "passive"))
      (node (ref "MT_D_ECON") (pin "1") (pinfunction "K_1") (pintype "passive"))
      (node (ref "MT_D_SWEN") (pin "1") (pinfunction "K_1") (pintype "passive"))
      (node (ref "MT_Q_ECON_B") (pin "2") (pinfunction "S_2") (pintype "passive"))
      (node (ref "MT_Q_SWEN_B") (pin "2") (pinfunction "S_2") (pintype "passive"))
      (node (ref "MT_R_ECON_B") (pin "2") (pinfunction "2_2") (pintype "passive"))
      (node (ref "MT_R_ECON_C") (pin "2") (pinfunction "2_2") (pintype "passive"))
      (node (ref "MT_R_SWEN_B") (pin "2") (pinfunction "2_2") (pintype "passive"))
      (node (ref "MT_R_SWEN_C") (pin "2") (pinfunction "2_2") (pintype "passive"))
      (node (ref "MT_R_VOUT_B") (pin "2") (pinfunction "2_2") (pintype "passive"))
      (node (ref "R10") (pin "1") (pinfunction "1_1") (pintype "passive"))
    )
    (net (code "142") (name "VOUT_P") (class "Default")
      (node (ref "Dtg2") (pin "1") (pinfunction "K_1") (pintype "passive"))
      (node (ref "MT_C_CA") (pin "2") (pinfunction "2_2") (pintype "passive"))
      (node (ref "MT_C_CB") (pin "2") (pinfunction "2_2") (pintype "passive"))
      (node (ref "MT_C_CC") (pin "2") (pinfunction "2_2") (pintype "passive"))
      (node (ref "MT_C_CD") (pin "2") (pinfunction "2_2") (pintype "passive"))
      (node (ref "MT_C_CE") (pin "2") (pinfunction "2_2") (pintype "passive"))
      (node (ref "MT_C_CF") (pin "2") (pinfunction "2_2") (pintype "passive"))
      (node (ref "MT_C_CG") (pin "2") (pinfunction "2_2") (pintype "passive"))
      (node (ref "MT_C_CH") (pin "2") (pinfunction "2_2") (pintype "passive"))
      (node (ref "MT_C_CI") (pin "2") (pinfunction "2_2") (pintype "passive"))
      (node (ref "MT_C_CJ") (pin "2") (pinfunction "2_2") (pintype "passive"))
      (node (ref "MT_C_CK") (pin "2") (pinfunction "2_2") (pintype "passive"))
      (node (ref "MT_C_CL") (pin "2") (pinfunction "2_2") (pintype "passive"))
      (node (ref "MT_Q4") (pin "2") (pinfunction "D_2") (pintype "passive"))
      (node (ref "MT_R_EXTVCC") (pin "1") (pinfunction "1_1") (pintype "passive"))
      (node (ref "MT_R_VOUT_A") (pin "2") (pinfunction "2_2") (pintype "passive"))
      (node (ref "R10") (pin "2") (pinfunction "2_2") (pintype "passive"))
    )
    (net (code "143") (name "unconnected-(J1-SHIELD-PadS1)") (class "Default")
      (node (ref "J1") (pin "S1") (pinfunction "SHIELD_S1") (pintype "passive"))
    )
    (net (code "144") (name "unconnected-(J1-SHIELD-PadS2)") (class "Default")
      (node (ref "J1") (pin "S2") (pinfunction "SHIELD_S2") (pintype "passive"))
    )
    (net (code "145") (name "unconnected-(J2-SHIELD-PadS1)") (class "Default")
      (node (ref "J2") (pin "S1") (pinfunction "SHIELD_S1") (pintype "passive"))
    )
    (net (code "146") (name "unconnected-(J2-SHIELD-PadS2)") (class "Default")
      (node (ref "J2") (pin "S2") (pinfunction "SHIELD_S2") (pintype "passive"))
    )
    (net (code "147") (name "unconnected-(MT_KB-NC1-Pad2)") (class "Default")
      (node (ref "MT_KB") (pin "2") (pinfunction "NC1_2") (pintype "passive"))
    )
  )
)
